# mppt.net
KiCad netlist of a schematic drawn in Altium Designer
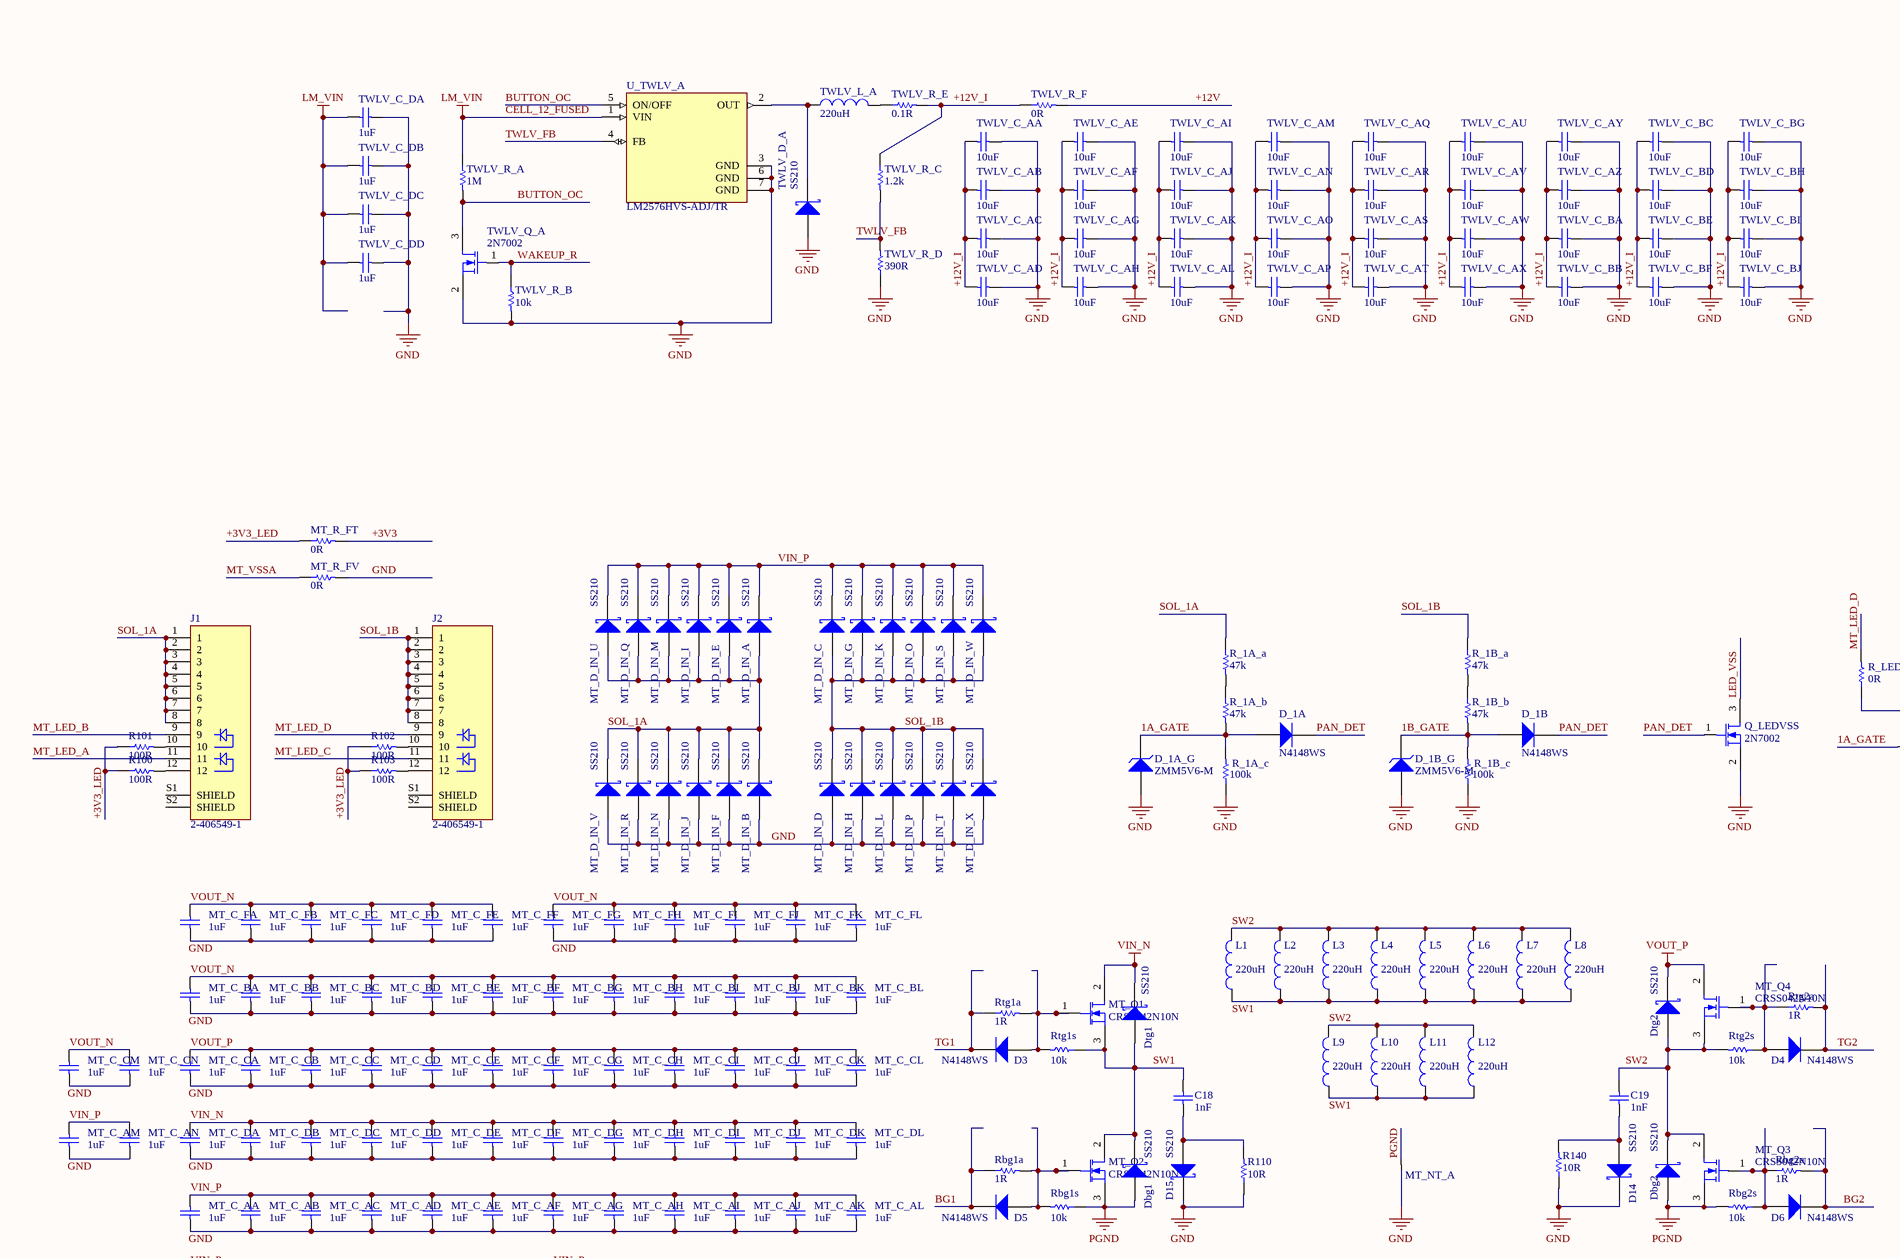
[diagram p0: mppt.SchDoc, top left]
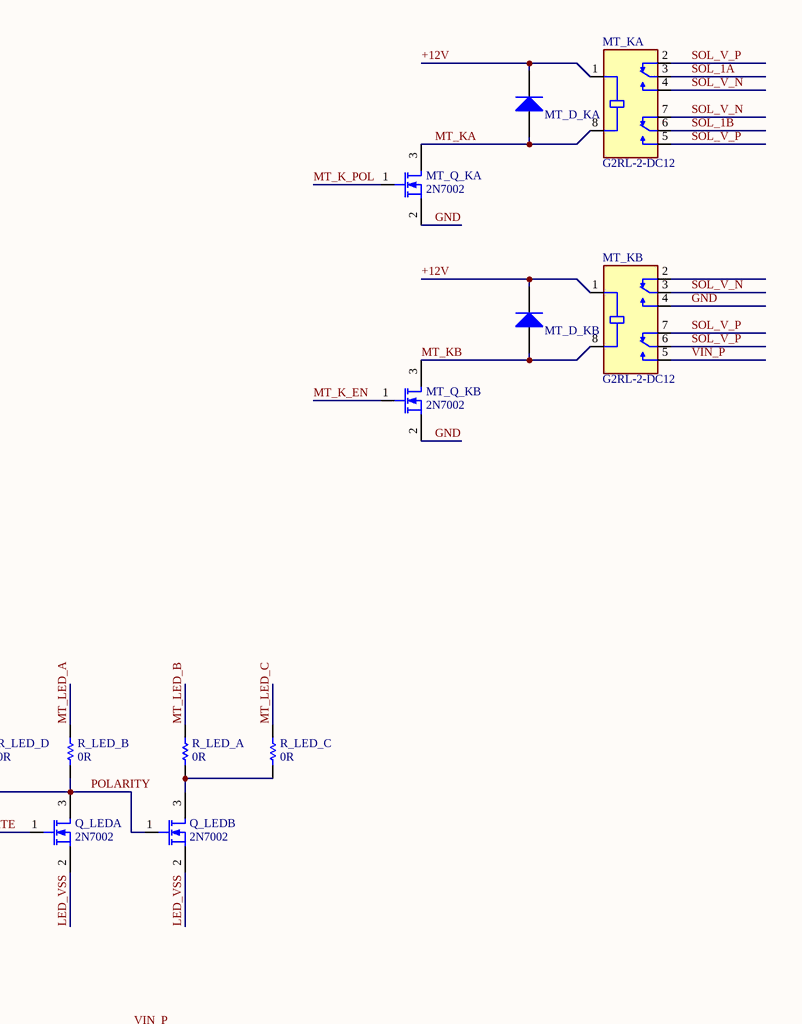
[diagram p1: mppt.SchDoc, top right]
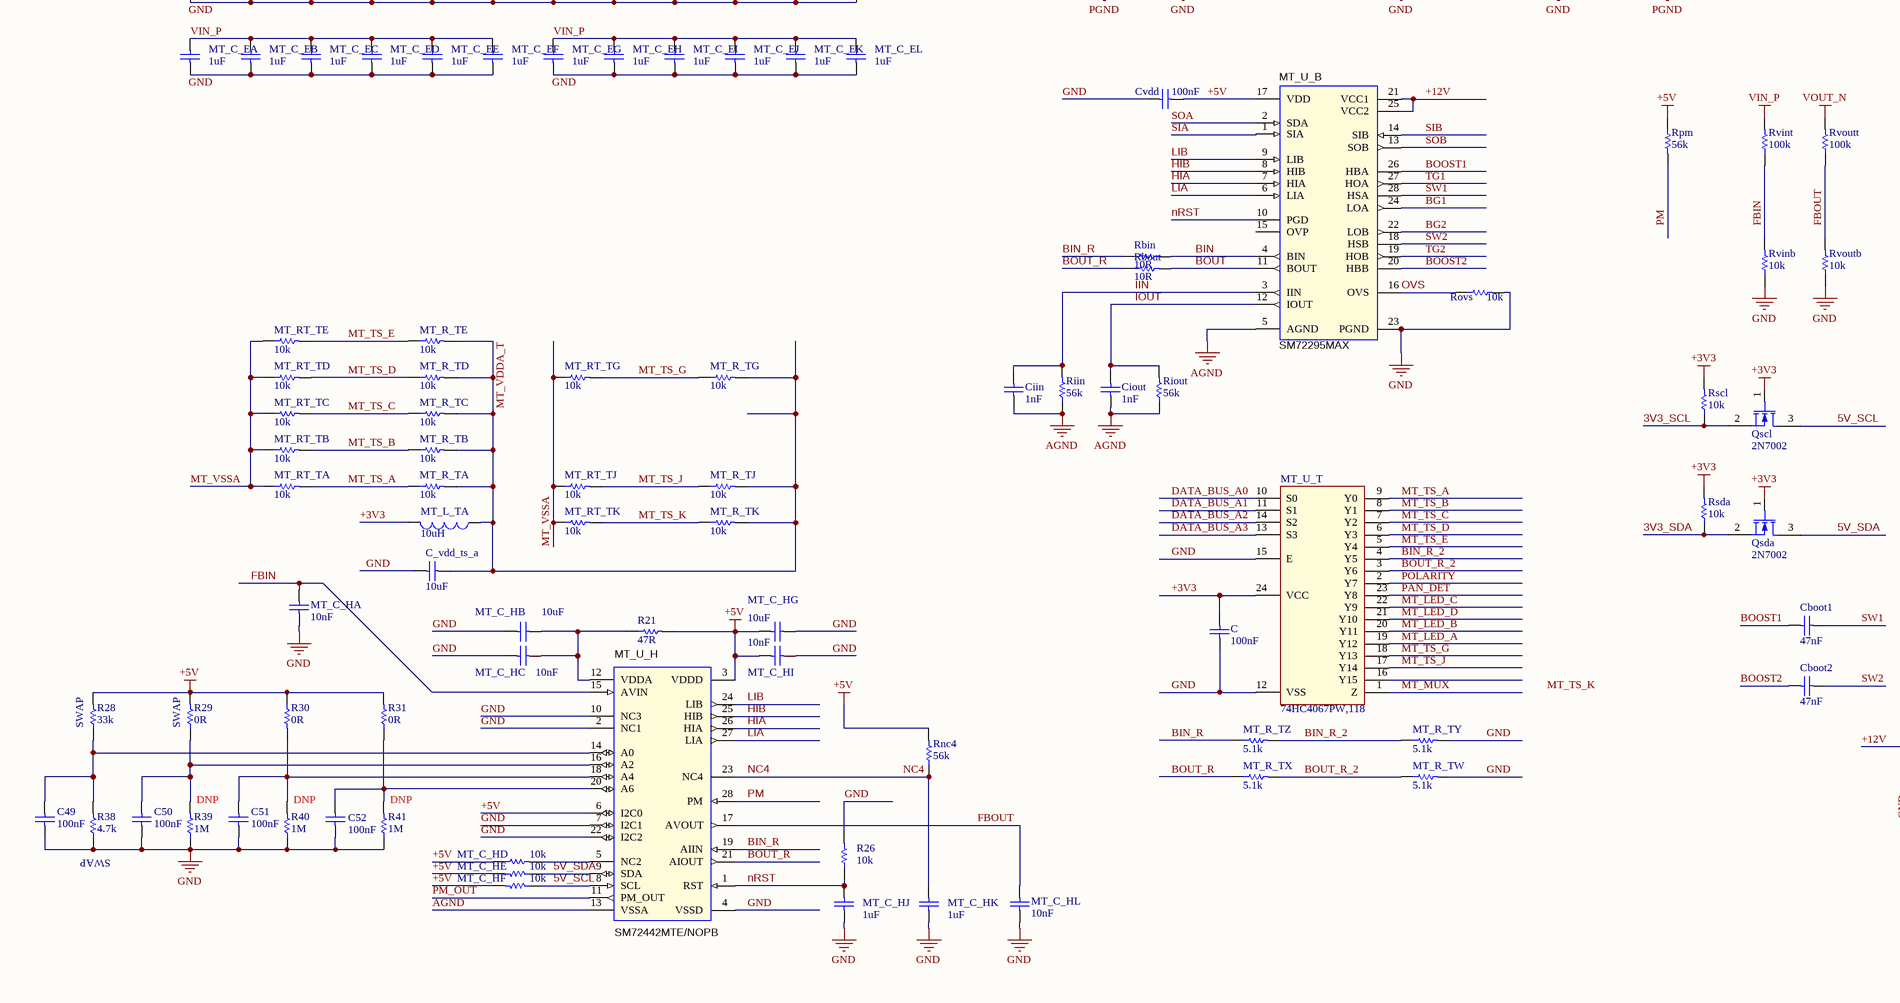
[diagram p2: mppt.SchDoc, bottom left]
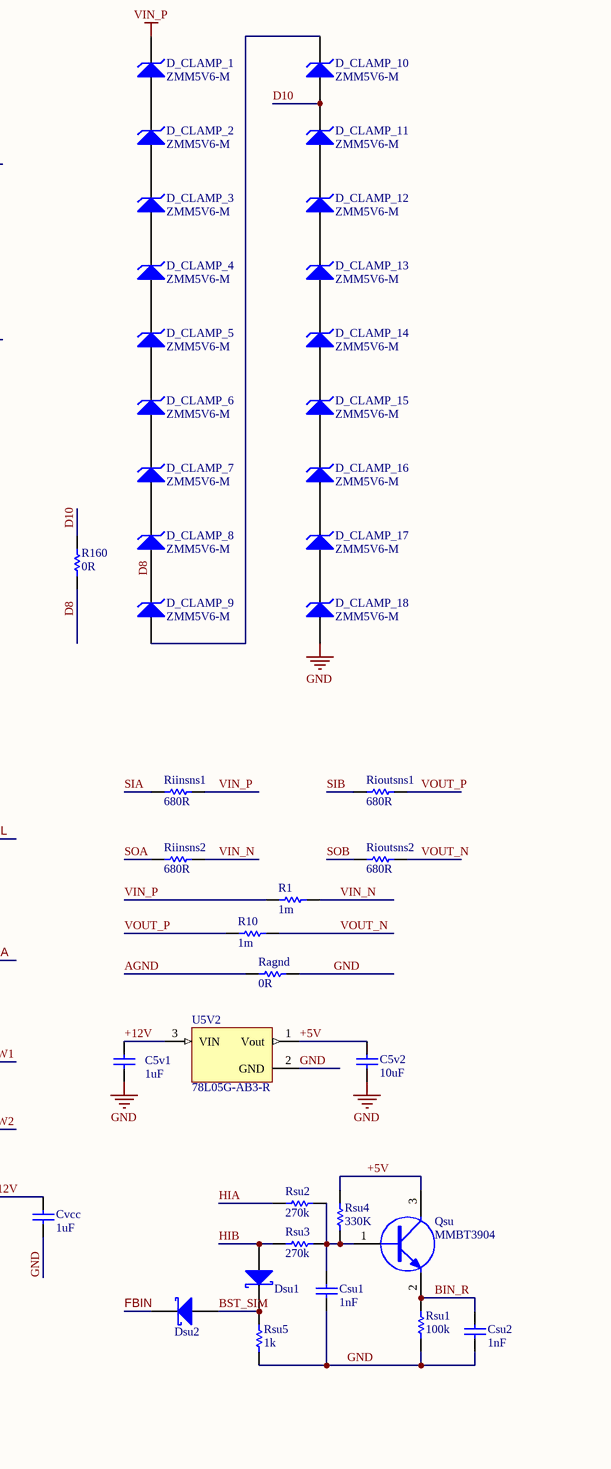
[diagram p3: mppt.SchDoc, bottom right]

(export (version "E")
  (design (tool "Eeschema 10.0.6"))
  (components
    (comp (ref "C")
      (value "100nF")
      (footprint "C_0402")
      (description "C - CAPACITOR - MLCC - 100nF - 16V - 0402")
      (fields (field (name "LCSC PART #") "C1525") (field (name "Comment") "CL05B104KO5NNNC"))
      (libsource (lib "JLC_PCB") (part "CL05B104KO5NNNC"))
    )
    (comp (ref "C5v1")
      (value "1uF")
      (footprint "C_0402")
      (description "C - CAPACITOR - MLCC - 1uF - 25V - 0402")
      (fields (field (name "LCSC PART #") "C52923") (field (name "Comment") "CL05A105KA5NQNC"))
      (libsource (lib "JLC_PCB") (part "CL05A105KA5NQNC"))
    )
    (comp (ref "C5v2")
      (value "10uF")
      (footprint "C_0402")
      (description "C - CAPACITOR - MLCC - 10uF - 6.3V - 0402")
      (fields (field (name "LCSC PART #") "C15525") (field (name "Comment") "CL05A106MQ5NUNC"))
      (libsource (lib "JLC_PCB") (part "CL05A106MQ5NUNC"))
    )
    (comp (ref "C18")
      (value "1nF")
      (footprint "C_1206")
      (description "C - CAPACITOR - MLCC - 1nF - 2000V - 1206 - X7R")
      (fields (field (name "LCSC PART #") "C9196") (field (name "Comment") "1206B102K202NT"))
      (libsource (lib "JLC_PCB") (part "1206B102K202NT"))
    )
    (comp (ref "C19")
      (value "1nF")
      (footprint "C_1206")
      (description "C - CAPACITOR - MLCC - 1nF - 2000V - 1206 - X7R")
      (fields (field (name "LCSC PART #") "C9196") (field (name "Comment") "1206B102K202NT"))
      (libsource (lib "JLC_PCB") (part "1206B102K202NT"))
    )
    (comp (ref "C49")
      (value "100nF")
      (footprint "C_0402")
      (description "C - CAPACITOR - MLCC - 100nF - 16V - 0402")
      (fields (field (name "LCSC PART #") "C1525") (field (name "Comment") "CL05B104KO5NNNC"))
      (libsource (lib "JLC_PCB") (part "CL05B104KO5NNNC"))
    )
    (comp (ref "C50")
      (value "100nF")
      (footprint "C_0402")
      (description "C - CAPACITOR - MLCC - 100nF - 16V - 0402")
      (fields (field (name "LCSC PART #") "C1525") (field (name "Comment") "CL05B104KO5NNNC"))
      (libsource (lib "JLC_PCB") (part "CL05B104KO5NNNC"))
    )
    (comp (ref "C51")
      (value "100nF")
      (footprint "C_0402")
      (description "C - CAPACITOR - MLCC - 100nF - 16V - 0402")
      (fields (field (name "LCSC PART #") "C1525") (field (name "Comment") "CL05B104KO5NNNC"))
      (libsource (lib "JLC_PCB") (part "CL05B104KO5NNNC"))
    )
    (comp (ref "C52")
      (value "100nF")
      (footprint "C_0402")
      (description "C - CAPACITOR - MLCC - 100nF - 16V - 0402")
      (fields (field (name "LCSC PART #") "C1525") (field (name "Comment") "CL05B104KO5NNNC"))
      (libsource (lib "JLC_PCB") (part "CL05B104KO5NNNC"))
    )
    (comp (ref "Cboot1")
      (value "47nF")
      (footprint "C_0603")
      (description "C - CAPACITOR - MLCC - 470nF - 25V - 0603")
      (fields (field (name "LCSC PART #") "C1623") (field (name "Comment") "CL10B474KA8NNNC"))
      (libsource (lib "JLC_PCB") (part "CL10B474KA8NNNC"))
    )
    (comp (ref "Cboot2")
      (value "47nF")
      (footprint "C_0603")
      (description "C - CAPACITOR - MLCC - 470nF - 25V - 0603")
      (fields (field (name "LCSC PART #") "C1623") (field (name "Comment") "CL10B474KA8NNNC"))
      (libsource (lib "JLC_PCB") (part "CL10B474KA8NNNC"))
    )
    (comp (ref "Ciin")
      (value "1nF")
      (footprint "C_0402")
      (description "C - CAPACITOR - MLCC - 1nF - 50V - 0402")
      (fields (field (name "LCSC PART #") "C1523") (field (name "Comment") "0402B102K500NT"))
      (libsource (lib "JLC_PCB") (part "0402B102K500NT"))
    )
    (comp (ref "Ciout")
      (value "1nF")
      (footprint "C_0402")
      (description "C - CAPACITOR - MLCC - 1nF - 50V - 0402")
      (fields (field (name "LCSC PART #") "C1523") (field (name "Comment") "0402B102K500NT"))
      (libsource (lib "JLC_PCB") (part "0402B102K500NT"))
    )
    (comp (ref "Csu1")
      (value "1nF")
      (footprint "C_0402")
      (description "C - CAPACITOR - MLCC - 1nF - 50V - 0402")
      (fields (field (name "LCSC PART #") "C1523") (field (name "Comment") "0402B102K500NT"))
      (libsource (lib "JLC_PCB") (part "0402B102K500NT"))
    )
    (comp (ref "Csu2")
      (value "1nF")
      (footprint "C_0402")
      (description "C - CAPACITOR - MLCC - 1nF - 50V - 0402")
      (fields (field (name "LCSC PART #") "C1523") (field (name "Comment") "0402B102K500NT"))
      (libsource (lib "JLC_PCB") (part "0402B102K500NT"))
    )
    (comp (ref "Cvcc")
      (value "1uF")
      (footprint "C_0402")
      (description "C - CAPACITOR - MLCC - 1uF - 25V - 0402")
      (fields (field (name "LCSC PART #") "C52923") (field (name "Comment") "CL05A105KA5NQNC"))
      (libsource (lib "JLC_PCB") (part "CL05A105KA5NQNC"))
    )
    (comp (ref "Cvdd")
      (value "100nF")
      (footprint "C_0402")
      (description "C - CAPACITOR - MLCC - 100nF - 16V - 0402")
      (fields (field (name "LCSC PART #") "C1525") (field (name "Comment") "CL05B104KO5NNNC"))
      (libsource (lib "JLC_PCB") (part "CL05B104KO5NNNC"))
    )
    (comp (ref "C_vdd_ts_a")
      (value "10uF")
      (footprint "C_0402")
      (description "C - CAPACITOR - MLCC - 10uF - 6.3V - 0402")
      (fields (field (name "LCSC PART #") "C15525") (field (name "Comment") "CL05A106MQ5NUNC"))
      (libsource (lib "JLC_PCB") (part "CL05A106MQ5NUNC"))
    )
    (comp (ref "D3")
      (value "N4148WS")
      (footprint "SOD-323")
      (description "D - DIODE - FAST TRR - 100V - 150mA - 4ns")
      (fields (field (name "LCSC PART #") "C2128"))
      (libsource (lib "JLC_PCB") (part "N4148WS"))
    )
    (comp (ref "D4")
      (value "N4148WS")
      (footprint "SOD-323")
      (description "D - DIODE - FAST TRR - 100V - 150mA - 4ns")
      (fields (field (name "LCSC PART #") "C2128"))
      (libsource (lib "JLC_PCB") (part "N4148WS"))
    )
    (comp (ref "D5")
      (value "N4148WS")
      (footprint "SOD-323")
      (description "D - DIODE - FAST TRR - 100V - 150mA - 4ns")
      (fields (field (name "LCSC PART #") "C2128"))
      (libsource (lib "JLC_PCB") (part "N4148WS"))
    )
    (comp (ref "D6")
      (value "N4148WS")
      (footprint "SOD-323")
      (description "D - DIODE - FAST TRR - 100V - 150mA - 4ns")
      (fields (field (name "LCSC PART #") "C2128"))
      (libsource (lib "JLC_PCB") (part "N4148WS"))
    )
    (comp (ref "D14")
      (value "SS210")
      (footprint "DO-214AC")
      (description "D - DIODE - SCHOTTKY - 100V - 2A")
      (fields (field (name "LCSC PART #") "C14996"))
      (libsource (lib "JLC_PCB") (part "SS210"))
    )
    (comp (ref "D15")
      (value "SS210")
      (footprint "DO-214AC")
      (description "D - DIODE - SCHOTTKY - 100V - 2A")
      (fields (field (name "LCSC PART #") "C14996"))
      (libsource (lib "JLC_PCB") (part "SS210"))
    )
    (comp (ref "Dbg1")
      (value "SS210")
      (footprint "DO-214AC")
      (description "D - DIODE - SCHOTTKY - 100V - 2A")
      (fields (field (name "LCSC PART #") "C14996"))
      (libsource (lib "JLC_PCB") (part "SS210"))
    )
    (comp (ref "Dbg2")
      (value "SS210")
      (footprint "DO-214AC")
      (description "D - DIODE - SCHOTTKY - 100V - 2A")
      (fields (field (name "LCSC PART #") "C14996"))
      (libsource (lib "JLC_PCB") (part "SS210"))
    )
    (comp (ref "Dsu1")
      (value "1N5819WS")
      (footprint "SOD-323")
      (description "D - DIODE - SCHOTTKY - 40V - 1A")
      (fields (field (name "LCSC PART #") "C191023"))
      (libsource (lib "JLC_PCB") (part "1N5819WS"))
    )
    (comp (ref "Dsu2")
      (value "1N5819WS")
      (footprint "SOD-323")
      (description "D - DIODE - SCHOTTKY - 40V - 1A")
      (fields (field (name "LCSC PART #") "C191023"))
      (libsource (lib "JLC_PCB") (part "1N5819WS"))
    )
    (comp (ref "Dtg1")
      (value "SS210")
      (footprint "DO-214AC")
      (description "D - DIODE - SCHOTTKY - 100V - 2A")
      (fields (field (name "LCSC PART #") "C14996"))
      (libsource (lib "JLC_PCB") (part "SS210"))
    )
    (comp (ref "Dtg2")
      (value "SS210")
      (footprint "DO-214AC")
      (description "D - DIODE - SCHOTTKY - 100V - 2A")
      (fields (field (name "LCSC PART #") "C14996"))
      (libsource (lib "JLC_PCB") (part "SS210"))
    )
    (comp (ref "D_1A")
      (value "N4148WS")
      (footprint "SOD-323")
      (description "D - DIODE - FAST TRR - 100V - 150mA - 4ns")
      (fields (field (name "LCSC PART #") "C2128"))
      (libsource (lib "JLC_PCB") (part "N4148WS"))
    )
    (comp (ref "D_1A_G")
      (value "ZMM5V6-M")
      (footprint "DO-213AA")
      (description "D - DIODE - ZENER - 5.6V - 500mW")
      (fields (field (name "LCSC PART #") "C8062"))
      (libsource (lib "JLC_PCB") (part "ZMM5V6-M"))
    )
    (comp (ref "D_1B")
      (value "N4148WS")
      (footprint "SOD-323")
      (description "D - DIODE - FAST TRR - 100V - 150mA - 4ns")
      (fields (field (name "LCSC PART #") "C2128"))
      (libsource (lib "JLC_PCB") (part "N4148WS"))
    )
    (comp (ref "D_1B_G")
      (value "ZMM5V6-M")
      (footprint "DO-213AA")
      (description "D - DIODE - ZENER - 5.6V - 500mW")
      (fields (field (name "LCSC PART #") "C8062"))
      (libsource (lib "JLC_PCB") (part "ZMM5V6-M"))
    )
    (comp (ref "D_CLAMP_1")
      (value "ZMM5V6-M")
      (footprint "DO-213AA")
      (description "D - DIODE - ZENER - 5.6V - 500mW")
      (fields (field (name "LCSC PART #") "C8062"))
      (libsource (lib "JLC_PCB") (part "ZMM5V6-M"))
    )
    (comp (ref "D_CLAMP_2")
      (value "ZMM5V6-M")
      (footprint "DO-213AA")
      (description "D - DIODE - ZENER - 5.6V - 500mW")
      (fields (field (name "LCSC PART #") "C8062"))
      (libsource (lib "JLC_PCB") (part "ZMM5V6-M"))
    )
    (comp (ref "D_CLAMP_3")
      (value "ZMM5V6-M")
      (footprint "DO-213AA")
      (description "D - DIODE - ZENER - 5.6V - 500mW")
      (fields (field (name "LCSC PART #") "C8062"))
      (libsource (lib "JLC_PCB") (part "ZMM5V6-M"))
    )
    (comp (ref "D_CLAMP_4")
      (value "ZMM5V6-M")
      (footprint "DO-213AA")
      (description "D - DIODE - ZENER - 5.6V - 500mW")
      (fields (field (name "LCSC PART #") "C8062"))
      (libsource (lib "JLC_PCB") (part "ZMM5V6-M"))
    )
    (comp (ref "D_CLAMP_5")
      (value "ZMM5V6-M")
      (footprint "DO-213AA")
      (description "D - DIODE - ZENER - 5.6V - 500mW")
      (fields (field (name "LCSC PART #") "C8062"))
      (libsource (lib "JLC_PCB") (part "ZMM5V6-M"))
    )
    (comp (ref "D_CLAMP_6")
      (value "ZMM5V6-M")
      (footprint "DO-213AA")
      (description "D - DIODE - ZENER - 5.6V - 500mW")
      (fields (field (name "LCSC PART #") "C8062"))
      (libsource (lib "JLC_PCB") (part "ZMM5V6-M"))
    )
    (comp (ref "D_CLAMP_7")
      (value "ZMM5V6-M")
      (footprint "DO-213AA")
      (description "D - DIODE - ZENER - 5.6V - 500mW")
      (fields (field (name "LCSC PART #") "C8062"))
      (libsource (lib "JLC_PCB") (part "ZMM5V6-M"))
    )
    (comp (ref "D_CLAMP_8")
      (value "ZMM5V6-M")
      (footprint "DO-213AA")
      (description "D - DIODE - ZENER - 5.6V - 500mW")
      (fields (field (name "LCSC PART #") "C8062"))
      (libsource (lib "JLC_PCB") (part "ZMM5V6-M"))
    )
    (comp (ref "D_CLAMP_9")
      (value "ZMM5V6-M")
      (footprint "DO-213AA")
      (description "D - DIODE - ZENER - 5.6V - 500mW")
      (fields (field (name "LCSC PART #") "C8062"))
      (libsource (lib "JLC_PCB") (part "ZMM5V6-M"))
    )
    (comp (ref "D_CLAMP_10")
      (value "ZMM5V6-M")
      (footprint "DO-213AA")
      (description "D - DIODE - ZENER - 5.6V - 500mW")
      (fields (field (name "LCSC PART #") "C8062"))
      (libsource (lib "JLC_PCB") (part "ZMM5V6-M"))
    )
    (comp (ref "D_CLAMP_11")
      (value "ZMM5V6-M")
      (footprint "DO-213AA")
      (description "D - DIODE - ZENER - 5.6V - 500mW")
      (fields (field (name "LCSC PART #") "C8062"))
      (libsource (lib "JLC_PCB") (part "ZMM5V6-M"))
    )
    (comp (ref "D_CLAMP_12")
      (value "ZMM5V6-M")
      (footprint "DO-213AA")
      (description "D - DIODE - ZENER - 5.6V - 500mW")
      (fields (field (name "LCSC PART #") "C8062"))
      (libsource (lib "JLC_PCB") (part "ZMM5V6-M"))
    )
    (comp (ref "D_CLAMP_13")
      (value "ZMM5V6-M")
      (footprint "DO-213AA")
      (description "D - DIODE - ZENER - 5.6V - 500mW")
      (fields (field (name "LCSC PART #") "C8062"))
      (libsource (lib "JLC_PCB") (part "ZMM5V6-M"))
    )
    (comp (ref "D_CLAMP_14")
      (value "ZMM5V6-M")
      (footprint "DO-213AA")
      (description "D - DIODE - ZENER - 5.6V - 500mW")
      (fields (field (name "LCSC PART #") "C8062"))
      (libsource (lib "JLC_PCB") (part "ZMM5V6-M"))
    )
    (comp (ref "D_CLAMP_15")
      (value "ZMM5V6-M")
      (footprint "DO-213AA")
      (description "D - DIODE - ZENER - 5.6V - 500mW")
      (fields (field (name "LCSC PART #") "C8062"))
      (libsource (lib "JLC_PCB") (part "ZMM5V6-M"))
    )
    (comp (ref "D_CLAMP_16")
      (value "ZMM5V6-M")
      (footprint "DO-213AA")
      (description "D - DIODE - ZENER - 5.6V - 500mW")
      (fields (field (name "LCSC PART #") "C8062"))
      (libsource (lib "JLC_PCB") (part "ZMM5V6-M"))
    )
    (comp (ref "D_CLAMP_17")
      (value "ZMM5V6-M")
      (footprint "DO-213AA")
      (description "D - DIODE - ZENER - 5.6V - 500mW")
      (fields (field (name "LCSC PART #") "C8062"))
      (libsource (lib "JLC_PCB") (part "ZMM5V6-M"))
    )
    (comp (ref "D_CLAMP_18")
      (value "ZMM5V6-M")
      (footprint "DO-213AA")
      (description "D - DIODE - ZENER - 5.6V - 500mW")
      (fields (field (name "LCSC PART #") "C8062"))
      (libsource (lib "JLC_PCB") (part "ZMM5V6-M"))
    )
    (comp (ref "J1")
      (value "2-406549-1")
      (footprint "TE_2-406549-1")
      (description "J - JACK - ETHERNET - Right - THT")
      (fields (field (name "LCSC PART #") "C125068"))
      (libsource (lib "JLC_PCB") (part "2-406549-1"))
    )
    (comp (ref "J2")
      (value "2-406549-1")
      (footprint "TE_2-406549-1")
      (description "J - JACK - ETHERNET - Right - THT")
      (fields (field (name "LCSC PART #") "C125068"))
      (libsource (lib "JLC_PCB") (part "2-406549-1"))
    )
    (comp (ref "L1")
      (value "220uH")
      (footprint "SRR1260")
      (description "L - INDUCTOR - 220uH - 1.6A - 12.5mm")
      (fields (field (name "LCSC PART #") "C169380") (field (name "Comment") "SWRB1207S-221MT"))
      (libsource (lib "JLC_PCB") (part "SWRB1207S-221MT"))
    )
    (comp (ref "L2")
      (value "220uH")
      (footprint "SRR1260")
      (description "L - INDUCTOR - 220uH - 1.6A - 12.5mm")
      (fields (field (name "LCSC PART #") "C169380") (field (name "Comment") "SWRB1207S-221MT"))
      (libsource (lib "JLC_PCB") (part "SWRB1207S-221MT"))
    )
    (comp (ref "L3")
      (value "220uH")
      (footprint "SRR1260")
      (description "L - INDUCTOR - 220uH - 1.6A - 12.5mm")
      (fields (field (name "LCSC PART #") "C169380") (field (name "Comment") "SWRB1207S-221MT"))
      (libsource (lib "JLC_PCB") (part "SWRB1207S-221MT"))
    )
    (comp (ref "L4")
      (value "220uH")
      (footprint "SRR1260")
      (description "L - INDUCTOR - 220uH - 1.6A - 12.5mm")
      (fields (field (name "LCSC PART #") "C169380") (field (name "Comment") "SWRB1207S-221MT"))
      (libsource (lib "JLC_PCB") (part "SWRB1207S-221MT"))
    )
    (comp (ref "L5")
      (value "220uH")
      (footprint "SRR1260")
      (description "L - INDUCTOR - 220uH - 1.6A - 12.5mm")
      (fields (field (name "LCSC PART #") "C169380") (field (name "Comment") "SWRB1207S-221MT"))
      (libsource (lib "JLC_PCB") (part "SWRB1207S-221MT"))
    )
    (comp (ref "L6")
      (value "220uH")
      (footprint "SRR1260")
      (description "L - INDUCTOR - 220uH - 1.6A - 12.5mm")
      (fields (field (name "LCSC PART #") "C169380") (field (name "Comment") "SWRB1207S-221MT"))
      (libsource (lib "JLC_PCB") (part "SWRB1207S-221MT"))
    )
    (comp (ref "L7")
      (value "220uH")
      (footprint "SRR1260")
      (description "L - INDUCTOR - 220uH - 1.6A - 12.5mm")
      (fields (field (name "LCSC PART #") "C169380") (field (name "Comment") "SWRB1207S-221MT"))
      (libsource (lib "JLC_PCB") (part "SWRB1207S-221MT"))
    )
    (comp (ref "L8")
      (value "220uH")
      (footprint "SRR1260")
      (description "L - INDUCTOR - 220uH - 1.6A - 12.5mm")
      (fields (field (name "LCSC PART #") "C169380") (field (name "Comment") "SWRB1207S-221MT"))
      (libsource (lib "JLC_PCB") (part "SWRB1207S-221MT"))
    )
    (comp (ref "L9")
      (value "220uH")
      (footprint "SRR1260")
      (description "L - INDUCTOR - 220uH - 1.6A - 12.5mm")
      (fields (field (name "LCSC PART #") "C169380") (field (name "Comment") "SWRB1207S-221MT"))
      (libsource (lib "JLC_PCB") (part "SWRB1207S-221MT"))
    )
    (comp (ref "L10")
      (value "220uH")
      (footprint "SRR1260")
      (description "L - INDUCTOR - 220uH - 1.6A - 12.5mm")
      (fields (field (name "LCSC PART #") "C169380") (field (name "Comment") "SWRB1207S-221MT"))
      (libsource (lib "JLC_PCB") (part "SWRB1207S-221MT"))
    )
    (comp (ref "L11")
      (value "220uH")
      (footprint "SRR1260")
      (description "L - INDUCTOR - 220uH - 1.6A - 12.5mm")
      (fields (field (name "LCSC PART #") "C169380") (field (name "Comment") "SWRB1207S-221MT"))
      (libsource (lib "JLC_PCB") (part "SWRB1207S-221MT"))
    )
    (comp (ref "L12")
      (value "220uH")
      (footprint "SRR1260")
      (description "L - INDUCTOR - 220uH - 1.6A - 12.5mm")
      (fields (field (name "LCSC PART #") "C169380") (field (name "Comment") "SWRB1207S-221MT"))
      (libsource (lib "JLC_PCB") (part "SWRB1207S-221MT"))
    )
    (comp (ref "MT_C_AA")
      (value "1uF")
      (footprint "C_1206")
      (description "C - CAPACITOR - MLCC - 1uF - 100V - 1206 - X7R")
      (fields (field (name "LCSC PART #") "C91151") (field (name "Comment") "1206B105K101NT"))
      (libsource (lib "JLC_PCB") (part "1206B105K101NT"))
    )
    (comp (ref "MT_C_AB")
      (value "1uF")
      (footprint "C_1206")
      (description "C - CAPACITOR - MLCC - 1uF - 100V - 1206 - X7R")
      (fields (field (name "LCSC PART #") "C91151") (field (name "Comment") "1206B105K101NT"))
      (libsource (lib "JLC_PCB") (part "1206B105K101NT"))
    )
    (comp (ref "MT_C_AC")
      (value "1uF")
      (footprint "C_1206")
      (description "C - CAPACITOR - MLCC - 1uF - 100V - 1206 - X7R")
      (fields (field (name "LCSC PART #") "C91151") (field (name "Comment") "1206B105K101NT"))
      (libsource (lib "JLC_PCB") (part "1206B105K101NT"))
    )
    (comp (ref "MT_C_AD")
      (value "1uF")
      (footprint "C_1206")
      (description "C - CAPACITOR - MLCC - 1uF - 100V - 1206 - X7R")
      (fields (field (name "LCSC PART #") "C91151") (field (name "Comment") "1206B105K101NT"))
      (libsource (lib "JLC_PCB") (part "1206B105K101NT"))
    )
    (comp (ref "MT_C_AE")
      (value "1uF")
      (footprint "C_1206")
      (description "C - CAPACITOR - MLCC - 1uF - 100V - 1206 - X7R")
      (fields (field (name "LCSC PART #") "C91151") (field (name "Comment") "1206B105K101NT"))
      (libsource (lib "JLC_PCB") (part "1206B105K101NT"))
    )
    (comp (ref "MT_C_AF")
      (value "1uF")
      (footprint "C_1206")
      (description "C - CAPACITOR - MLCC - 1uF - 100V - 1206 - X7R")
      (fields (field (name "LCSC PART #") "C91151") (field (name "Comment") "1206B105K101NT"))
      (libsource (lib "JLC_PCB") (part "1206B105K101NT"))
    )
    (comp (ref "MT_C_AG")
      (value "1uF")
      (footprint "C_1206")
      (description "C - CAPACITOR - MLCC - 1uF - 100V - 1206 - X7R")
      (fields (field (name "LCSC PART #") "C91151") (field (name "Comment") "1206B105K101NT"))
      (libsource (lib "JLC_PCB") (part "1206B105K101NT"))
    )
    (comp (ref "MT_C_AH")
      (value "1uF")
      (footprint "C_1206")
      (description "C - CAPACITOR - MLCC - 1uF - 100V - 1206 - X7R")
      (fields (field (name "LCSC PART #") "C91151") (field (name "Comment") "1206B105K101NT"))
      (libsource (lib "JLC_PCB") (part "1206B105K101NT"))
    )
    (comp (ref "MT_C_AI")
      (value "1uF")
      (footprint "C_1206")
      (description "C - CAPACITOR - MLCC - 1uF - 100V - 1206 - X7R")
      (fields (field (name "LCSC PART #") "C91151") (field (name "Comment") "1206B105K101NT"))
      (libsource (lib "JLC_PCB") (part "1206B105K101NT"))
    )
    (comp (ref "MT_C_AJ")
      (value "1uF")
      (footprint "C_1206")
      (description "C - CAPACITOR - MLCC - 1uF - 100V - 1206 - X7R")
      (fields (field (name "LCSC PART #") "C91151") (field (name "Comment") "1206B105K101NT"))
      (libsource (lib "JLC_PCB") (part "1206B105K101NT"))
    )
    (comp (ref "MT_C_AK")
      (value "1uF")
      (footprint "C_1206")
      (description "C - CAPACITOR - MLCC - 1uF - 100V - 1206 - X7R")
      (fields (field (name "LCSC PART #") "C91151") (field (name "Comment") "1206B105K101NT"))
      (libsource (lib "JLC_PCB") (part "1206B105K101NT"))
    )
    (comp (ref "MT_C_AL")
      (value "1uF")
      (footprint "C_1206")
      (description "C - CAPACITOR - MLCC - 1uF - 100V - 1206 - X7R")
      (fields (field (name "LCSC PART #") "C91151") (field (name "Comment") "1206B105K101NT"))
      (libsource (lib "JLC_PCB") (part "1206B105K101NT"))
    )
    (comp (ref "MT_C_AM")
      (value "1uF")
      (footprint "C_1206")
      (description "C - CAPACITOR - MLCC - 1uF - 100V - 1206 - X7R")
      (fields (field (name "LCSC PART #") "C91151") (field (name "Comment") "1206B105K101NT"))
      (libsource (lib "JLC_PCB") (part "1206B105K101NT"))
    )
    (comp (ref "MT_C_AN")
      (value "1uF")
      (footprint "C_1206")
      (description "C - CAPACITOR - MLCC - 1uF - 100V - 1206 - X7R")
      (fields (field (name "LCSC PART #") "C91151") (field (name "Comment") "1206B105K101NT"))
      (libsource (lib "JLC_PCB") (part "1206B105K101NT"))
    )
    (comp (ref "MT_C_BA")
      (value "1uF")
      (footprint "C_1206")
      (description "C - CAPACITOR - MLCC - 1uF - 100V - 1206 - X7R")
      (fields (field (name "LCSC PART #") "C91151") (field (name "Comment") "1206B105K101NT"))
      (libsource (lib "JLC_PCB") (part "1206B105K101NT"))
    )
    (comp (ref "MT_C_BB")
      (value "1uF")
      (footprint "C_1206")
      (description "C - CAPACITOR - MLCC - 1uF - 100V - 1206 - X7R")
      (fields (field (name "LCSC PART #") "C91151") (field (name "Comment") "1206B105K101NT"))
      (libsource (lib "JLC_PCB") (part "1206B105K101NT"))
    )
    (comp (ref "MT_C_BC")
      (value "1uF")
      (footprint "C_1206")
      (description "C - CAPACITOR - MLCC - 1uF - 100V - 1206 - X7R")
      (fields (field (name "LCSC PART #") "C91151") (field (name "Comment") "1206B105K101NT"))
      (libsource (lib "JLC_PCB") (part "1206B105K101NT"))
    )
    (comp (ref "MT_C_BD")
      (value "1uF")
      (footprint "C_1206")
      (description "C - CAPACITOR - MLCC - 1uF - 100V - 1206 - X7R")
      (fields (field (name "LCSC PART #") "C91151") (field (name "Comment") "1206B105K101NT"))
      (libsource (lib "JLC_PCB") (part "1206B105K101NT"))
    )
    (comp (ref "MT_C_BE")
      (value "1uF")
      (footprint "C_1206")
      (description "C - CAPACITOR - MLCC - 1uF - 100V - 1206 - X7R")
      (fields (field (name "LCSC PART #") "C91151") (field (name "Comment") "1206B105K101NT"))
      (libsource (lib "JLC_PCB") (part "1206B105K101NT"))
    )
    (comp (ref "MT_C_BF")
      (value "1uF")
      (footprint "C_1206")
      (description "C - CAPACITOR - MLCC - 1uF - 100V - 1206 - X7R")
      (fields (field (name "LCSC PART #") "C91151") (field (name "Comment") "1206B105K101NT"))
      (libsource (lib "JLC_PCB") (part "1206B105K101NT"))
    )
    (comp (ref "MT_C_BG")
      (value "1uF")
      (footprint "C_1206")
      (description "C - CAPACITOR - MLCC - 1uF - 100V - 1206 - X7R")
      (fields (field (name "LCSC PART #") "C91151") (field (name "Comment") "1206B105K101NT"))
      (libsource (lib "JLC_PCB") (part "1206B105K101NT"))
    )
    (comp (ref "MT_C_BH")
      (value "1uF")
      (footprint "C_1206")
      (description "C - CAPACITOR - MLCC - 1uF - 100V - 1206 - X7R")
      (fields (field (name "LCSC PART #") "C91151") (field (name "Comment") "1206B105K101NT"))
      (libsource (lib "JLC_PCB") (part "1206B105K101NT"))
    )
    (comp (ref "MT_C_BI")
      (value "1uF")
      (footprint "C_1206")
      (description "C - CAPACITOR - MLCC - 1uF - 100V - 1206 - X7R")
      (fields (field (name "LCSC PART #") "C91151") (field (name "Comment") "1206B105K101NT"))
      (libsource (lib "JLC_PCB") (part "1206B105K101NT"))
    )
    (comp (ref "MT_C_BJ")
      (value "1uF")
      (footprint "C_1206")
      (description "C - CAPACITOR - MLCC - 1uF - 100V - 1206 - X7R")
      (fields (field (name "LCSC PART #") "C91151") (field (name "Comment") "1206B105K101NT"))
      (libsource (lib "JLC_PCB") (part "1206B105K101NT"))
    )
    (comp (ref "MT_C_BK")
      (value "1uF")
      (footprint "C_1206")
      (description "C - CAPACITOR - MLCC - 1uF - 100V - 1206 - X7R")
      (fields (field (name "LCSC PART #") "C91151") (field (name "Comment") "1206B105K101NT"))
      (libsource (lib "JLC_PCB") (part "1206B105K101NT"))
    )
    (comp (ref "MT_C_BL")
      (value "1uF")
      (footprint "C_1206")
      (description "C - CAPACITOR - MLCC - 1uF - 100V - 1206 - X7R")
      (fields (field (name "LCSC PART #") "C91151") (field (name "Comment") "1206B105K101NT"))
      (libsource (lib "JLC_PCB") (part "1206B105K101NT"))
    )
    (comp (ref "MT_C_CA")
      (value "1uF")
      (footprint "C_1206")
      (description "C - CAPACITOR - MLCC - 1uF - 100V - 1206 - X7R")
      (fields (field (name "LCSC PART #") "C91151") (field (name "Comment") "1206B105K101NT"))
      (libsource (lib "JLC_PCB") (part "1206B105K101NT"))
    )
    (comp (ref "MT_C_CB")
      (value "1uF")
      (footprint "C_1206")
      (description "C - CAPACITOR - MLCC - 1uF - 100V - 1206 - X7R")
      (fields (field (name "LCSC PART #") "C91151") (field (name "Comment") "1206B105K101NT"))
      (libsource (lib "JLC_PCB") (part "1206B105K101NT"))
    )
    (comp (ref "MT_C_CC")
      (value "1uF")
      (footprint "C_1206")
      (description "C - CAPACITOR - MLCC - 1uF - 100V - 1206 - X7R")
      (fields (field (name "LCSC PART #") "C91151") (field (name "Comment") "1206B105K101NT"))
      (libsource (lib "JLC_PCB") (part "1206B105K101NT"))
    )
    (comp (ref "MT_C_CD")
      (value "1uF")
      (footprint "C_1206")
      (description "C - CAPACITOR - MLCC - 1uF - 100V - 1206 - X7R")
      (fields (field (name "LCSC PART #") "C91151") (field (name "Comment") "1206B105K101NT"))
      (libsource (lib "JLC_PCB") (part "1206B105K101NT"))
    )
    (comp (ref "MT_C_CE")
      (value "1uF")
      (footprint "C_1206")
      (description "C - CAPACITOR - MLCC - 1uF - 100V - 1206 - X7R")
      (fields (field (name "LCSC PART #") "C91151") (field (name "Comment") "1206B105K101NT"))
      (libsource (lib "JLC_PCB") (part "1206B105K101NT"))
    )
    (comp (ref "MT_C_CF")
      (value "1uF")
      (footprint "C_1206")
      (description "C - CAPACITOR - MLCC - 1uF - 100V - 1206 - X7R")
      (fields (field (name "LCSC PART #") "C91151") (field (name "Comment") "1206B105K101NT"))
      (libsource (lib "JLC_PCB") (part "1206B105K101NT"))
    )
    (comp (ref "MT_C_CG")
      (value "1uF")
      (footprint "C_1206")
      (description "C - CAPACITOR - MLCC - 1uF - 100V - 1206 - X7R")
      (fields (field (name "LCSC PART #") "C91151") (field (name "Comment") "1206B105K101NT"))
      (libsource (lib "JLC_PCB") (part "1206B105K101NT"))
    )
    (comp (ref "MT_C_CH")
      (value "1uF")
      (footprint "C_1206")
      (description "C - CAPACITOR - MLCC - 1uF - 100V - 1206 - X7R")
      (fields (field (name "LCSC PART #") "C91151") (field (name "Comment") "1206B105K101NT"))
      (libsource (lib "JLC_PCB") (part "1206B105K101NT"))
    )
    (comp (ref "MT_C_CI")
      (value "1uF")
      (footprint "C_1206")
      (description "C - CAPACITOR - MLCC - 1uF - 100V - 1206 - X7R")
      (fields (field (name "LCSC PART #") "C91151") (field (name "Comment") "1206B105K101NT"))
      (libsource (lib "JLC_PCB") (part "1206B105K101NT"))
    )
    (comp (ref "MT_C_CJ")
      (value "1uF")
      (footprint "C_1206")
      (description "C - CAPACITOR - MLCC - 1uF - 100V - 1206 - X7R")
      (fields (field (name "LCSC PART #") "C91151") (field (name "Comment") "1206B105K101NT"))
      (libsource (lib "JLC_PCB") (part "1206B105K101NT"))
    )
    (comp (ref "MT_C_CK")
      (value "1uF")
      (footprint "C_1206")
      (description "C - CAPACITOR - MLCC - 1uF - 100V - 1206 - X7R")
      (fields (field (name "LCSC PART #") "C91151") (field (name "Comment") "1206B105K101NT"))
      (libsource (lib "JLC_PCB") (part "1206B105K101NT"))
    )
    (comp (ref "MT_C_CL")
      (value "1uF")
      (footprint "C_1206")
      (description "C - CAPACITOR - MLCC - 1uF - 100V - 1206 - X7R")
      (fields (field (name "LCSC PART #") "C91151") (field (name "Comment") "1206B105K101NT"))
      (libsource (lib "JLC_PCB") (part "1206B105K101NT"))
    )
    (comp (ref "MT_C_CM")
      (value "1uF")
      (footprint "C_1206")
      (description "C - CAPACITOR - MLCC - 1uF - 100V - 1206 - X7R")
      (fields (field (name "LCSC PART #") "C91151") (field (name "Comment") "1206B105K101NT"))
      (libsource (lib "JLC_PCB") (part "1206B105K101NT"))
    )
    (comp (ref "MT_C_CN")
      (value "1uF")
      (footprint "C_1206")
      (description "C - CAPACITOR - MLCC - 1uF - 100V - 1206 - X7R")
      (fields (field (name "LCSC PART #") "C91151") (field (name "Comment") "1206B105K101NT"))
      (libsource (lib "JLC_PCB") (part "1206B105K101NT"))
    )
    (comp (ref "MT_C_DA")
      (value "1uF")
      (footprint "C_1206")
      (description "C - CAPACITOR - MLCC - 1uF - 100V - 1206 - X7R")
      (fields (field (name "LCSC PART #") "C91151") (field (name "Comment") "1206B105K101NT"))
      (libsource (lib "JLC_PCB") (part "1206B105K101NT"))
    )
    (comp (ref "MT_C_DB")
      (value "1uF")
      (footprint "C_1206")
      (description "C - CAPACITOR - MLCC - 1uF - 100V - 1206 - X7R")
      (fields (field (name "LCSC PART #") "C91151") (field (name "Comment") "1206B105K101NT"))
      (libsource (lib "JLC_PCB") (part "1206B105K101NT"))
    )
    (comp (ref "MT_C_DC")
      (value "1uF")
      (footprint "C_1206")
      (description "C - CAPACITOR - MLCC - 1uF - 100V - 1206 - X7R")
      (fields (field (name "LCSC PART #") "C91151") (field (name "Comment") "1206B105K101NT"))
      (libsource (lib "JLC_PCB") (part "1206B105K101NT"))
    )
    (comp (ref "MT_C_DD")
      (value "1uF")
      (footprint "C_1206")
      (description "C - CAPACITOR - MLCC - 1uF - 100V - 1206 - X7R")
      (fields (field (name "LCSC PART #") "C91151") (field (name "Comment") "1206B105K101NT"))
      (libsource (lib "JLC_PCB") (part "1206B105K101NT"))
    )
    (comp (ref "MT_C_DE")
      (value "1uF")
      (footprint "C_1206")
      (description "C - CAPACITOR - MLCC - 1uF - 100V - 1206 - X7R")
      (fields (field (name "LCSC PART #") "C91151") (field (name "Comment") "1206B105K101NT"))
      (libsource (lib "JLC_PCB") (part "1206B105K101NT"))
    )
    (comp (ref "MT_C_DF")
      (value "1uF")
      (footprint "C_1206")
      (description "C - CAPACITOR - MLCC - 1uF - 100V - 1206 - X7R")
      (fields (field (name "LCSC PART #") "C91151") (field (name "Comment") "1206B105K101NT"))
      (libsource (lib "JLC_PCB") (part "1206B105K101NT"))
    )
    (comp (ref "MT_C_DG")
      (value "1uF")
      (footprint "C_1206")
      (description "C - CAPACITOR - MLCC - 1uF - 100V - 1206 - X7R")
      (fields (field (name "LCSC PART #") "C91151") (field (name "Comment") "1206B105K101NT"))
      (libsource (lib "JLC_PCB") (part "1206B105K101NT"))
    )
    (comp (ref "MT_C_DH")
      (value "1uF")
      (footprint "C_1206")
      (description "C - CAPACITOR - MLCC - 1uF - 100V - 1206 - X7R")
      (fields (field (name "LCSC PART #") "C91151") (field (name "Comment") "1206B105K101NT"))
      (libsource (lib "JLC_PCB") (part "1206B105K101NT"))
    )
    (comp (ref "MT_C_DI")
      (value "1uF")
      (footprint "C_1206")
      (description "C - CAPACITOR - MLCC - 1uF - 100V - 1206 - X7R")
      (fields (field (name "LCSC PART #") "C91151") (field (name "Comment") "1206B105K101NT"))
      (libsource (lib "JLC_PCB") (part "1206B105K101NT"))
    )
    (comp (ref "MT_C_DJ")
      (value "1uF")
      (footprint "C_1206")
      (description "C - CAPACITOR - MLCC - 1uF - 100V - 1206 - X7R")
      (fields (field (name "LCSC PART #") "C91151") (field (name "Comment") "1206B105K101NT"))
      (libsource (lib "JLC_PCB") (part "1206B105K101NT"))
    )
    (comp (ref "MT_C_DK")
      (value "1uF")
      (footprint "C_1206")
      (description "C - CAPACITOR - MLCC - 1uF - 100V - 1206 - X7R")
      (fields (field (name "LCSC PART #") "C91151") (field (name "Comment") "1206B105K101NT"))
      (libsource (lib "JLC_PCB") (part "1206B105K101NT"))
    )
    (comp (ref "MT_C_DL")
      (value "1uF")
      (footprint "C_1206")
      (description "C - CAPACITOR - MLCC - 1uF - 100V - 1206 - X7R")
      (fields (field (name "LCSC PART #") "C91151") (field (name "Comment") "1206B105K101NT"))
      (libsource (lib "JLC_PCB") (part "1206B105K101NT"))
    )
    (comp (ref "MT_C_EA")
      (value "1uF")
      (footprint "C_1206")
      (description "C - CAPACITOR - MLCC - 1uF - 100V - 1206 - X7R")
      (fields (field (name "LCSC PART #") "C91151") (field (name "Comment") "1206B105K101NT"))
      (libsource (lib "JLC_PCB") (part "1206B105K101NT"))
    )
    (comp (ref "MT_C_EB")
      (value "1uF")
      (footprint "C_1206")
      (description "C - CAPACITOR - MLCC - 1uF - 100V - 1206 - X7R")
      (fields (field (name "LCSC PART #") "C91151") (field (name "Comment") "1206B105K101NT"))
      (libsource (lib "JLC_PCB") (part "1206B105K101NT"))
    )
    (comp (ref "MT_C_EC")
      (value "1uF")
      (footprint "C_1206")
      (description "C - CAPACITOR - MLCC - 1uF - 100V - 1206 - X7R")
      (fields (field (name "LCSC PART #") "C91151") (field (name "Comment") "1206B105K101NT"))
      (libsource (lib "JLC_PCB") (part "1206B105K101NT"))
    )
    (comp (ref "MT_C_ED")
      (value "1uF")
      (footprint "C_1206")
      (description "C - CAPACITOR - MLCC - 1uF - 100V - 1206 - X7R")
      (fields (field (name "LCSC PART #") "C91151") (field (name "Comment") "1206B105K101NT"))
      (libsource (lib "JLC_PCB") (part "1206B105K101NT"))
    )
    (comp (ref "MT_C_EE")
      (value "1uF")
      (footprint "C_1206")
      (description "C - CAPACITOR - MLCC - 1uF - 100V - 1206 - X7R")
      (fields (field (name "LCSC PART #") "C91151") (field (name "Comment") "1206B105K101NT"))
      (libsource (lib "JLC_PCB") (part "1206B105K101NT"))
    )
    (comp (ref "MT_C_EF")
      (value "1uF")
      (footprint "C_1206")
      (description "C - CAPACITOR - MLCC - 1uF - 100V - 1206 - X7R")
      (fields (field (name "LCSC PART #") "C91151") (field (name "Comment") "1206B105K101NT"))
      (libsource (lib "JLC_PCB") (part "1206B105K101NT"))
    )
    (comp (ref "MT_C_EG")
      (value "1uF")
      (footprint "C_1206")
      (description "C - CAPACITOR - MLCC - 1uF - 100V - 1206 - X7R")
      (fields (field (name "LCSC PART #") "C91151") (field (name "Comment") "1206B105K101NT"))
      (libsource (lib "JLC_PCB") (part "1206B105K101NT"))
    )
    (comp (ref "MT_C_EH")
      (value "1uF")
      (footprint "C_1206")
      (description "C - CAPACITOR - MLCC - 1uF - 100V - 1206 - X7R")
      (fields (field (name "LCSC PART #") "C91151") (field (name "Comment") "1206B105K101NT"))
      (libsource (lib "JLC_PCB") (part "1206B105K101NT"))
    )
    (comp (ref "MT_C_EI")
      (value "1uF")
      (footprint "C_1206")
      (description "C - CAPACITOR - MLCC - 1uF - 100V - 1206 - X7R")
      (fields (field (name "LCSC PART #") "C91151") (field (name "Comment") "1206B105K101NT"))
      (libsource (lib "JLC_PCB") (part "1206B105K101NT"))
    )
    (comp (ref "MT_C_EJ")
      (value "1uF")
      (footprint "C_1206")
      (description "C - CAPACITOR - MLCC - 1uF - 100V - 1206 - X7R")
      (fields (field (name "LCSC PART #") "C91151") (field (name "Comment") "1206B105K101NT"))
      (libsource (lib "JLC_PCB") (part "1206B105K101NT"))
    )
    (comp (ref "MT_C_EK")
      (value "1uF")
      (footprint "C_1206")
      (description "C - CAPACITOR - MLCC - 1uF - 100V - 1206 - X7R")
      (fields (field (name "LCSC PART #") "C91151") (field (name "Comment") "1206B105K101NT"))
      (libsource (lib "JLC_PCB") (part "1206B105K101NT"))
    )
    (comp (ref "MT_C_EL")
      (value "1uF")
      (footprint "C_1206")
      (description "C - CAPACITOR - MLCC - 1uF - 100V - 1206 - X7R")
      (fields (field (name "LCSC PART #") "C91151") (field (name "Comment") "1206B105K101NT"))
      (libsource (lib "JLC_PCB") (part "1206B105K101NT"))
    )
    (comp (ref "MT_C_FA")
      (value "1uF")
      (footprint "C_1206")
      (description "C - CAPACITOR - MLCC - 1uF - 100V - 1206 - X7R")
      (fields (field (name "LCSC PART #") "C91151") (field (name "Comment") "1206B105K101NT"))
      (libsource (lib "JLC_PCB") (part "1206B105K101NT"))
    )
    (comp (ref "MT_C_FB")
      (value "1uF")
      (footprint "C_1206")
      (description "C - CAPACITOR - MLCC - 1uF - 100V - 1206 - X7R")
      (fields (field (name "LCSC PART #") "C91151") (field (name "Comment") "1206B105K101NT"))
      (libsource (lib "JLC_PCB") (part "1206B105K101NT"))
    )
    (comp (ref "MT_C_FC")
      (value "1uF")
      (footprint "C_1206")
      (description "C - CAPACITOR - MLCC - 1uF - 100V - 1206 - X7R")
      (fields (field (name "LCSC PART #") "C91151") (field (name "Comment") "1206B105K101NT"))
      (libsource (lib "JLC_PCB") (part "1206B105K101NT"))
    )
    (comp (ref "MT_C_FD")
      (value "1uF")
      (footprint "C_1206")
      (description "C - CAPACITOR - MLCC - 1uF - 100V - 1206 - X7R")
      (fields (field (name "LCSC PART #") "C91151") (field (name "Comment") "1206B105K101NT"))
      (libsource (lib "JLC_PCB") (part "1206B105K101NT"))
    )
    (comp (ref "MT_C_FE")
      (value "1uF")
      (footprint "C_1206")
      (description "C - CAPACITOR - MLCC - 1uF - 100V - 1206 - X7R")
      (fields (field (name "LCSC PART #") "C91151") (field (name "Comment") "1206B105K101NT"))
      (libsource (lib "JLC_PCB") (part "1206B105K101NT"))
    )
    (comp (ref "MT_C_FF")
      (value "1uF")
      (footprint "C_1206")
      (description "C - CAPACITOR - MLCC - 1uF - 100V - 1206 - X7R")
      (fields (field (name "LCSC PART #") "C91151") (field (name "Comment") "1206B105K101NT"))
      (libsource (lib "JLC_PCB") (part "1206B105K101NT"))
    )
    (comp (ref "MT_C_FG")
      (value "1uF")
      (footprint "C_1206")
      (description "C - CAPACITOR - MLCC - 1uF - 100V - 1206 - X7R")
      (fields (field (name "LCSC PART #") "C91151") (field (name "Comment") "1206B105K101NT"))
      (libsource (lib "JLC_PCB") (part "1206B105K101NT"))
    )
    (comp (ref "MT_C_FH")
      (value "1uF")
      (footprint "C_1206")
      (description "C - CAPACITOR - MLCC - 1uF - 100V - 1206 - X7R")
      (fields (field (name "LCSC PART #") "C91151") (field (name "Comment") "1206B105K101NT"))
      (libsource (lib "JLC_PCB") (part "1206B105K101NT"))
    )
    (comp (ref "MT_C_FI")
      (value "1uF")
      (footprint "C_1206")
      (description "C - CAPACITOR - MLCC - 1uF - 100V - 1206 - X7R")
      (fields (field (name "LCSC PART #") "C91151") (field (name "Comment") "1206B105K101NT"))
      (libsource (lib "JLC_PCB") (part "1206B105K101NT"))
    )
    (comp (ref "MT_C_FJ")
      (value "1uF")
      (footprint "C_1206")
      (description "C - CAPACITOR - MLCC - 1uF - 100V - 1206 - X7R")
      (fields (field (name "LCSC PART #") "C91151") (field (name "Comment") "1206B105K101NT"))
      (libsource (lib "JLC_PCB") (part "1206B105K101NT"))
    )
    (comp (ref "MT_C_FK")
      (value "1uF")
      (footprint "C_1206")
      (description "C - CAPACITOR - MLCC - 1uF - 100V - 1206 - X7R")
      (fields (field (name "LCSC PART #") "C91151") (field (name "Comment") "1206B105K101NT"))
      (libsource (lib "JLC_PCB") (part "1206B105K101NT"))
    )
    (comp (ref "MT_C_FL")
      (value "1uF")
      (footprint "C_1206")
      (description "C - CAPACITOR - MLCC - 1uF - 100V - 1206 - X7R")
      (fields (field (name "LCSC PART #") "C91151") (field (name "Comment") "1206B105K101NT"))
      (libsource (lib "JLC_PCB") (part "1206B105K101NT"))
    )
    (comp (ref "MT_C_HA")
      (value "10nF")
      (footprint "C_0402")
      (description "C - CAPACITOR - MLCC - 10nF - 50V - 0402")
      (fields (field (name "LCSC PART #") "C15195") (field (name "Comment") "CL05B103KB5NNNC"))
      (libsource (lib "JLC_PCB") (part "CL05B103KB5NNNC"))
    )
    (comp (ref "MT_C_HB")
      (value "10uF")
      (footprint "C_0402")
      (description "C - CAPACITOR - MLCC - 10uF - 6.3V - 0402")
      (fields (field (name "LCSC PART #") "C15525") (field (name "Comment") "CL05A106MQ5NUNC"))
      (libsource (lib "JLC_PCB") (part "CL05A106MQ5NUNC"))
    )
    (comp (ref "MT_C_HC")
      (value "10nF")
      (footprint "C_0402")
      (description "C - CAPACITOR - MLCC - 10nF - 50V - 0402")
      (fields (field (name "LCSC PART #") "C15195") (field (name "Comment") "CL05B103KB5NNNC"))
      (libsource (lib "JLC_PCB") (part "CL05B103KB5NNNC"))
    )
    (comp (ref "MT_C_HD")
      (value "10k")
      (footprint "R_0402")
      (description "R - RESISTOR - SMD - 10k - 1% - 0402")
      (fields (field (name "LCSC PART #") "C25744") (field (name "Comment") "0402WGF1002TCE"))
      (libsource (lib "JLC_PCB") (part "0402WGF1002TCE"))
    )
    (comp (ref "MT_C_HE")
      (value "10k")
      (footprint "R_0402")
      (description "R - RESISTOR - SMD - 10k - 1% - 0402")
      (fields (field (name "LCSC PART #") "C25744") (field (name "Comment") "0402WGF1002TCE"))
      (libsource (lib "JLC_PCB") (part "0402WGF1002TCE"))
    )
    (comp (ref "MT_C_HF")
      (value "10k")
      (footprint "R_0402")
      (description "R - RESISTOR - SMD - 10k - 1% - 0402")
      (fields (field (name "LCSC PART #") "C25744") (field (name "Comment") "0402WGF1002TCE"))
      (libsource (lib "JLC_PCB") (part "0402WGF1002TCE"))
    )
    (comp (ref "MT_C_HG")
      (value "10uF")
      (footprint "C_0402")
      (description "C - CAPACITOR - MLCC - 10uF - 6.3V - 0402")
      (fields (field (name "LCSC PART #") "C15525") (field (name "Comment") "CL05A106MQ5NUNC"))
      (libsource (lib "JLC_PCB") (part "CL05A106MQ5NUNC"))
    )
    (comp (ref "MT_C_HI")
      (value "10nF")
      (footprint "C_0402")
      (description "C - CAPACITOR - MLCC - 10nF - 50V - 0402")
      (fields (field (name "LCSC PART #") "C15195") (field (name "Comment") "CL05B103KB5NNNC"))
      (libsource (lib "JLC_PCB") (part "CL05B103KB5NNNC"))
    )
    (comp (ref "MT_C_HJ")
      (value "1uF")
      (footprint "C_0402")
      (description "C - CAPACITOR - MLCC - 1uF - 25V - 0402")
      (fields (field (name "LCSC PART #") "C52923") (field (name "Comment") "CL05A105KA5NQNC"))
      (libsource (lib "JLC_PCB") (part "CL05A105KA5NQNC"))
    )
    (comp (ref "MT_C_HK")
      (value "1uF")
      (footprint "C_0402")
      (description "C - CAPACITOR - MLCC - 1uF - 25V - 0402")
      (fields (field (name "LCSC PART #") "C52923") (field (name "Comment") "CL05A105KA5NQNC"))
      (libsource (lib "JLC_PCB") (part "CL05A105KA5NQNC"))
    )
    (comp (ref "MT_C_HL")
      (value "10nF")
      (footprint "C_0402")
      (description "C - CAPACITOR - MLCC - 10nF - 50V - 0402")
      (fields (field (name "LCSC PART #") "C15195") (field (name "Comment") "CL05B103KB5NNNC"))
      (libsource (lib "JLC_PCB") (part "CL05B103KB5NNNC"))
    )
    (comp (ref "MT_D_IN_A")
      (value "SS210")
      (footprint "DO-214AC")
      (description "D - DIODE - SCHOTTKY - 100V - 2A")
      (fields (field (name "LCSC PART #") "C14996"))
      (libsource (lib "JLC_PCB") (part "SS210"))
    )
    (comp (ref "MT_D_IN_B")
      (value "SS210")
      (footprint "DO-214AC")
      (description "D - DIODE - SCHOTTKY - 100V - 2A")
      (fields (field (name "LCSC PART #") "C14996"))
      (libsource (lib "JLC_PCB") (part "SS210"))
    )
    (comp (ref "MT_D_IN_C")
      (value "SS210")
      (footprint "DO-214AC")
      (description "D - DIODE - SCHOTTKY - 100V - 2A")
      (fields (field (name "LCSC PART #") "C14996"))
      (libsource (lib "JLC_PCB") (part "SS210"))
    )
    (comp (ref "MT_D_IN_D")
      (value "SS210")
      (footprint "DO-214AC")
      (description "D - DIODE - SCHOTTKY - 100V - 2A")
      (fields (field (name "LCSC PART #") "C14996"))
      (libsource (lib "JLC_PCB") (part "SS210"))
    )
    (comp (ref "MT_D_IN_E")
      (value "SS210")
      (footprint "DO-214AC")
      (description "D - DIODE - SCHOTTKY - 100V - 2A")
      (fields (field (name "LCSC PART #") "C14996"))
      (libsource (lib "JLC_PCB") (part "SS210"))
    )
    (comp (ref "MT_D_IN_F")
      (value "SS210")
      (footprint "DO-214AC")
      (description "D - DIODE - SCHOTTKY - 100V - 2A")
      (fields (field (name "LCSC PART #") "C14996"))
      (libsource (lib "JLC_PCB") (part "SS210"))
    )
    (comp (ref "MT_D_IN_G")
      (value "SS210")
      (footprint "DO-214AC")
      (description "D - DIODE - SCHOTTKY - 100V - 2A")
      (fields (field (name "LCSC PART #") "C14996"))
      (libsource (lib "JLC_PCB") (part "SS210"))
    )
    (comp (ref "MT_D_IN_H")
      (value "SS210")
      (footprint "DO-214AC")
      (description "D - DIODE - SCHOTTKY - 100V - 2A")
      (fields (field (name "LCSC PART #") "C14996"))
      (libsource (lib "JLC_PCB") (part "SS210"))
    )
    (comp (ref "MT_D_IN_I")
      (value "SS210")
      (footprint "DO-214AC")
      (description "D - DIODE - SCHOTTKY - 100V - 2A")
      (fields (field (name "LCSC PART #") "C14996"))
      (libsource (lib "JLC_PCB") (part "SS210"))
    )
    (comp (ref "MT_D_IN_J")
      (value "SS210")
      (footprint "DO-214AC")
      (description "D - DIODE - SCHOTTKY - 100V - 2A")
      (fields (field (name "LCSC PART #") "C14996"))
      (libsource (lib "JLC_PCB") (part "SS210"))
    )
    (comp (ref "MT_D_IN_K")
      (value "SS210")
      (footprint "DO-214AC")
      (description "D - DIODE - SCHOTTKY - 100V - 2A")
      (fields (field (name "LCSC PART #") "C14996"))
      (libsource (lib "JLC_PCB") (part "SS210"))
    )
    (comp (ref "MT_D_IN_L")
      (value "SS210")
      (footprint "DO-214AC")
      (description "D - DIODE - SCHOTTKY - 100V - 2A")
      (fields (field (name "LCSC PART #") "C14996"))
      (libsource (lib "JLC_PCB") (part "SS210"))
    )
    (comp (ref "MT_D_IN_M")
      (value "SS210")
      (footprint "DO-214AC")
      (description "D - DIODE - SCHOTTKY - 100V - 2A")
      (fields (field (name "LCSC PART #") "C14996"))
      (libsource (lib "JLC_PCB") (part "SS210"))
    )
    (comp (ref "MT_D_IN_N")
      (value "SS210")
      (footprint "DO-214AC")
      (description "D - DIODE - SCHOTTKY - 100V - 2A")
      (fields (field (name "LCSC PART #") "C14996"))
      (libsource (lib "JLC_PCB") (part "SS210"))
    )
    (comp (ref "MT_D_IN_O")
      (value "SS210")
      (footprint "DO-214AC")
      (description "D - DIODE - SCHOTTKY - 100V - 2A")
      (fields (field (name "LCSC PART #") "C14996"))
      (libsource (lib "JLC_PCB") (part "SS210"))
    )
    (comp (ref "MT_D_IN_P")
      (value "SS210")
      (footprint "DO-214AC")
      (description "D - DIODE - SCHOTTKY - 100V - 2A")
      (fields (field (name "LCSC PART #") "C14996"))
      (libsource (lib "JLC_PCB") (part "SS210"))
    )
    (comp (ref "MT_D_IN_Q")
      (value "SS210")
      (footprint "DO-214AC")
      (description "D - DIODE - SCHOTTKY - 100V - 2A")
      (fields (field (name "LCSC PART #") "C14996"))
      (libsource (lib "JLC_PCB") (part "SS210"))
    )
    (comp (ref "MT_D_IN_R")
      (value "SS210")
      (footprint "DO-214AC")
      (description "D - DIODE - SCHOTTKY - 100V - 2A")
      (fields (field (name "LCSC PART #") "C14996"))
      (libsource (lib "JLC_PCB") (part "SS210"))
    )
    (comp (ref "MT_D_IN_S")
      (value "SS210")
      (footprint "DO-214AC")
      (description "D - DIODE - SCHOTTKY - 100V - 2A")
      (fields (field (name "LCSC PART #") "C14996"))
      (libsource (lib "JLC_PCB") (part "SS210"))
    )
    (comp (ref "MT_D_IN_T")
      (value "SS210")
      (footprint "DO-214AC")
      (description "D - DIODE - SCHOTTKY - 100V - 2A")
      (fields (field (name "LCSC PART #") "C14996"))
      (libsource (lib "JLC_PCB") (part "SS210"))
    )
    (comp (ref "MT_D_IN_U")
      (value "SS210")
      (footprint "DO-214AC")
      (description "D - DIODE - SCHOTTKY - 100V - 2A")
      (fields (field (name "LCSC PART #") "C14996"))
      (libsource (lib "JLC_PCB") (part "SS210"))
    )
    (comp (ref "MT_D_IN_V")
      (value "SS210")
      (footprint "DO-214AC")
      (description "D - DIODE - SCHOTTKY - 100V - 2A")
      (fields (field (name "LCSC PART #") "C14996"))
      (libsource (lib "JLC_PCB") (part "SS210"))
    )
    (comp (ref "MT_D_IN_W")
      (value "SS210")
      (footprint "DO-214AC")
      (description "D - DIODE - SCHOTTKY - 100V - 2A")
      (fields (field (name "LCSC PART #") "C14996"))
      (libsource (lib "JLC_PCB") (part "SS210"))
    )
    (comp (ref "MT_D_IN_X")
      (value "SS210")
      (footprint "DO-214AC")
      (description "D - DIODE - SCHOTTKY - 100V - 2A")
      (fields (field (name "LCSC PART #") "C14996"))
      (libsource (lib "JLC_PCB") (part "SS210"))
    )
    (comp (ref "MT_D_KA")
      (value "1N4148WS")
      (footprint "SOD-323")
      (description "D - DIODE - FAST TRR - 100V - 150mA - 4ns")
      (fields (field (name "LCSC PART #") "C2128"))
      (libsource (lib "JLC_PCB") (part "1N4148WS"))
    )
    (comp (ref "MT_D_KB")
      (value "1N4148WS")
      (footprint "SOD-323")
      (description "D - DIODE - FAST TRR - 100V - 150mA - 4ns")
      (fields (field (name "LCSC PART #") "C2128"))
      (libsource (lib "JLC_PCB") (part "1N4148WS"))
    )
    (comp (ref "MT_KA")
      (value "G2RL-2-DC12")
      (footprint "RELAY_G2RL-2_12DC")
      (description "SW - Relay 12VDC 8A DPDT (( 29mm 12.7mm 15.7mm)) THT")
      (fields (field (name "LCSC PART #") "C61458") (field (name "MF") "Omron"))
      (libsource (lib "JLC_PCB") (part "G2RL-2-DC12"))
    )
    (comp (ref "MT_KB")
      (value "G2RL-2-DC12")
      (footprint "RELAY_G2RL-2_12DC")
      (description "SW - Relay 12VDC 8A DPDT (( 29mm 12.7mm 15.7mm)) THT")
      (fields (field (name "LCSC PART #") "C61458") (field (name "MF") "Omron"))
      (libsource (lib "JLC_PCB") (part "G2RL-2-DC12"))
    )
    (comp (ref "MT_L_TA")
      (value "10uH")
      (footprint "L_0603")
      (description "L - INDUCTOR - 10uH - 0603")
      (fields (field (name "LCSC PART #") "C1035") (field (name "Comment") "SDFL1608S100KTF"))
      (libsource (lib "JLC_PCB") (part "SDFL1608S100KTF"))
    )
    (comp (ref "MT_NT_A")
      (value "0")
      (footprint "NET_TIE")
      (description "R - Net Tie")
      (libsource (lib "JLC_PCB") (part "NET_TIE"))
    )
    (comp (ref "MT_Q1")
      (value "CRSS042N10N")
      (footprint "TO-263-3")
      (description "Q - TRANSISTOR - MOSFET (N) - 100V - 120A - 0.005R")
      (fields (field (name "LCSC PART #") "C410926"))
      (libsource (lib "JLC_PCB") (part "CRSS042N10N"))
    )
    (comp (ref "MT_Q2")
      (value "CRSS042N10N")
      (footprint "TO-263-3")
      (description "Q - TRANSISTOR - MOSFET (N) - 100V - 120A - 0.005R")
      (fields (field (name "LCSC PART #") "C410926"))
      (libsource (lib "JLC_PCB") (part "CRSS042N10N"))
    )
    (comp (ref "MT_Q3")
      (value "CRSS042N10N")
      (footprint "TO-263-3")
      (description "Q - TRANSISTOR - MOSFET (N) - 100V - 120A - 0.005R")
      (fields (field (name "LCSC PART #") "C410926"))
      (libsource (lib "JLC_PCB") (part "CRSS042N10N"))
    )
    (comp (ref "MT_Q4")
      (value "CRSS042N10N")
      (footprint "TO-263-3")
      (description "Q - TRANSISTOR - MOSFET (N) - 100V - 120A - 0.005R")
      (fields (field (name "LCSC PART #") "C410926"))
      (libsource (lib "JLC_PCB") (part "CRSS042N10N"))
    )
    (comp (ref "MT_Q_KA")
      (value "2N7002")
      (footprint "TO-236AB")
      (description "Q - TRANSISTOR - MOSFET (N) - 60V - 200mW")
      (fields (field (name "LCSC PART #") "C8545"))
      (libsource (lib "JLC_PCB") (part "2N7002"))
    )
    (comp (ref "MT_Q_KB")
      (value "2N7002")
      (footprint "TO-236AB")
      (description "Q - TRANSISTOR - MOSFET (N) - 60V - 200mW")
      (fields (field (name "LCSC PART #") "C8545"))
      (libsource (lib "JLC_PCB") (part "2N7002"))
    )
    (comp (ref "MT_RT_TA")
      (value "10k")
      (footprint "R_0402")
      (description "RT - NTC THERMISTOR - 10k - 1% - 0402")
      (fields (field (name "LCSC PART #") "C77131") (field (name "Comment") "NCP15XH103F03RC"))
      (libsource (lib "JLC_PCB") (part "NCP15XH103F03RC"))
    )
    (comp (ref "MT_RT_TB")
      (value "10k")
      (footprint "R_0402")
      (description "RT - NTC THERMISTOR - 10k - 1% - 0402")
      (fields (field (name "LCSC PART #") "C77131") (field (name "Comment") "NCP15XH103F03RC"))
      (libsource (lib "JLC_PCB") (part "NCP15XH103F03RC"))
    )
    (comp (ref "MT_RT_TC")
      (value "10k")
      (footprint "R_0402")
      (description "RT - NTC THERMISTOR - 10k - 1% - 0402")
      (fields (field (name "LCSC PART #") "C77131") (field (name "Comment") "NCP15XH103F03RC"))
      (libsource (lib "JLC_PCB") (part "NCP15XH103F03RC"))
    )
    (comp (ref "MT_RT_TD")
      (value "10k")
      (footprint "R_0402")
      (description "RT - NTC THERMISTOR - 10k - 1% - 0402")
      (fields (field (name "LCSC PART #") "C77131") (field (name "Comment") "NCP15XH103F03RC"))
      (libsource (lib "JLC_PCB") (part "NCP15XH103F03RC"))
    )
    (comp (ref "MT_RT_TE")
      (value "10k")
      (footprint "R_0402")
      (description "RT - NTC THERMISTOR - 10k - 1% - 0402")
      (fields (field (name "LCSC PART #") "C77131") (field (name "Comment") "NCP15XH103F03RC"))
      (libsource (lib "JLC_PCB") (part "NCP15XH103F03RC"))
    )
    (comp (ref "MT_RT_TG")
      (value "10k")
      (footprint "R_0402")
      (description "RT - NTC THERMISTOR - 10k - 1% - 0402")
      (fields (field (name "LCSC PART #") "C77131") (field (name "Comment") "NCP15XH103F03RC"))
      (libsource (lib "JLC_PCB") (part "NCP15XH103F03RC"))
    )
    (comp (ref "MT_RT_TJ")
      (value "10k")
      (footprint "R_0402")
      (description "RT - NTC THERMISTOR - 10k - 1% - 0402")
      (fields (field (name "LCSC PART #") "C77131") (field (name "Comment") "NCP15XH103F03RC"))
      (libsource (lib "JLC_PCB") (part "NCP15XH103F03RC"))
    )
    (comp (ref "MT_RT_TK")
      (value "10k")
      (footprint "R_0402")
      (description "RT - NTC THERMISTOR - 10k - 1% - 0402")
      (fields (field (name "LCSC PART #") "C77131") (field (name "Comment") "NCP15XH103F03RC"))
      (libsource (lib "JLC_PCB") (part "NCP15XH103F03RC"))
    )
    (comp (ref "MT_R_FT")
      (value "0R")
      (footprint "R_0402")
      (description "R - RESISTOR - SMD - 0R - 1% - 0402")
      (fields (field (name "LCSC PART #") "C17168") (field (name "Comment") "0402WGF0000TCE"))
      (libsource (lib "JLC_PCB") (part "0402WGF0000TCE"))
    )
    (comp (ref "MT_R_FV")
      (value "0R")
      (footprint "R_0402")
      (description "R - RESISTOR - SMD - 0R - 1% - 0402")
      (fields (field (name "LCSC PART #") "C17168") (field (name "Comment") "0402WGF0000TCE"))
      (libsource (lib "JLC_PCB") (part "0402WGF0000TCE"))
    )
    (comp (ref "MT_R_TA")
      (value "10k")
      (footprint "R_0402")
      (description "R - RESISTOR - SMD - 10k - 1% - 0402")
      (fields (field (name "LCSC PART #") "C25744") (field (name "Comment") "0402WGF1002TCE"))
      (libsource (lib "JLC_PCB") (part "0402WGF1002TCE"))
    )
    (comp (ref "MT_R_TB")
      (value "10k")
      (footprint "R_0402")
      (description "R - RESISTOR - SMD - 10k - 1% - 0402")
      (fields (field (name "LCSC PART #") "C25744") (field (name "Comment") "0402WGF1002TCE"))
      (libsource (lib "JLC_PCB") (part "0402WGF1002TCE"))
    )
    (comp (ref "MT_R_TC")
      (value "10k")
      (footprint "R_0402")
      (description "R - RESISTOR - SMD - 10k - 1% - 0402")
      (fields (field (name "LCSC PART #") "C25744") (field (name "Comment") "0402WGF1002TCE"))
      (libsource (lib "JLC_PCB") (part "0402WGF1002TCE"))
    )
    (comp (ref "MT_R_TD")
      (value "10k")
      (footprint "R_0402")
      (description "R - RESISTOR - SMD - 10k - 1% - 0402")
      (fields (field (name "LCSC PART #") "C25744") (field (name "Comment") "0402WGF1002TCE"))
      (libsource (lib "JLC_PCB") (part "0402WGF1002TCE"))
    )
    (comp (ref "MT_R_TE")
      (value "10k")
      (footprint "R_0402")
      (description "R - RESISTOR - SMD - 10k - 1% - 0402")
      (fields (field (name "LCSC PART #") "C25744") (field (name "Comment") "0402WGF1002TCE"))
      (libsource (lib "JLC_PCB") (part "0402WGF1002TCE"))
    )
    (comp (ref "MT_R_TG")
      (value "10k")
      (footprint "R_0402")
      (description "R - RESISTOR - SMD - 10k - 1% - 0402")
      (fields (field (name "LCSC PART #") "C25744") (field (name "Comment") "0402WGF1002TCE"))
      (libsource (lib "JLC_PCB") (part "0402WGF1002TCE"))
    )
    (comp (ref "MT_R_TJ")
      (value "10k")
      (footprint "R_0402")
      (description "R - RESISTOR - SMD - 10k - 1% - 0402")
      (fields (field (name "LCSC PART #") "C25744") (field (name "Comment") "0402WGF1002TCE"))
      (libsource (lib "JLC_PCB") (part "0402WGF1002TCE"))
    )
    (comp (ref "MT_R_TK")
      (value "10k")
      (footprint "R_0402")
      (description "R - RESISTOR - SMD - 10k - 1% - 0402")
      (fields (field (name "LCSC PART #") "C25744") (field (name "Comment") "0402WGF1002TCE"))
      (libsource (lib "JLC_PCB") (part "0402WGF1002TCE"))
    )
    (comp (ref "MT_R_TW")
      (value "5.1k")
      (footprint "R_0402")
      (description "R - RESISTOR - SMD - 5.1k - 1% - 0402")
      (fields (field (name "LCSC PART #") "C25905") (field (name "Comment") "0402WGF5101TCE"))
      (libsource (lib "JLC_PCB") (part "0402WGF5101TCE"))
    )
    (comp (ref "MT_R_TX")
      (value "5.1k")
      (footprint "R_0402")
      (description "R - RESISTOR - SMD - 5.1k - 1% - 0402")
      (fields (field (name "LCSC PART #") "C25905") (field (name "Comment") "0402WGF5101TCE"))
      (libsource (lib "JLC_PCB") (part "0402WGF5101TCE"))
    )
    (comp (ref "MT_R_TY")
      (value "5.1k")
      (footprint "R_0402")
      (description "R - RESISTOR - SMD - 5.1k - 1% - 0402")
      (fields (field (name "LCSC PART #") "C25905") (field (name "Comment") "0402WGF5101TCE"))
      (libsource (lib "JLC_PCB") (part "0402WGF5101TCE"))
    )
    (comp (ref "MT_R_TZ")
      (value "5.1k")
      (footprint "R_0402")
      (description "R - RESISTOR - SMD - 5.1k - 1% - 0402")
      (fields (field (name "LCSC PART #") "C25905") (field (name "Comment") "0402WGF5101TCE"))
      (libsource (lib "JLC_PCB") (part "0402WGF5101TCE"))
    )
    (comp (ref "MT_U_B")
      (value "SM72295MAX")
      (footprint "M28B_M")
      (description "Photovoltaic Full Bridge Driver")
      (fields (field (name "MANUFACTURER") "National Semiconductor") (field (name "PARTNUMBER") "SM72295"))
      (libsource (lib "JLC_PCB") (part "SM72295"))
    )
    (comp (ref "MT_U_H")
      (value "SM72442MTE/NOPB")
      (footprint "MTC28_L")
      (description "Programmable Maximum Power Point Tracking Controller for Photovoltaic Solar Panels")
      (fields (field (name "MANUFACTURER") "National Semiconductor") (field (name "PARTNUMBER") "SM72442"))
      (libsource (lib "SM_ICs") (part "SM72442"))
    )
    (comp (ref "MT_U_T")
      (value "74HC4067PW,118")
      (footprint "SILICON:TSSOP-24-P0.65MM-W4.4MM")
      (description "U - IC -16 Port Analog MUX")
      (fields (field (name "LCSC PART #") "C179326"))
      (libsource (lib "JLC_PCB") (part "74HC4067PW,118"))
    )
    (comp (ref "Qscl")
      (value "2N7002")
      (footprint "TO-236AB")
      (description "Q - TRANSISTOR - MOSFET (N) - 60V - 200mW")
      (fields (field (name "LCSC PART #") "C8545"))
      (libsource (lib "JLC_PCB") (part "2N7002"))
    )
    (comp (ref "Qsda")
      (value "2N7002")
      (footprint "TO-236AB")
      (description "Q - TRANSISTOR - MOSFET (N) - 60V - 200mW")
      (fields (field (name "LCSC PART #") "C8545"))
      (libsource (lib "JLC_PCB") (part "2N7002"))
    )
    (comp (ref "Qsu")
      (value "MMBT3904")
      (footprint "TO-236AB")
      (description "Q - TRANSISTOR - BJT - NPN - 40V 200mA")
      (fields (field (name "LCSC PART #") "C20526"))
      (libsource (lib "JLC_PCB") (part "MMBT3904"))
    )
    (comp (ref "Q_LEDA")
      (value "2N7002")
      (footprint "TO-236AB")
      (description "Q - TRANSISTOR - MOSFET (N) - 60V - 200mW")
      (fields (field (name "LCSC PART #") "C8545"))
      (libsource (lib "JLC_PCB") (part "2N7002"))
    )
    (comp (ref "Q_LEDB")
      (value "2N7002")
      (footprint "TO-236AB")
      (description "Q - TRANSISTOR - MOSFET (N) - 60V - 200mW")
      (fields (field (name "LCSC PART #") "C8545"))
      (libsource (lib "JLC_PCB") (part "2N7002"))
    )
    (comp (ref "Q_LEDVSS")
      (value "2N7002")
      (footprint "TO-236AB")
      (description "Q - TRANSISTOR - MOSFET (N) - 60V - 200mW")
      (fields (field (name "LCSC PART #") "C8545"))
      (libsource (lib "JLC_PCB") (part "2N7002"))
    )
    (comp (ref "R1")
      (value "1m")
      (footprint "R_2512")
      (description "R - RESISTOR - SMD - 0.005R - 1% - 2512 - 2W")
      (fields (field (name "LCSC PART #") "C371096") (field (name "POWER") "2W"))
      (libsource (lib "JLC_PCB") (part "FMF25FPJR005-LH"))
    )
    (comp (ref "R10")
      (value "1m")
      (footprint "R_2512")
      (description "R - RESISTOR - SMD - 0.005R - 1% - 2512 - 2W")
      (fields (field (name "LCSC PART #") "C371096") (field (name "POWER") "2W"))
      (libsource (lib "JLC_PCB") (part "FMF25FPJR005-LH"))
    )
    (comp (ref "R21")
      (value "47R")
      (footprint "R_0402")
      (description "R - RESISTOR - SMD - 47R - 1% - 0402")
      (fields (field (name "LCSC PART #") "C25118") (field (name "Comment") "0402WGF470JTCE"))
      (libsource (lib "JLC_PCB") (part "0402WGF470JTCE"))
    )
    (comp (ref "R26")
      (value "10k")
      (footprint "R_0402")
      (description "R - RESISTOR - SMD - 10k - 1% - 0402")
      (fields (field (name "LCSC PART #") "C25744") (field (name "Comment") "0402WGF1002TCE"))
      (libsource (lib "JLC_PCB") (part "0402WGF1002TCE"))
    )
    (comp (ref "R28")
      (value "33k")
      (footprint "R_0402")
      (description "R - RESISTOR - SMD - 33k - 1% - 0402")
      (fields (field (name "LCSC PART #") "C25779") (field (name "Comment") "0402WGF3302TCE"))
      (libsource (lib "JLC_PCB") (part "0402WGF3302TCE"))
    )
    (comp (ref "R29")
      (value "0R")
      (footprint "R_0402")
      (description "R - RESISTOR - SMD - 0R - 1% - 0402")
      (fields (field (name "LCSC PART #") "C17168") (field (name "Comment") "0402WGF0000TCE"))
      (libsource (lib "JLC_PCB") (part "0402WGF0000TCE"))
    )
    (comp (ref "R30")
      (value "0R")
      (footprint "R_0402")
      (description "R - RESISTOR - SMD - 0R - 1% - 0402")
      (fields (field (name "LCSC PART #") "C17168") (field (name "Comment") "0402WGF0000TCE"))
      (libsource (lib "JLC_PCB") (part "0402WGF0000TCE"))
    )
    (comp (ref "R31")
      (value "0R")
      (footprint "R_0402")
      (description "R - RESISTOR - SMD - 0R - 1% - 0402")
      (fields (field (name "LCSC PART #") "C17168") (field (name "Comment") "0402WGF0000TCE"))
      (libsource (lib "JLC_PCB") (part "0402WGF0000TCE"))
    )
    (comp (ref "R38")
      (value "4.7k")
      (footprint "R_0402")
      (description "R - RESISTOR - SMD - 4.7k - 1% - 0402")
      (fields (field (name "LCSC PART #") "C25900") (field (name "Comment") "0402WGF4701TCE"))
      (libsource (lib "JLC_PCB") (part "0402WGF4701TCE"))
    )
    (comp (ref "R39")
      (value "1M")
      (footprint "R_0402")
      (description "R - RESISTOR - SMD - 1M - 1% - 0402")
      (fields (field (name "LCSC PART #") "C26083") (field (name "Comment") "0402WGF1004TCE"))
      (libsource (lib "JLC_PCB") (part "0402WGF1004TCE"))
    )
    (comp (ref "R40")
      (value "1M")
      (footprint "R_0402")
      (description "R - RESISTOR - SMD - 1M - 1% - 0402")
      (fields (field (name "LCSC PART #") "C26083") (field (name "Comment") "0402WGF1004TCE"))
      (libsource (lib "JLC_PCB") (part "0402WGF1004TCE"))
    )
    (comp (ref "R41")
      (value "1M")
      (footprint "R_0402")
      (description "R - RESISTOR - SMD - 1M - 1% - 0402")
      (fields (field (name "LCSC PART #") "C26083") (field (name "Comment") "0402WGF1004TCE"))
      (libsource (lib "JLC_PCB") (part "0402WGF1004TCE"))
    )
    (comp (ref "R100")
      (value "100R")
      (footprint "R_0402")
      (description "R - RESISTOR - SMD - 100R - 1% - 0402")
      (fields (field (name "LCSC PART #") "C25076") (field (name "Comment") "0402WGF1000TCE"))
      (libsource (lib "JLC_PCB") (part "0402WGF1000TCE"))
    )
    (comp (ref "R101")
      (value "100R")
      (footprint "R_0402")
      (description "R - RESISTOR - SMD - 100R - 1% - 0402")
      (fields (field (name "LCSC PART #") "C25076") (field (name "Comment") "0402WGF1000TCE"))
      (libsource (lib "JLC_PCB") (part "0402WGF1000TCE"))
    )
    (comp (ref "R102")
      (value "100R")
      (footprint "R_0402")
      (description "R - RESISTOR - SMD - 100R - 1% - 0402")
      (fields (field (name "LCSC PART #") "C25076") (field (name "Comment") "0402WGF1000TCE"))
      (libsource (lib "JLC_PCB") (part "0402WGF1000TCE"))
    )
    (comp (ref "R103")
      (value "100R")
      (footprint "R_0402")
      (description "R - RESISTOR - SMD - 100R - 1% - 0402")
      (fields (field (name "LCSC PART #") "C25076") (field (name "Comment") "0402WGF1000TCE"))
      (libsource (lib "JLC_PCB") (part "0402WGF1000TCE"))
    )
    (comp (ref "R110")
      (value "10R")
      (footprint "R_1206")
      (description "R - RESISTOR - SMD - 10R - 1% - 1206")
      (fields (field (name "LCSC PART #") "C17903") (field (name "Comment") "1206W4F100JT5E"))
      (libsource (lib "JLC_PCB") (part "1206W4F100JT5E"))
    )
    (comp (ref "R140")
      (value "10R")
      (footprint "R_1206")
      (description "R - RESISTOR - SMD - 10R - 1% - 1206")
      (fields (field (name "LCSC PART #") "C17903") (field (name "Comment") "1206W4F100JT5E"))
      (libsource (lib "JLC_PCB") (part "1206W4F100JT5E"))
    )
    (comp (ref "R160")
      (value "0R")
      (footprint "R_0402")
      (description "R - RESISTOR - SMD - 0R - 1% - 0402")
      (fields (field (name "LCSC PART #") "C17168") (field (name "Comment") "0402WGF0000TCE"))
      (libsource (lib "JLC_PCB") (part "0402WGF0000TCE"))
    )
    (comp (ref "Ragnd")
      (value "0R")
      (footprint "R_0402")
      (description "R - RESISTOR - SMD - 0R - 1% - 0402")
      (fields (field (name "LCSC PART #") "C17168") (field (name "Comment") "0402WGF0000TCE"))
      (libsource (lib "JLC_PCB") (part "0402WGF0000TCE"))
    )
    (comp (ref "Rbg1a")
      (value "1R")
      (footprint "R_0603")
      (description "R - RESISTOR - SMD - 1R - 1% -  0603")
      (fields (field (name "LCSC PART #") "C22936") (field (name "Comment") "0603WAF100KT5E"))
      (libsource (lib "JLC_PCB") (part "0603WAF100KT5E"))
    )
    (comp (ref "Rbg1s")
      (value "10k")
      (footprint "R_0402")
      (description "R - RESISTOR - SMD - 10k - 1% - 0402")
      (fields (field (name "LCSC PART #") "C25744") (field (name "Comment") "0402WGF1002TCE"))
      (libsource (lib "JLC_PCB") (part "0402WGF1002TCE"))
    )
    (comp (ref "Rbg2a")
      (value "1R")
      (footprint "R_0603")
      (description "R - RESISTOR - SMD - 1R - 1% -  0603")
      (fields (field (name "LCSC PART #") "C22936") (field (name "Comment") "0603WAF100KT5E"))
      (libsource (lib "JLC_PCB") (part "0603WAF100KT5E"))
    )
    (comp (ref "Rbg2s")
      (value "10k")
      (footprint "R_0402")
      (description "R - RESISTOR - SMD - 10k - 1% - 0402")
      (fields (field (name "LCSC PART #") "C25744") (field (name "Comment") "0402WGF1002TCE"))
      (libsource (lib "JLC_PCB") (part "0402WGF1002TCE"))
    )
    (comp (ref "Rbin")
      (value "10R")
      (footprint "R_0402")
      (description "R - RESISTOR - SMD - 10R - 1% - 0402")
      (fields (field (name "LCSC PART #") "C25077") (field (name "Comment") "0402WGF100JTCE"))
      (libsource (lib "JLC_PCB") (part "0402WGF100JTCE"))
    )
    (comp (ref "Rbout")
      (value "10R")
      (footprint "R_0402")
      (description "R - RESISTOR - SMD - 10R - 1% - 0402")
      (fields (field (name "LCSC PART #") "C25077") (field (name "Comment") "0402WGF100JTCE"))
      (libsource (lib "JLC_PCB") (part "0402WGF100JTCE"))
    )
    (comp (ref "Riin")
      (value "56k")
      (footprint "R_0402")
      (description "R - RESISTOR - SMD - 56k - 1% - 0402")
      (fields (field (name "LCSC PART #") "C25796") (field (name "Comment") "0402WGF5602TCE"))
      (libsource (lib "JLC_PCB") (part "0402WGF5602TCE"))
    )
    (comp (ref "Riinsns1")
      (value "680R")
      (footprint "R_0603")
      (description "R - RESISTOR - SMD - 680R - 1% - 0603")
      (fields (field (name "LCSC PART #") "C23228") (field (name "Comment") "0603WAF6800T5E"))
      (libsource (lib "JLC_PCB") (part "0603WAF6800T5E"))
    )
    (comp (ref "Riinsns2")
      (value "680R")
      (footprint "R_0603")
      (description "R - RESISTOR - SMD - 680R - 1% - 0603")
      (fields (field (name "LCSC PART #") "C23228") (field (name "Comment") "0603WAF6800T5E"))
      (libsource (lib "JLC_PCB") (part "0603WAF6800T5E"))
    )
    (comp (ref "Riout")
      (value "56k")
      (footprint "R_0402")
      (description "R - RESISTOR - SMD - 56k - 1% - 0402")
      (fields (field (name "LCSC PART #") "C25796") (field (name "Comment") "0402WGF5602TCE"))
      (libsource (lib "JLC_PCB") (part "0402WGF5602TCE"))
    )
    (comp (ref "Rioutsns1")
      (value "680R")
      (footprint "R_0603")
      (description "R - RESISTOR - SMD - 680R - 1% - 0603")
      (fields (field (name "LCSC PART #") "C23228") (field (name "Comment") "0603WAF6800T5E"))
      (libsource (lib "JLC_PCB") (part "0603WAF6800T5E"))
    )
    (comp (ref "Rioutsns2")
      (value "680R")
      (footprint "R_0603")
      (description "R - RESISTOR - SMD - 680R - 1% - 0603")
      (fields (field (name "LCSC PART #") "C23228") (field (name "Comment") "0603WAF6800T5E"))
      (libsource (lib "JLC_PCB") (part "0603WAF6800T5E"))
    )
    (comp (ref "Rnc4")
      (value "56k")
      (footprint "R_0402")
      (description "R - RESISTOR - SMD - 56k - 1% - 0402")
      (fields (field (name "LCSC PART #") "C25796") (field (name "Comment") "0402WGF5602TCE"))
      (libsource (lib "JLC_PCB") (part "0402WGF5602TCE"))
    )
    (comp (ref "Rovs")
      (value "10k")
      (footprint "R_0402")
      (description "R - RESISTOR - SMD - 10k - 1% - 0402")
      (fields (field (name "LCSC PART #") "C25744") (field (name "Comment") "0402WGF1002TCE"))
      (libsource (lib "JLC_PCB") (part "0402WGF1002TCE"))
    )
    (comp (ref "Rpm")
      (value "56k")
      (footprint "R_0402")
      (description "R - RESISTOR - SMD - 56k - 1% - 0402")
      (fields (field (name "LCSC PART #") "C25796") (field (name "Comment") "0402WGF5602TCE"))
      (libsource (lib "JLC_PCB") (part "0402WGF5602TCE"))
    )
    (comp (ref "Rscl")
      (value "10k")
      (footprint "R_0402")
      (description "R - RESISTOR - SMD - 10k - 1% - 0402")
      (fields (field (name "LCSC PART #") "C25744") (field (name "Comment") "0402WGF1002TCE"))
      (libsource (lib "JLC_PCB") (part "0402WGF1002TCE"))
    )
    (comp (ref "Rsda")
      (value "10k")
      (footprint "R_0402")
      (description "R - RESISTOR - SMD - 10k - 1% - 0402")
      (fields (field (name "LCSC PART #") "C25744") (field (name "Comment") "0402WGF1002TCE"))
      (libsource (lib "JLC_PCB") (part "0402WGF1002TCE"))
    )
    (comp (ref "Rsu1")
      (value "100k")
      (footprint "R_0402")
      (description "R - RESISTOR - SMD - 100k - 1% -  0402")
      (fields (field (name "LCSC PART #") "C25741") (field (name "Comment") "0402WGF1003TCE"))
      (libsource (lib "JLC_PCB") (part "0402WGF1003TCE"))
    )
    (comp (ref "Rsu2")
      (value "270k")
      (footprint "R_0603")
      (description "R - RESISTOR - SMD - 270k - 1% - 0603")
      (fields (field (name "LCSC PART #") "C22965") (field (name "Comment") "0603WAF2703T5E"))
      (libsource (lib "JLC_PCB") (part "0603WAF2703T5E"))
    )
    (comp (ref "Rsu3")
      (value "270k")
      (footprint "R_0603")
      (description "R - RESISTOR - SMD - 270k - 1% - 0603")
      (fields (field (name "LCSC PART #") "C22965") (field (name "Comment") "0603WAF2703T5E"))
      (libsource (lib "JLC_PCB") (part "0603WAF2703T5E"))
    )
    (comp (ref "Rsu4")
      (value "330K")
      (footprint "R_0402")
      (description "R - RESISTOR - SMD - 330k - 1% - 0402")
      (fields (field (name "LCSC PART #") "C25778") (field (name "Comment") "0402WGF3303TCE"))
      (libsource (lib "JLC_PCB") (part "0402WGF3303TCE"))
    )
    (comp (ref "Rsu5")
      (value "1k")
      (footprint "R_0402")
      (description "R - RESISTOR - SMD - 1k - 1% - 0402")
      (fields (field (name "LCSC PART #") "C11702") (field (name "Comment") "0402WGF1001TCE"))
      (libsource (lib "JLC_PCB") (part "0402WGF1001TCE"))
    )
    (comp (ref "Rtg1a")
      (value "1R")
      (footprint "R_0603")
      (description "R - RESISTOR - SMD - 1R - 1% -  0603")
      (fields (field (name "LCSC PART #") "C22936") (field (name "Comment") "0603WAF100KT5E"))
      (libsource (lib "JLC_PCB") (part "0603WAF100KT5E"))
    )
    (comp (ref "Rtg1s")
      (value "10k")
      (footprint "R_0402")
      (description "R - RESISTOR - SMD - 10k - 1% - 0402")
      (fields (field (name "LCSC PART #") "C25744") (field (name "Comment") "0402WGF1002TCE"))
      (libsource (lib "JLC_PCB") (part "0402WGF1002TCE"))
    )
    (comp (ref "Rtg2a")
      (value "1R")
      (footprint "R_0603")
      (description "R - RESISTOR - SMD - 1R - 1% -  0603")
      (fields (field (name "LCSC PART #") "C22936") (field (name "Comment") "0603WAF100KT5E"))
      (libsource (lib "JLC_PCB") (part "0603WAF100KT5E"))
    )
    (comp (ref "Rtg2s")
      (value "10k")
      (footprint "R_0402")
      (description "R - RESISTOR - SMD - 10k - 1% - 0402")
      (fields (field (name "LCSC PART #") "C25744") (field (name "Comment") "0402WGF1002TCE"))
      (libsource (lib "JLC_PCB") (part "0402WGF1002TCE"))
    )
    (comp (ref "Rvinb")
      (value "10k")
      (footprint "R_0603")
      (description "R - RESISTOR - SMD - 10k - 1% - 0603")
      (fields (field (name "LCSC PART #") "C25804") (field (name "Comment") "0603WAF1002T5E"))
      (libsource (lib "JLC_PCB") (part "0603WAF1002T5E"))
    )
    (comp (ref "Rvint")
      (value "100k")
      (footprint "R_0603")
      (description "R - RESISTOR - SMD - 100k - 1% -  0603")
      (fields (field (name "LCSC PART #") "C22936") (field (name "Comment") "0603WAF1003T5E"))
      (libsource (lib "JLC_PCB") (part "0603WAF100KT5E"))
    )
    (comp (ref "Rvoutb")
      (value "10k")
      (footprint "R_0603")
      (description "R - RESISTOR - SMD - 10k - 1% - 0603")
      (fields (field (name "LCSC PART #") "C25804") (field (name "Comment") "0603WAF1002T5E"))
      (libsource (lib "JLC_PCB") (part "0603WAF1002T5E"))
    )
    (comp (ref "Rvoutt")
      (value "100k")
      (footprint "R_0603")
      (description "R - RESISTOR - SMD - 100k - 1% -  0603")
      (fields (field (name "LCSC PART #") "C22936") (field (name "Comment") "0603WAF1003T5E"))
      (libsource (lib "JLC_PCB") (part "0603WAF100KT5E"))
    )
    (comp (ref "R_1A_a")
      (value "47k")
      (footprint "R_0402")
      (description "R - RESISTOR - SMD - 47k - 1% - 0402")
      (fields (field (name "LCSC PART #") "C25792") (field (name "Comment") "0402WGF4702TCE"))
      (libsource (lib "JLC_PCB") (part "0402WGF4702TCE"))
    )
    (comp (ref "R_1A_b")
      (value "47k")
      (footprint "R_0402")
      (description "R - RESISTOR - SMD - 47k - 1% - 0402")
      (fields (field (name "LCSC PART #") "C25792") (field (name "Comment") "0402WGF4702TCE"))
      (libsource (lib "JLC_PCB") (part "0402WGF4702TCE"))
    )
    (comp (ref "R_1A_c")
      (value "100k")
      (footprint "R_0402")
      (description "R - RESISTOR - SMD - 100k - 1% -  0402")
      (fields (field (name "LCSC PART #") "C25741") (field (name "Comment") "0402WGF1003TCE"))
      (libsource (lib "JLC_PCB") (part "0402WGF1003TCE"))
    )
    (comp (ref "R_1B_a")
      (value "47k")
      (footprint "R_0402")
      (description "R - RESISTOR - SMD - 47k - 1% - 0402")
      (fields (field (name "LCSC PART #") "C25792") (field (name "Comment") "0402WGF4702TCE"))
      (libsource (lib "JLC_PCB") (part "0402WGF4702TCE"))
    )
    (comp (ref "R_1B_b")
      (value "47k")
      (footprint "R_0402")
      (description "R - RESISTOR - SMD - 47k - 1% - 0402")
      (fields (field (name "LCSC PART #") "C25792") (field (name "Comment") "0402WGF4702TCE"))
      (libsource (lib "JLC_PCB") (part "0402WGF4702TCE"))
    )
    (comp (ref "R_1B_c")
      (value "100k")
      (footprint "R_0402")
      (description "R - RESISTOR - SMD - 100k - 1% -  0402")
      (fields (field (name "LCSC PART #") "C25741") (field (name "Comment") "0402WGF1003TCE"))
      (libsource (lib "JLC_PCB") (part "0402WGF1003TCE"))
    )
    (comp (ref "R_LED_A")
      (value "0R")
      (footprint "R_0402")
      (description "R - RESISTOR - SMD - 0R - 1% - 0402")
      (fields (field (name "LCSC PART #") "C17168") (field (name "Comment") "0402WGF0000TCE"))
      (libsource (lib "JLC_PCB") (part "0402WGF0000TCE"))
    )
    (comp (ref "R_LED_B")
      (value "0R")
      (footprint "R_0402")
      (description "R - RESISTOR - SMD - 0R - 1% - 0402")
      (fields (field (name "LCSC PART #") "C17168") (field (name "Comment") "0402WGF0000TCE"))
      (libsource (lib "JLC_PCB") (part "0402WGF0000TCE"))
    )
    (comp (ref "R_LED_C")
      (value "0R")
      (footprint "R_0402")
      (description "R - RESISTOR - SMD - 0R - 1% - 0402")
      (fields (field (name "LCSC PART #") "C17168") (field (name "Comment") "0402WGF0000TCE"))
      (libsource (lib "JLC_PCB") (part "0402WGF0000TCE"))
    )
    (comp (ref "R_LED_D")
      (value "0R")
      (footprint "R_0402")
      (description "R - RESISTOR - SMD - 0R - 1% - 0402")
      (fields (field (name "LCSC PART #") "C17168") (field (name "Comment") "0402WGF0000TCE"))
      (libsource (lib "JLC_PCB") (part "0402WGF0000TCE"))
    )
    (comp (ref "TWLV_C_AA")
      (value "10uF")
      (footprint "C_0603")
      (description "C - CAPACITOR - MLCC - 10uF - 25V - 0603")
      (fields (field (name "LCSC PART #") "C96446") (field (name "Comment") "CL10A106MA8NRNC"))
      (libsource (lib "JLC_PCB") (part "CL10A106MA8NRNC"))
    )
    (comp (ref "TWLV_C_AB")
      (value "10uF")
      (footprint "C_0603")
      (description "C - CAPACITOR - MLCC - 10uF - 25V - 0603")
      (fields (field (name "LCSC PART #") "C96446") (field (name "Comment") "CL10A106MA8NRNC"))
      (libsource (lib "JLC_PCB") (part "CL10A106MA8NRNC"))
    )
    (comp (ref "TWLV_C_AC")
      (value "10uF")
      (footprint "C_0603")
      (description "C - CAPACITOR - MLCC - 10uF - 25V - 0603")
      (fields (field (name "LCSC PART #") "C96446") (field (name "Comment") "CL10A106MA8NRNC"))
      (libsource (lib "JLC_PCB") (part "CL10A106MA8NRNC"))
    )
    (comp (ref "TWLV_C_AD")
      (value "10uF")
      (footprint "C_0603")
      (description "C - CAPACITOR - MLCC - 10uF - 25V - 0603")
      (fields (field (name "LCSC PART #") "C96446") (field (name "Comment") "CL10A106MA8NRNC"))
      (libsource (lib "JLC_PCB") (part "CL10A106MA8NRNC"))
    )
    (comp (ref "TWLV_C_AE")
      (value "10uF")
      (footprint "C_0603")
      (description "C - CAPACITOR - MLCC - 10uF - 25V - 0603")
      (fields (field (name "LCSC PART #") "C96446") (field (name "Comment") "CL10A106MA8NRNC"))
      (libsource (lib "JLC_PCB") (part "CL10A106MA8NRNC"))
    )
    (comp (ref "TWLV_C_AF")
      (value "10uF")
      (footprint "C_0603")
      (description "C - CAPACITOR - MLCC - 10uF - 25V - 0603")
      (fields (field (name "LCSC PART #") "C96446") (field (name "Comment") "CL10A106MA8NRNC"))
      (libsource (lib "JLC_PCB") (part "CL10A106MA8NRNC"))
    )
    (comp (ref "TWLV_C_AG")
      (value "10uF")
      (footprint "C_0603")
      (description "C - CAPACITOR - MLCC - 10uF - 25V - 0603")
      (fields (field (name "LCSC PART #") "C96446") (field (name "Comment") "CL10A106MA8NRNC"))
      (libsource (lib "JLC_PCB") (part "CL10A106MA8NRNC"))
    )
    (comp (ref "TWLV_C_AH")
      (value "10uF")
      (footprint "C_0603")
      (description "C - CAPACITOR - MLCC - 10uF - 25V - 0603")
      (fields (field (name "LCSC PART #") "C96446") (field (name "Comment") "CL10A106MA8NRNC"))
      (libsource (lib "JLC_PCB") (part "CL10A106MA8NRNC"))
    )
    (comp (ref "TWLV_C_AI")
      (value "10uF")
      (footprint "C_0603")
      (description "C - CAPACITOR - MLCC - 10uF - 25V - 0603")
      (fields (field (name "LCSC PART #") "C96446") (field (name "Comment") "CL10A106MA8NRNC"))
      (libsource (lib "JLC_PCB") (part "CL10A106MA8NRNC"))
    )
    (comp (ref "TWLV_C_AJ")
      (value "10uF")
      (footprint "C_0603")
      (description "C - CAPACITOR - MLCC - 10uF - 25V - 0603")
      (fields (field (name "LCSC PART #") "C96446") (field (name "Comment") "CL10A106MA8NRNC"))
      (libsource (lib "JLC_PCB") (part "CL10A106MA8NRNC"))
    )
    (comp (ref "TWLV_C_AK")
      (value "10uF")
      (footprint "C_0603")
      (description "C - CAPACITOR - MLCC - 10uF - 25V - 0603")
      (fields (field (name "LCSC PART #") "C96446") (field (name "Comment") "CL10A106MA8NRNC"))
      (libsource (lib "JLC_PCB") (part "CL10A106MA8NRNC"))
    )
    (comp (ref "TWLV_C_AL")
      (value "10uF")
      (footprint "C_0603")
      (description "C - CAPACITOR - MLCC - 10uF - 25V - 0603")
      (fields (field (name "LCSC PART #") "C96446") (field (name "Comment") "CL10A106MA8NRNC"))
      (libsource (lib "JLC_PCB") (part "CL10A106MA8NRNC"))
    )
    (comp (ref "TWLV_C_AM")
      (value "10uF")
      (footprint "C_0603")
      (description "C - CAPACITOR - MLCC - 10uF - 25V - 0603")
      (fields (field (name "LCSC PART #") "C96446") (field (name "Comment") "CL10A106MA8NRNC"))
      (libsource (lib "JLC_PCB") (part "CL10A106MA8NRNC"))
    )
    (comp (ref "TWLV_C_AN")
      (value "10uF")
      (footprint "C_0603")
      (description "C - CAPACITOR - MLCC - 10uF - 25V - 0603")
      (fields (field (name "LCSC PART #") "C96446") (field (name "Comment") "CL10A106MA8NRNC"))
      (libsource (lib "JLC_PCB") (part "CL10A106MA8NRNC"))
    )
    (comp (ref "TWLV_C_AO")
      (value "10uF")
      (footprint "C_0603")
      (description "C - CAPACITOR - MLCC - 10uF - 25V - 0603")
      (fields (field (name "LCSC PART #") "C96446") (field (name "Comment") "CL10A106MA8NRNC"))
      (libsource (lib "JLC_PCB") (part "CL10A106MA8NRNC"))
    )
    (comp (ref "TWLV_C_AP")
      (value "10uF")
      (footprint "C_0603")
      (description "C - CAPACITOR - MLCC - 10uF - 25V - 0603")
      (fields (field (name "LCSC PART #") "C96446") (field (name "Comment") "CL10A106MA8NRNC"))
      (libsource (lib "JLC_PCB") (part "CL10A106MA8NRNC"))
    )
    (comp (ref "TWLV_C_AQ")
      (value "10uF")
      (footprint "C_0603")
      (description "C - CAPACITOR - MLCC - 10uF - 25V - 0603")
      (fields (field (name "LCSC PART #") "C96446") (field (name "Comment") "CL10A106MA8NRNC"))
      (libsource (lib "JLC_PCB") (part "CL10A106MA8NRNC"))
    )
    (comp (ref "TWLV_C_AR")
      (value "10uF")
      (footprint "C_0603")
      (description "C - CAPACITOR - MLCC - 10uF - 25V - 0603")
      (fields (field (name "LCSC PART #") "C96446") (field (name "Comment") "CL10A106MA8NRNC"))
      (libsource (lib "JLC_PCB") (part "CL10A106MA8NRNC"))
    )
    (comp (ref "TWLV_C_AS")
      (value "10uF")
      (footprint "C_0603")
      (description "C - CAPACITOR - MLCC - 10uF - 25V - 0603")
      (fields (field (name "LCSC PART #") "C96446") (field (name "Comment") "CL10A106MA8NRNC"))
      (libsource (lib "JLC_PCB") (part "CL10A106MA8NRNC"))
    )
    (comp (ref "TWLV_C_AT")
      (value "10uF")
      (footprint "C_0603")
      (description "C - CAPACITOR - MLCC - 10uF - 25V - 0603")
      (fields (field (name "LCSC PART #") "C96446") (field (name "Comment") "CL10A106MA8NRNC"))
      (libsource (lib "JLC_PCB") (part "CL10A106MA8NRNC"))
    )
    (comp (ref "TWLV_C_AU")
      (value "10uF")
      (footprint "C_0603")
      (description "C - CAPACITOR - MLCC - 10uF - 25V - 0603")
      (fields (field (name "LCSC PART #") "C96446") (field (name "Comment") "CL10A106MA8NRNC"))
      (libsource (lib "JLC_PCB") (part "CL10A106MA8NRNC"))
    )
    (comp (ref "TWLV_C_AV")
      (value "10uF")
      (footprint "C_0603")
      (description "C - CAPACITOR - MLCC - 10uF - 25V - 0603")
      (fields (field (name "LCSC PART #") "C96446") (field (name "Comment") "CL10A106MA8NRNC"))
      (libsource (lib "JLC_PCB") (part "CL10A106MA8NRNC"))
    )
    (comp (ref "TWLV_C_AW")
      (value "10uF")
      (footprint "C_0603")
      (description "C - CAPACITOR - MLCC - 10uF - 25V - 0603")
      (fields (field (name "LCSC PART #") "C96446") (field (name "Comment") "CL10A106MA8NRNC"))
      (libsource (lib "JLC_PCB") (part "CL10A106MA8NRNC"))
    )
    (comp (ref "TWLV_C_AX")
      (value "10uF")
      (footprint "C_0603")
      (description "C - CAPACITOR - MLCC - 10uF - 25V - 0603")
      (fields (field (name "LCSC PART #") "C96446") (field (name "Comment") "CL10A106MA8NRNC"))
      (libsource (lib "JLC_PCB") (part "CL10A106MA8NRNC"))
    )
    (comp (ref "TWLV_C_AY")
      (value "10uF")
      (footprint "C_0603")
      (description "C - CAPACITOR - MLCC - 10uF - 25V - 0603")
      (fields (field (name "LCSC PART #") "C96446") (field (name "Comment") "CL10A106MA8NRNC"))
      (libsource (lib "JLC_PCB") (part "CL10A106MA8NRNC"))
    )
    (comp (ref "TWLV_C_AZ")
      (value "10uF")
      (footprint "C_0603")
      (description "C - CAPACITOR - MLCC - 10uF - 25V - 0603")
      (fields (field (name "LCSC PART #") "C96446") (field (name "Comment") "CL10A106MA8NRNC"))
      (libsource (lib "JLC_PCB") (part "CL10A106MA8NRNC"))
    )
    (comp (ref "TWLV_C_BA")
      (value "10uF")
      (footprint "C_0603")
      (description "C - CAPACITOR - MLCC - 10uF - 25V - 0603")
      (fields (field (name "LCSC PART #") "C96446") (field (name "Comment") "CL10A106MA8NRNC"))
      (libsource (lib "JLC_PCB") (part "CL10A106MA8NRNC"))
    )
    (comp (ref "TWLV_C_BB")
      (value "10uF")
      (footprint "C_0603")
      (description "C - CAPACITOR - MLCC - 10uF - 25V - 0603")
      (fields (field (name "LCSC PART #") "C96446") (field (name "Comment") "CL10A106MA8NRNC"))
      (libsource (lib "JLC_PCB") (part "CL10A106MA8NRNC"))
    )
    (comp (ref "TWLV_C_BC")
      (value "10uF")
      (footprint "C_0603")
      (description "C - CAPACITOR - MLCC - 10uF - 25V - 0603")
      (fields (field (name "LCSC PART #") "C96446") (field (name "Comment") "CL10A106MA8NRNC"))
      (libsource (lib "JLC_PCB") (part "CL10A106MA8NRNC"))
    )
    (comp (ref "TWLV_C_BD")
      (value "10uF")
      (footprint "C_0603")
      (description "C - CAPACITOR - MLCC - 10uF - 25V - 0603")
      (fields (field (name "LCSC PART #") "C96446") (field (name "Comment") "CL10A106MA8NRNC"))
      (libsource (lib "JLC_PCB") (part "CL10A106MA8NRNC"))
    )
    (comp (ref "TWLV_C_BE")
      (value "10uF")
      (footprint "C_0603")
      (description "C - CAPACITOR - MLCC - 10uF - 25V - 0603")
      (fields (field (name "LCSC PART #") "C96446") (field (name "Comment") "CL10A106MA8NRNC"))
      (libsource (lib "JLC_PCB") (part "CL10A106MA8NRNC"))
    )
    (comp (ref "TWLV_C_BF")
      (value "10uF")
      (footprint "C_0603")
      (description "C - CAPACITOR - MLCC - 10uF - 25V - 0603")
      (fields (field (name "LCSC PART #") "C96446") (field (name "Comment") "CL10A106MA8NRNC"))
      (libsource (lib "JLC_PCB") (part "CL10A106MA8NRNC"))
    )
    (comp (ref "TWLV_C_BG")
      (value "10uF")
      (footprint "C_0603")
      (description "C - CAPACITOR - MLCC - 10uF - 25V - 0603")
      (fields (field (name "LCSC PART #") "C96446") (field (name "Comment") "CL10A106MA8NRNC"))
      (libsource (lib "JLC_PCB") (part "CL10A106MA8NRNC"))
    )
    (comp (ref "TWLV_C_BH")
      (value "10uF")
      (footprint "C_0603")
      (description "C - CAPACITOR - MLCC - 10uF - 25V - 0603")
      (fields (field (name "LCSC PART #") "C96446") (field (name "Comment") "CL10A106MA8NRNC"))
      (libsource (lib "JLC_PCB") (part "CL10A106MA8NRNC"))
    )
    (comp (ref "TWLV_C_BI")
      (value "10uF")
      (footprint "C_0603")
      (description "C - CAPACITOR - MLCC - 10uF - 25V - 0603")
      (fields (field (name "LCSC PART #") "C96446") (field (name "Comment") "CL10A106MA8NRNC"))
      (libsource (lib "JLC_PCB") (part "CL10A106MA8NRNC"))
    )
    (comp (ref "TWLV_C_BJ")
      (value "10uF")
      (footprint "C_0603")
      (description "C - CAPACITOR - MLCC - 10uF - 25V - 0603")
      (fields (field (name "LCSC PART #") "C96446") (field (name "Comment") "CL10A106MA8NRNC"))
      (libsource (lib "JLC_PCB") (part "CL10A106MA8NRNC"))
    )
    (comp (ref "TWLV_C_DA")
      (value "1uF")
      (footprint "C_1206")
      (description "C - CAPACITOR - MLCC - 1uF - 100V - 1206 - X7R")
      (fields (field (name "LCSC PART #") "C91151") (field (name "Comment") "1206B105K101NT"))
      (libsource (lib "JLC_PCB") (part "1206B105K101NT"))
    )
    (comp (ref "TWLV_C_DB")
      (value "1uF")
      (footprint "C_1206")
      (description "C - CAPACITOR - MLCC - 1uF - 100V - 1206 - X7R")
      (fields (field (name "LCSC PART #") "C91151") (field (name "Comment") "1206B105K101NT"))
      (libsource (lib "JLC_PCB") (part "1206B105K101NT"))
    )
    (comp (ref "TWLV_C_DC")
      (value "1uF")
      (footprint "C_1206")
      (description "C - CAPACITOR - MLCC - 1uF - 100V - 1206 - X7R")
      (fields (field (name "LCSC PART #") "C91151") (field (name "Comment") "1206B105K101NT"))
      (libsource (lib "JLC_PCB") (part "1206B105K101NT"))
    )
    (comp (ref "TWLV_C_DD")
      (value "1uF")
      (footprint "C_1206")
      (description "C - CAPACITOR - MLCC - 1uF - 100V - 1206 - X7R")
      (fields (field (name "LCSC PART #") "C91151") (field (name "Comment") "1206B105K101NT"))
      (libsource (lib "JLC_PCB") (part "1206B105K101NT"))
    )
    (comp (ref "TWLV_D_A")
      (value "SS210")
      (footprint "DO-214AC")
      (description "D - DIODE - SCHOTTKY - 100V - 2A")
      (fields (field (name "LCSC PART #") "C14996"))
      (libsource (lib "JLC_PCB") (part "SS210"))
    )
    (comp (ref "TWLV_L_A")
      (value "220uH")
      (footprint "SRR1260")
      (description "L - INDUCTOR - 220uH - 1.6A - 12.5mm")
      (fields (field (name "LCSC PART #") "C169380") (field (name "Comment") "SWRB1207S-221MT"))
      (libsource (lib "JLC_PCB") (part "SWRB1207S-221MT"))
    )
    (comp (ref "TWLV_Q_A")
      (value "2N7002")
      (footprint "TO-236AB")
      (description "Q - TRANSISTOR - MOSFET (N) - 60V - 200mW")
      (fields (field (name "LCSC PART #") "C8545"))
      (libsource (lib "JLC_PCB") (part "2N7002"))
    )
    (comp (ref "TWLV_R_A")
      (value "1M")
      (footprint "R_0402")
      (description "R - RESISTOR - SMD - 1M - 1% - 0402")
      (fields (field (name "LCSC PART #") "C26083") (field (name "Comment") "0402WGF1004TCE"))
      (libsource (lib "JLC_PCB") (part "0402WGF1004TCE"))
    )
    (comp (ref "TWLV_R_B")
      (value "10k")
      (footprint "R_0402")
      (description "R - RESISTOR - SMD - 10k - 1% - 0402")
      (fields (field (name "LCSC PART #") "C25744") (field (name "Comment") "0402WGF1002TCE"))
      (libsource (lib "JLC_PCB") (part "0402WGF1002TCE"))
    )
    (comp (ref "TWLV_R_C")
      (value "1.2k")
      (footprint "R_0402")
      (description "R - RESISTOR - SMD - 1.2k - 1% - 0402")
      (fields (field (name "LCSC PART #") "C25862") (field (name "Comment") "0402WGF1201TCE"))
      (libsource (lib "JLC_PCB") (part "0402WGF1201TCE"))
    )
    (comp (ref "TWLV_R_D")
      (value "390R")
      (footprint "R_0603")
      (description "R - RESISTOR - SMD - 390R - 1% - 0603")
      (fields (field (name "LCSC PART #") "C23151") (field (name "Comment") "0603WAF3900T5E"))
      (libsource (lib "JLC_PCB") (part "0603WAF3900T5E"))
    )
    (comp (ref "TWLV_R_E")
      (value "0.1R")
      (footprint "R_1206")
      (description "R - RESISTOR - SMD - 0.1R - 1% - 1206")
      (fields (field (name "LCSC PART #") "C25334") (field (name "Comment") "1206W4F100LT5E"))
      (libsource (lib "JLC_PCB") (part "1206W4F100LT5E"))
    )
    (comp (ref "TWLV_R_F")
      (value "0R")
      (footprint "R_0402")
      (description "R - RESISTOR - SMD - 0R - 1% - 0402")
      (fields (field (name "LCSC PART #") "C17168") (field (name "Comment") "0402WGF0000TCE"))
      (libsource (lib "JLC_PCB") (part "0402WGF0000TCE"))
    )
    (comp (ref "U5V2")
      (value "78L05G-AB3-R")
      (footprint "SOT-223-3")
      (description "U - IC - 5V Power Regulator")
      (fields (field (name "LCSC PART #") "C71136"))
      (libsource (lib "JLC_PCB") (part "78L05G-AB3-R"))
    )
    (comp (ref "U_TWLV_A")
      (value "LM2576HVS-ADJ/TR")
      (footprint "SILICON:TO-263-5")
      (description "U - IC - BUCK CONVERTER, ADJUSTABLE, 60V, 3A")
      (fields (field (name "LCSC PART #") "C234208") (field (name "MF") "Texas Instruments"))
      (libsource (lib "JLC_PCB") (part "LM2576HVS-ADJ/TR"))
    )
  )
  (nets
    (net (code "1") (name "+3V3") (class "Default")
      (node (ref "C") (pin "2") (pinfunction "2_2") (pintype "passive"))
      (node (ref "MT_L_TA") (pin "2") (pinfunction "2_2") (pintype "passive"))
      (node (ref "MT_R_FT") (pin "2") (pinfunction "2_2") (pintype "passive"))
      (node (ref "MT_U_T") (pin "24") (pinfunction "VCC_24") (pintype "power_in"))
      (node (ref "Qscl") (pin "1") (pinfunction "G_1") (pintype "passive"))
      (node (ref "Qsda") (pin "1") (pinfunction "G_1") (pintype "passive"))
      (node (ref "Rscl") (pin "2") (pinfunction "2_2") (pintype "passive"))
      (node (ref "Rsda") (pin "2") (pinfunction "2_2") (pintype "passive"))
    )
    (net (code "2") (name "+5V") (class "Default")
      (node (ref "C5v2") (pin "2") (pinfunction "2_2") (pintype "passive"))
      (node (ref "Cvdd") (pin "2") (pinfunction "2_2") (pintype "passive"))
      (node (ref "MT_C_HD") (pin "1") (pinfunction "1_1") (pintype "passive"))
      (node (ref "MT_C_HE") (pin "2") (pinfunction "2_2") (pintype "passive"))
      (node (ref "MT_C_HF") (pin "2") (pinfunction "2_2") (pintype "passive"))
      (node (ref "MT_C_HG") (pin "2") (pinfunction "2_2") (pintype "passive"))
      (node (ref "MT_C_HI") (pin "1") (pinfunction "1_1") (pintype "passive"))
      (node (ref "MT_U_B") (pin "17") (pinfunction "VDD_17") (pintype "power_in"))
      (node (ref "MT_U_H") (pin "3") (pinfunction "VDDD_3") (pintype "power_in"))
      (node (ref "MT_U_H") (pin "6") (pinfunction "I2C0_6") (pintype "bidirectional"))
      (node (ref "Qsu") (pin "3") (pinfunction "C_3") (pintype "passive"))
      (node (ref "R21") (pin "2") (pinfunction "2_2") (pintype "passive"))
      (node (ref "R28") (pin "2") (pinfunction "2_2") (pintype "passive"))
      (node (ref "R29") (pin "2") (pinfunction "2_2") (pintype "passive"))
      (node (ref "R30") (pin "1") (pinfunction "1_1") (pintype "passive"))
      (node (ref "R31") (pin "2") (pinfunction "2_2") (pintype "passive"))
      (node (ref "Rnc4") (pin "2") (pinfunction "2_2") (pintype "passive"))
      (node (ref "Rpm") (pin "1") (pinfunction "1_1") (pintype "passive"))
      (node (ref "Rsu4") (pin "2") (pinfunction "2_2") (pintype "passive"))
      (node (ref "U5V2") (pin "1") (pinfunction "Vout_1") (pintype "output"))
    )
    (net (code "3") (name "/+3V3_LED") (class "Default")
      (node (ref "MT_R_FT") (pin "1") (pinfunction "1_1") (pintype "passive"))
      (node (ref "R100") (pin "1") (pinfunction "1_1") (pintype "passive"))
      (node (ref "R101") (pin "1") (pinfunction "1_1") (pintype "passive"))
      (node (ref "R102") (pin "1") (pinfunction "1_1") (pintype "passive"))
      (node (ref "R103") (pin "1") (pinfunction "1_1") (pintype "passive"))
    )
    (net (code "4") (name "/+12V") (class "Default")
      (node (ref "C5v1") (pin "2") (pinfunction "2_2") (pintype "passive"))
      (node (ref "Cvcc") (pin "2") (pinfunction "2_2") (pintype "passive"))
      (node (ref "MT_D_KA") (pin "1") (pinfunction "K_1") (pintype "passive"))
      (node (ref "MT_D_KB") (pin "1") (pinfunction "K_1") (pintype "passive"))
      (node (ref "MT_KA") (pin "1") (pinfunction "COIL1_1") (pintype "passive"))
      (node (ref "MT_KB") (pin "1") (pinfunction "COIL1_1") (pintype "passive"))
      (node (ref "MT_U_B") (pin "21") (pinfunction "VCC1_21") (pintype "power_in"))
      (node (ref "MT_U_B") (pin "25") (pinfunction "VCC2_25") (pintype "power_in"))
      (node (ref "TWLV_R_F") (pin "2") (pinfunction "2_2") (pintype "passive"))
      (node (ref "U5V2") (pin "3") (pinfunction "VIN_3") (pintype "input"))
    )
    (net (code "5") (name "/+12V_I") (class "Default")
      (node (ref "TWLV_C_AA") (pin "1") (pinfunction "1_1") (pintype "passive"))
      (node (ref "TWLV_C_AB") (pin "1") (pinfunction "1_1") (pintype "passive"))
      (node (ref "TWLV_C_AC") (pin "1") (pinfunction "1_1") (pintype "passive"))
      (node (ref "TWLV_C_AD") (pin "1") (pinfunction "1_1") (pintype "passive"))
      (node (ref "TWLV_C_AE") (pin "1") (pinfunction "1_1") (pintype "passive"))
      (node (ref "TWLV_C_AF") (pin "1") (pinfunction "1_1") (pintype "passive"))
      (node (ref "TWLV_C_AG") (pin "1") (pinfunction "1_1") (pintype "passive"))
      (node (ref "TWLV_C_AH") (pin "1") (pinfunction "1_1") (pintype "passive"))
      (node (ref "TWLV_C_AI") (pin "1") (pinfunction "1_1") (pintype "passive"))
      (node (ref "TWLV_C_AJ") (pin "1") (pinfunction "1_1") (pintype "passive"))
      (node (ref "TWLV_C_AK") (pin "1") (pinfunction "1_1") (pintype "passive"))
      (node (ref "TWLV_C_AL") (pin "1") (pinfunction "1_1") (pintype "passive"))
      (node (ref "TWLV_C_AM") (pin "1") (pinfunction "1_1") (pintype "passive"))
      (node (ref "TWLV_C_AN") (pin "1") (pinfunction "1_1") (pintype "passive"))
      (node (ref "TWLV_C_AO") (pin "1") (pinfunction "1_1") (pintype "passive"))
      (node (ref "TWLV_C_AP") (pin "1") (pinfunction "1_1") (pintype "passive"))
      (node (ref "TWLV_C_AQ") (pin "1") (pinfunction "1_1") (pintype "passive"))
      (node (ref "TWLV_C_AR") (pin "1") (pinfunction "1_1") (pintype "passive"))
      (node (ref "TWLV_C_AS") (pin "1") (pinfunction "1_1") (pintype "passive"))
      (node (ref "TWLV_C_AT") (pin "1") (pinfunction "1_1") (pintype "passive"))
      (node (ref "TWLV_C_AU") (pin "1") (pinfunction "1_1") (pintype "passive"))
      (node (ref "TWLV_C_AV") (pin "1") (pinfunction "1_1") (pintype "passive"))
      (node (ref "TWLV_C_AW") (pin "1") (pinfunction "1_1") (pintype "passive"))
      (node (ref "TWLV_C_AX") (pin "1") (pinfunction "1_1") (pintype "passive"))
      (node (ref "TWLV_C_AY") (pin "1") (pinfunction "1_1") (pintype "passive"))
      (node (ref "TWLV_C_AZ") (pin "1") (pinfunction "1_1") (pintype "passive"))
      (node (ref "TWLV_C_BA") (pin "1") (pinfunction "1_1") (pintype "passive"))
      (node (ref "TWLV_C_BB") (pin "1") (pinfunction "1_1") (pintype "passive"))
      (node (ref "TWLV_C_BC") (pin "1") (pinfunction "1_1") (pintype "passive"))
      (node (ref "TWLV_C_BD") (pin "1") (pinfunction "1_1") (pintype "passive"))
      (node (ref "TWLV_C_BE") (pin "1") (pinfunction "1_1") (pintype "passive"))
      (node (ref "TWLV_C_BF") (pin "1") (pinfunction "1_1") (pintype "passive"))
      (node (ref "TWLV_C_BG") (pin "1") (pinfunction "1_1") (pintype "passive"))
      (node (ref "TWLV_C_BH") (pin "1") (pinfunction "1_1") (pintype "passive"))
      (node (ref "TWLV_C_BI") (pin "1") (pinfunction "1_1") (pintype "passive"))
      (node (ref "TWLV_C_BJ") (pin "1") (pinfunction "1_1") (pintype "passive"))
      (node (ref "TWLV_R_C") (pin "1") (pinfunction "1_1") (pintype "passive"))
      (node (ref "TWLV_R_E") (pin "2") (pinfunction "2_2") (pintype "passive"))
      (node (ref "TWLV_R_F") (pin "1") (pinfunction "1_1") (pintype "passive"))
    )
    (net (code "6") (name "/1A_GATE") (class "Default")
      (node (ref "D_1A") (pin "2") (pinfunction "A_2") (pintype "passive"))
      (node (ref "D_1A_G") (pin "1") (pinfunction "K_1") (pintype "passive"))
      (node (ref "Q_LEDA") (pin "1") (pinfunction "G_1") (pintype "passive"))
      (node (ref "R_1A_b") (pin "2") (pinfunction "2_2") (pintype "passive"))
      (node (ref "R_1A_c") (pin "2") (pinfunction "2_2") (pintype "passive"))
    )
    (net (code "7") (name "/1B_GATE") (class "Default")
      (node (ref "D_1B") (pin "2") (pinfunction "A_2") (pintype "passive"))
      (node (ref "D_1B_G") (pin "1") (pinfunction "K_1") (pintype "passive"))
      (node (ref "R_1B_b") (pin "2") (pinfunction "2_2") (pintype "passive"))
      (node (ref "R_1B_c") (pin "2") (pinfunction "2_2") (pintype "passive"))
    )
    (net (code "8") (name "/3V3_SCL") (class "Default")
      (node (ref "Qscl") (pin "2") (pinfunction "S_2") (pintype "passive"))
      (node (ref "Rscl") (pin "1") (pinfunction "1_1") (pintype "passive"))
    )
    (net (code "9") (name "/3V3_SDA") (class "Default")
      (node (ref "Qsda") (pin "2") (pinfunction "S_2") (pintype "passive"))
      (node (ref "Rsda") (pin "1") (pinfunction "1_1") (pintype "passive"))
    )
    (net (code "10") (name "/5V_SCL") (class "Default")
      (node (ref "MT_C_HF") (pin "1") (pinfunction "1_1") (pintype "passive"))
      (node (ref "MT_U_H") (pin "8") (pinfunction "SCL_8") (pintype "input"))
      (node (ref "Qscl") (pin "3") (pinfunction "D_3") (pintype "passive"))
    )
    (net (code "11") (name "/5V_SDA") (class "Default")
      (node (ref "MT_C_HE") (pin "1") (pinfunction "1_1") (pintype "passive"))
      (node (ref "MT_U_H") (pin "9") (pinfunction "SDA_9") (pintype "bidirectional"))
      (node (ref "Qsda") (pin "3") (pinfunction "D_3") (pintype "passive"))
    )
    (net (code "12") (name "/BG1") (class "Default")
      (node (ref "D5") (pin "1") (pinfunction "K_1") (pintype "passive"))
      (node (ref "MT_U_B") (pin "24") (pinfunction "LOA_24") (pintype "output"))
      (node (ref "Rbg1a") (pin "1") (pinfunction "1_1") (pintype "passive"))
    )
    (net (code "13") (name "/BG2") (class "Default")
      (node (ref "D6") (pin "1") (pinfunction "K_1") (pintype "passive"))
      (node (ref "MT_U_B") (pin "22") (pinfunction "LOB_22") (pintype "output"))
      (node (ref "Rbg2a") (pin "2") (pinfunction "2_2") (pintype "passive"))
    )
    (net (code "14") (name "/BIN") (class "Default")
      (node (ref "MT_U_B") (pin "4") (pinfunction "BIN_4") (pintype "output"))
      (node (ref "Rbin") (pin "2") (pinfunction "2_2") (pintype "passive"))
    )
    (net (code "15") (name "/BIN_R") (class "Default")
      (node (ref "Csu2") (pin "2") (pinfunction "2_2") (pintype "passive"))
      (node (ref "MT_R_TZ") (pin "1") (pinfunction "1_1") (pintype "passive"))
      (node (ref "MT_U_H") (pin "19") (pinfunction "AIIN_19") (pintype "input"))
      (node (ref "Qsu") (pin "2") (pinfunction "E_2") (pintype "passive"))
      (node (ref "Rbin") (pin "1") (pinfunction "1_1") (pintype "passive"))
      (node (ref "Rsu1") (pin "2") (pinfunction "2_2") (pintype "passive"))
    )
    (net (code "16") (name "/BIN_R_2") (class "Default")
      (node (ref "MT_R_TY") (pin "1") (pinfunction "1_1") (pintype "passive"))
      (node (ref "MT_R_TZ") (pin "2") (pinfunction "2_2") (pintype "passive"))
      (node (ref "MT_U_T") (pin "4") (pinfunction "Y5_4") (pintype "passive"))
    )
    (net (code "17") (name "/BOOST1") (class "Default")
      (node (ref "Cboot1") (pin "2") (pinfunction "2_2") (pintype "passive"))
      (node (ref "MT_U_B") (pin "26") (pinfunction "HBA_26") (pintype "passive"))
    )
    (net (code "18") (name "/BOOST2") (class "Default")
      (node (ref "Cboot2") (pin "2") (pinfunction "2_2") (pintype "passive"))
      (node (ref "MT_U_B") (pin "20") (pinfunction "HBB_20") (pintype "passive"))
    )
    (net (code "19") (name "/BOUT") (class "Default")
      (node (ref "MT_U_B") (pin "11") (pinfunction "BOUT_11") (pintype "output"))
      (node (ref "Rbout") (pin "2") (pinfunction "2_2") (pintype "passive"))
    )
    (net (code "20") (name "/BOUT_R") (class "Default")
      (node (ref "MT_R_TX") (pin "1") (pinfunction "1_1") (pintype "passive"))
      (node (ref "MT_U_H") (pin "21") (pinfunction "AIOUT_21") (pintype "output"))
      (node (ref "Rbout") (pin "1") (pinfunction "1_1") (pintype "passive"))
    )
    (net (code "21") (name "/BOUT_R_2") (class "Default")
      (node (ref "MT_R_TW") (pin "1") (pinfunction "1_1") (pintype "passive"))
      (node (ref "MT_R_TX") (pin "2") (pinfunction "2_2") (pintype "passive"))
      (node (ref "MT_U_T") (pin "3") (pinfunction "Y6_3") (pintype "passive"))
    )
    (net (code "22") (name "/BST_SIM") (class "Default")
      (node (ref "Dsu1") (pin "1") (pinfunction "K_1") (pintype "passive"))
      (node (ref "Dsu2") (pin "2") (pinfunction "A_2") (pintype "passive"))
      (node (ref "Rsu5") (pin "1") (pinfunction "1_1") (pintype "passive"))
    )
    (net (code "23") (name "/BUTTON_OC") (class "Default")
      (node (ref "TWLV_Q_A") (pin "3") (pinfunction "D_3") (pintype "passive"))
      (node (ref "TWLV_R_A") (pin "2") (pinfunction "2_2") (pintype "passive"))
      (node (ref "U_TWLV_A") (pin "5") (pinfunction "ON/OFF_5") (pintype "input"))
    )
    (net (code "24") (name "/D8") (class "Default")
      (node (ref "D_CLAMP_8") (pin "2") (pinfunction "A_2") (pintype "passive"))
      (node (ref "D_CLAMP_9") (pin "1") (pinfunction "K_1") (pintype "passive"))
      (node (ref "R160") (pin "1") (pinfunction "1_1") (pintype "passive"))
    )
    (net (code "25") (name "/D10") (class "Default")
      (node (ref "D_CLAMP_10") (pin "2") (pinfunction "A_2") (pintype "passive"))
      (node (ref "D_CLAMP_11") (pin "1") (pinfunction "K_1") (pintype "passive"))
      (node (ref "R160") (pin "2") (pinfunction "2_2") (pintype "passive"))
    )
    (net (code "26") (name "/DATA_BUS_A0") (class "Default")
      (node (ref "MT_U_T") (pin "10") (pinfunction "S0_10") (pintype "passive"))
    )
    (net (code "27") (name "/DATA_BUS_A1") (class "Default")
      (node (ref "MT_U_T") (pin "11") (pinfunction "S1_11") (pintype "passive"))
    )
    (net (code "28") (name "/DATA_BUS_A2") (class "Default")
      (node (ref "MT_U_T") (pin "14") (pinfunction "S2_14") (pintype "passive"))
    )
    (net (code "29") (name "/DATA_BUS_A3") (class "Default")
      (node (ref "MT_U_T") (pin "13") (pinfunction "S3_13") (pintype "passive"))
    )
    (net (code "30") (name "/FBIN") (class "Default")
      (node (ref "Dsu2") (pin "1") (pinfunction "K_1") (pintype "passive"))
      (node (ref "MT_C_HA") (pin "2") (pinfunction "2_2") (pintype "passive"))
      (node (ref "MT_U_H") (pin "15") (pinfunction "AVIN_15") (pintype "input"))
      (node (ref "Rvinb") (pin "2") (pinfunction "2_2") (pintype "passive"))
      (node (ref "Rvint") (pin "1") (pinfunction "1_1") (pintype "passive"))
    )
    (net (code "31") (name "/FBOUT") (class "Default")
      (node (ref "MT_C_HL") (pin "2") (pinfunction "2_2") (pintype "passive"))
      (node (ref "MT_U_H") (pin "17") (pinfunction "AVOUT_17") (pintype "output"))
      (node (ref "Rvoutb") (pin "2") (pinfunction "2_2") (pintype "passive"))
      (node (ref "Rvoutt") (pin "1") (pinfunction "1_1") (pintype "passive"))
    )
    (net (code "32") (name "/HIA") (class "Default")
      (node (ref "MT_U_B") (pin "7") (pinfunction "HIA_7") (pintype "input"))
      (node (ref "MT_U_H") (pin "26") (pinfunction "HIA_26") (pintype "output"))
      (node (ref "Rsu2") (pin "2") (pinfunction "2_2") (pintype "passive"))
    )
    (net (code "33") (name "/HIB") (class "Default")
      (node (ref "Dsu1") (pin "2") (pinfunction "A_2") (pintype "passive"))
      (node (ref "MT_U_B") (pin "8") (pinfunction "HIB_8") (pintype "input"))
      (node (ref "MT_U_H") (pin "25") (pinfunction "HIB_25") (pintype "output"))
      (node (ref "Rsu3") (pin "2") (pinfunction "2_2") (pintype "passive"))
    )
    (net (code "34") (name "/IIN") (class "Default")
      (node (ref "Ciin") (pin "2") (pinfunction "2_2") (pintype "passive"))
      (node (ref "MT_U_B") (pin "3") (pinfunction "IIN_3") (pintype "output"))
      (node (ref "Riin") (pin "2") (pinfunction "2_2") (pintype "passive"))
    )
    (net (code "35") (name "/IOUT") (class "Default")
      (node (ref "Ciout") (pin "2") (pinfunction "2_2") (pintype "passive"))
      (node (ref "MT_U_B") (pin "12") (pinfunction "IOUT_12") (pintype "output"))
      (node (ref "Riout") (pin "2") (pinfunction "2_2") (pintype "passive"))
    )
    (net (code "36") (name "/LED_VSS") (class "Default")
      (node (ref "Q_LEDA") (pin "2") (pinfunction "S_2") (pintype "passive"))
      (node (ref "Q_LEDB") (pin "2") (pinfunction "S_2") (pintype "passive"))
      (node (ref "Q_LEDVSS") (pin "3") (pinfunction "D_3") (pintype "passive"))
    )
    (net (code "37") (name "/LIA") (class "Default")
      (node (ref "MT_U_B") (pin "6") (pinfunction "LIA_6") (pintype "input"))
      (node (ref "MT_U_H") (pin "27") (pinfunction "LIA_27") (pintype "output"))
    )
    (net (code "38") (name "/LIB") (class "Default")
      (node (ref "MT_U_B") (pin "9") (pinfunction "LIB_9") (pintype "input"))
      (node (ref "MT_U_H") (pin "24") (pinfunction "LIB_24") (pintype "output"))
    )
    (net (code "39") (name "/MT_KA") (class "Default")
      (node (ref "MT_D_KA") (pin "2") (pinfunction "A_2") (pintype "passive"))
      (node (ref "MT_KA") (pin "8") (pinfunction "COIL2_8") (pintype "passive"))
      (node (ref "MT_Q_KA") (pin "3") (pinfunction "D_3") (pintype "passive"))
    )
    (net (code "40") (name "/MT_KB") (class "Default")
      (node (ref "MT_D_KB") (pin "2") (pinfunction "A_2") (pintype "passive"))
      (node (ref "MT_KB") (pin "8") (pinfunction "COIL2_8") (pintype "passive"))
      (node (ref "MT_Q_KB") (pin "3") (pinfunction "D_3") (pintype "passive"))
    )
    (net (code "41") (name "/MT_K_EN") (class "Default")
      (node (ref "MT_Q_KB") (pin "1") (pinfunction "G_1") (pintype "passive"))
    )
    (net (code "42") (name "/MT_K_POL") (class "Default")
      (node (ref "MT_Q_KA") (pin "1") (pinfunction "G_1") (pintype "passive"))
    )
    (net (code "43") (name "/MT_LED_A") (class "Default")
      (node (ref "J1") (pin "11") (pinfunction "11_11") (pintype "passive"))
      (node (ref "MT_U_T") (pin "19") (pinfunction "Y12_19") (pintype "passive"))
      (node (ref "R_LED_B") (pin "2") (pinfunction "2_2") (pintype "passive"))
    )
    (net (code "44") (name "/MT_LED_B") (class "Default")
      (node (ref "J1") (pin "9") (pinfunction "9_9") (pintype "passive"))
      (node (ref "MT_U_T") (pin "20") (pinfunction "Y11_20") (pintype "passive"))
      (node (ref "R_LED_A") (pin "2") (pinfunction "2_2") (pintype "passive"))
    )
    (net (code "45") (name "/MT_LED_C") (class "Default")
      (node (ref "J2") (pin "11") (pinfunction "11_11") (pintype "passive"))
      (node (ref "MT_U_T") (pin "22") (pinfunction "Y9_22") (pintype "passive"))
      (node (ref "R_LED_C") (pin "2") (pinfunction "2_2") (pintype "passive"))
    )
    (net (code "46") (name "/MT_LED_D") (class "Default")
      (node (ref "J2") (pin "9") (pinfunction "9_9") (pintype "passive"))
      (node (ref "MT_U_T") (pin "21") (pinfunction "Y10_21") (pintype "passive"))
      (node (ref "R_LED_D") (pin "2") (pinfunction "2_2") (pintype "passive"))
    )
    (net (code "47") (name "/MT_MUX") (class "Default")
      (node (ref "MT_U_T") (pin "1") (pinfunction "Z_1") (pintype "passive"))
    )
    (net (code "48") (name "/MT_TS_A") (class "Default")
      (node (ref "MT_RT_TA") (pin "2") (pinfunction "2_2") (pintype "passive"))
      (node (ref "MT_R_TA") (pin "1") (pinfunction "1_1") (pintype "passive"))
      (node (ref "MT_U_T") (pin "9") (pinfunction "Y0_9") (pintype "passive"))
    )
    (net (code "49") (name "/MT_TS_B") (class "Default")
      (node (ref "MT_RT_TB") (pin "2") (pinfunction "2_2") (pintype "passive"))
      (node (ref "MT_R_TB") (pin "1") (pinfunction "1_1") (pintype "passive"))
      (node (ref "MT_U_T") (pin "8") (pinfunction "Y1_8") (pintype "passive"))
    )
    (net (code "50") (name "/MT_TS_C") (class "Default")
      (node (ref "MT_RT_TC") (pin "2") (pinfunction "2_2") (pintype "passive"))
      (node (ref "MT_R_TC") (pin "1") (pinfunction "1_1") (pintype "passive"))
      (node (ref "MT_U_T") (pin "7") (pinfunction "Y2_7") (pintype "passive"))
    )
    (net (code "51") (name "/MT_TS_D") (class "Default")
      (node (ref "MT_RT_TD") (pin "2") (pinfunction "2_2") (pintype "passive"))
      (node (ref "MT_R_TD") (pin "1") (pinfunction "1_1") (pintype "passive"))
      (node (ref "MT_U_T") (pin "6") (pinfunction "Y3_6") (pintype "passive"))
    )
    (net (code "52") (name "/MT_TS_E") (class "Default")
      (node (ref "MT_RT_TE") (pin "2") (pinfunction "2_2") (pintype "passive"))
      (node (ref "MT_R_TE") (pin "1") (pinfunction "1_1") (pintype "passive"))
      (node (ref "MT_U_T") (pin "5") (pinfunction "Y4_5") (pintype "passive"))
    )
    (net (code "53") (name "/MT_TS_G") (class "Default")
      (node (ref "MT_RT_TG") (pin "2") (pinfunction "2_2") (pintype "passive"))
      (node (ref "MT_R_TG") (pin "1") (pinfunction "1_1") (pintype "passive"))
      (node (ref "MT_U_T") (pin "18") (pinfunction "Y13_18") (pintype "passive"))
    )
    (net (code "54") (name "/MT_TS_J") (class "Default")
      (node (ref "MT_RT_TJ") (pin "2") (pinfunction "2_2") (pintype "passive"))
      (node (ref "MT_R_TJ") (pin "1") (pinfunction "1_1") (pintype "passive"))
      (node (ref "MT_U_T") (pin "17") (pinfunction "Y14_17") (pintype "passive"))
    )
    (net (code "55") (name "/MT_TS_K") (class "Default")
      (node (ref "MT_RT_TK") (pin "2") (pinfunction "2_2") (pintype "passive"))
      (node (ref "MT_R_TK") (pin "1") (pinfunction "1_1") (pintype "passive"))
    )
    (net (code "56") (name "/MT_VDDA_T") (class "Default")
      (node (ref "C_vdd_ts_a") (pin "1") (pinfunction "1_1") (pintype "passive"))
      (node (ref "MT_L_TA") (pin "1") (pinfunction "1_1") (pintype "passive"))
      (node (ref "MT_R_TA") (pin "2") (pinfunction "2_2") (pintype "passive"))
      (node (ref "MT_R_TB") (pin "2") (pinfunction "2_2") (pintype "passive"))
      (node (ref "MT_R_TC") (pin "2") (pinfunction "2_2") (pintype "passive"))
      (node (ref "MT_R_TD") (pin "2") (pinfunction "2_2") (pintype "passive"))
      (node (ref "MT_R_TE") (pin "2") (pinfunction "2_2") (pintype "passive"))
      (node (ref "MT_R_TG") (pin "2") (pinfunction "2_2") (pintype "passive"))
      (node (ref "MT_R_TJ") (pin "2") (pinfunction "2_2") (pintype "passive"))
      (node (ref "MT_R_TK") (pin "2") (pinfunction "2_2") (pintype "passive"))
    )
    (net (code "57") (name "/MT_VSSA") (class "Default")
      (node (ref "MT_RT_TA") (pin "1") (pinfunction "1_1") (pintype "passive"))
      (node (ref "MT_RT_TB") (pin "1") (pinfunction "1_1") (pintype "passive"))
      (node (ref "MT_RT_TC") (pin "1") (pinfunction "1_1") (pintype "passive"))
      (node (ref "MT_RT_TD") (pin "1") (pinfunction "1_1") (pintype "passive"))
      (node (ref "MT_RT_TE") (pin "1") (pinfunction "1_1") (pintype "passive"))
      (node (ref "MT_RT_TG") (pin "1") (pinfunction "1_1") (pintype "passive"))
      (node (ref "MT_RT_TJ") (pin "1") (pinfunction "1_1") (pintype "passive"))
      (node (ref "MT_RT_TK") (pin "1") (pinfunction "1_1") (pintype "passive"))
      (node (ref "MT_R_FV") (pin "1") (pinfunction "1_1") (pintype "passive"))
    )
    (net (code "58") (name "/NC4") (class "Default")
      (node (ref "MT_C_HK") (pin "2") (pinfunction "2_2") (pintype "passive"))
      (node (ref "MT_U_H") (pin "23") (pinfunction "NC4_23") (pintype "passive"))
      (node (ref "Rnc4") (pin "1") (pinfunction "1_1") (pintype "passive"))
    )
    (net (code "59") (name "/OVS") (class "Default")
      (node (ref "MT_U_B") (pin "16") (pinfunction "OVS_16") (pintype "passive"))
      (node (ref "Rovs") (pin "1") (pinfunction "1_1") (pintype "passive"))
    )
    (net (code "60") (name "/PAN_DET") (class "Default")
      (node (ref "D_1A") (pin "1") (pinfunction "K_1") (pintype "passive"))
      (node (ref "D_1B") (pin "1") (pinfunction "K_1") (pintype "passive"))
      (node (ref "MT_U_T") (pin "23") (pinfunction "Y8_23") (pintype "passive"))
      (node (ref "Q_LEDVSS") (pin "1") (pinfunction "G_1") (pintype "passive"))
    )
    (net (code "61") (name "/PM") (class "Default")
      (node (ref "MT_U_H") (pin "28") (pinfunction "PM_28") (pintype "input"))
      (node (ref "Rpm") (pin "2") (pinfunction "2_2") (pintype "passive"))
    )
    (net (code "62") (name "/PM_OUT") (class "Default")
      (node (ref "MT_U_H") (pin "11") (pinfunction "PM_OUT_11") (pintype "output"))
    )
    (net (code "63") (name "/POLARITY") (class "Default")
      (node (ref "MT_U_T") (pin "2") (pinfunction "Y7_2") (pintype "passive"))
      (node (ref "Q_LEDA") (pin "3") (pinfunction "D_3") (pintype "passive"))
      (node (ref "Q_LEDB") (pin "1") (pinfunction "G_1") (pintype "passive"))
      (node (ref "R_LED_B") (pin "1") (pinfunction "1_1") (pintype "passive"))
      (node (ref "R_LED_D") (pin "1") (pinfunction "1_1") (pintype "passive"))
    )
    (net (code "64") (name "/SIA") (class "Default")
      (node (ref "MT_U_B") (pin "1") (pinfunction "SIA_1") (pintype "input"))
      (node (ref "Riinsns1") (pin "1") (pinfunction "1_1") (pintype "passive"))
    )
    (net (code "65") (name "/SIB") (class "Default")
      (node (ref "MT_U_B") (pin "14") (pinfunction "SIB_14") (pintype "input"))
      (node (ref "Rioutsns1") (pin "1") (pinfunction "1_1") (pintype "passive"))
    )
    (net (code "66") (name "/SOA") (class "Default")
      (node (ref "MT_U_B") (pin "2") (pinfunction "SDA_2") (pintype "input"))
      (node (ref "Riinsns2") (pin "1") (pinfunction "1_1") (pintype "passive"))
    )
    (net (code "67") (name "/SOB") (class "Default")
      (node (ref "MT_U_B") (pin "13") (pinfunction "SOB_13") (pintype "output"))
      (node (ref "Rioutsns2") (pin "1") (pinfunction "1_1") (pintype "passive"))
    )
    (net (code "68") (name "/SOL_1A") (class "Default")
      (node (ref "J1") (pin "1") (pinfunction "1_1") (pintype "passive"))
      (node (ref "J1") (pin "2") (pinfunction "2_2") (pintype "passive"))
      (node (ref "J1") (pin "3") (pinfunction "3_3") (pintype "passive"))
      (node (ref "J1") (pin "4") (pinfunction "4_4") (pintype "passive"))
      (node (ref "J1") (pin "5") (pinfunction "5_5") (pintype "passive"))
      (node (ref "J1") (pin "6") (pinfunction "6_6") (pintype "passive"))
      (node (ref "J1") (pin "7") (pinfunction "7_7") (pintype "passive"))
      (node (ref "J1") (pin "8") (pinfunction "8_8") (pintype "passive"))
      (node (ref "MT_D_IN_A") (pin "2") (pinfunction "A_2") (pintype "passive"))
      (node (ref "MT_D_IN_B") (pin "1") (pinfunction "K_1") (pintype "passive"))
      (node (ref "MT_D_IN_E") (pin "2") (pinfunction "A_2") (pintype "passive"))
      (node (ref "MT_D_IN_F") (pin "1") (pinfunction "K_1") (pintype "passive"))
      (node (ref "MT_D_IN_I") (pin "2") (pinfunction "A_2") (pintype "passive"))
      (node (ref "MT_D_IN_J") (pin "1") (pinfunction "K_1") (pintype "passive"))
      (node (ref "MT_D_IN_M") (pin "2") (pinfunction "A_2") (pintype "passive"))
      (node (ref "MT_D_IN_N") (pin "1") (pinfunction "K_1") (pintype "passive"))
      (node (ref "MT_D_IN_Q") (pin "2") (pinfunction "A_2") (pintype "passive"))
      (node (ref "MT_D_IN_R") (pin "1") (pinfunction "K_1") (pintype "passive"))
      (node (ref "MT_D_IN_U") (pin "2") (pinfunction "A_2") (pintype "passive"))
      (node (ref "MT_D_IN_V") (pin "1") (pinfunction "K_1") (pintype "passive"))
      (node (ref "MT_KA") (pin "3") (pinfunction "COM1_3") (pintype "passive"))
      (node (ref "R_1A_a") (pin "1") (pinfunction "1_1") (pintype "passive"))
    )
    (net (code "69") (name "/SOL_1B") (class "Default")
      (node (ref "J2") (pin "1") (pinfunction "1_1") (pintype "passive"))
      (node (ref "J2") (pin "2") (pinfunction "2_2") (pintype "passive"))
      (node (ref "J2") (pin "3") (pinfunction "3_3") (pintype "passive"))
      (node (ref "J2") (pin "4") (pinfunction "4_4") (pintype "passive"))
      (node (ref "J2") (pin "5") (pinfunction "5_5") (pintype "passive"))
      (node (ref "J2") (pin "6") (pinfunction "6_6") (pintype "passive"))
      (node (ref "J2") (pin "7") (pinfunction "7_7") (pintype "passive"))
      (node (ref "J2") (pin "8") (pinfunction "8_8") (pintype "passive"))
      (node (ref "MT_D_IN_C") (pin "2") (pinfunction "A_2") (pintype "passive"))
      (node (ref "MT_D_IN_D") (pin "1") (pinfunction "K_1") (pintype "passive"))
      (node (ref "MT_D_IN_G") (pin "2") (pinfunction "A_2") (pintype "passive"))
      (node (ref "MT_D_IN_H") (pin "1") (pinfunction "K_1") (pintype "passive"))
      (node (ref "MT_D_IN_K") (pin "2") (pinfunction "A_2") (pintype "passive"))
      (node (ref "MT_D_IN_L") (pin "1") (pinfunction "K_1") (pintype "passive"))
      (node (ref "MT_D_IN_O") (pin "2") (pinfunction "A_2") (pintype "passive"))
      (node (ref "MT_D_IN_P") (pin "1") (pinfunction "K_1") (pintype "passive"))
      (node (ref "MT_D_IN_S") (pin "2") (pinfunction "A_2") (pintype "passive"))
      (node (ref "MT_D_IN_T") (pin "1") (pinfunction "K_1") (pintype "passive"))
      (node (ref "MT_D_IN_W") (pin "2") (pinfunction "A_2") (pintype "passive"))
      (node (ref "MT_D_IN_X") (pin "1") (pinfunction "K_1") (pintype "passive"))
      (node (ref "MT_KA") (pin "6") (pinfunction "COM2_6") (pintype "passive"))
      (node (ref "R_1B_a") (pin "1") (pinfunction "1_1") (pintype "passive"))
    )
    (net (code "70") (name "/SOL_V_N") (class "Default")
      (node (ref "MT_KA") (pin "4") (pinfunction "NO1_4") (pintype "passive"))
      (node (ref "MT_KA") (pin "7") (pinfunction "NC2_7") (pintype "passive"))
      (node (ref "MT_KB") (pin "3") (pinfunction "COM1_3") (pintype "passive"))
    )
    (net (code "71") (name "/SOL_V_P") (class "Default")
      (node (ref "MT_KA") (pin "2") (pinfunction "NC1_2") (pintype "passive"))
      (node (ref "MT_KA") (pin "5") (pinfunction "NO2_5") (pintype "passive"))
      (node (ref "MT_KB") (pin "6") (pinfunction "COM2_6") (pintype "passive"))
      (node (ref "MT_KB") (pin "7") (pinfunction "NC2_7") (pintype "passive"))
    )
    (net (code "72") (name "/SW1") (class "Default")
      (node (ref "C18") (pin "2") (pinfunction "2_2") (pintype "passive"))
      (node (ref "Cboot1") (pin "1") (pinfunction "1_1") (pintype "passive"))
      (node (ref "Dbg1") (pin "1") (pinfunction "K_1") (pintype "passive"))
      (node (ref "Dtg1") (pin "2") (pinfunction "A_2") (pintype "passive"))
      (node (ref "L1") (pin "1") (pinfunction "1_1") (pintype "passive"))
      (node (ref "L10") (pin "1") (pinfunction "1_1") (pintype "passive"))
      (node (ref "L11") (pin "1") (pinfunction "1_1") (pintype "passive"))
      (node (ref "L12") (pin "1") (pinfunction "1_1") (pintype "passive"))
      (node (ref "L2") (pin "1") (pinfunction "1_1") (pintype "passive"))
      (node (ref "L3") (pin "1") (pinfunction "1_1") (pintype "passive"))
      (node (ref "L4") (pin "1") (pinfunction "1_1") (pintype "passive"))
      (node (ref "L5") (pin "1") (pinfunction "1_1") (pintype "passive"))
      (node (ref "L6") (pin "1") (pinfunction "1_1") (pintype "passive"))
      (node (ref "L7") (pin "1") (pinfunction "1_1") (pintype "passive"))
      (node (ref "L8") (pin "1") (pinfunction "1_1") (pintype "passive"))
      (node (ref "L9") (pin "1") (pinfunction "1_1") (pintype "passive"))
      (node (ref "MT_Q1") (pin "3") (pinfunction "S_3") (pintype "passive"))
      (node (ref "MT_Q2") (pin "2") (pinfunction "D_2") (pintype "passive"))
      (node (ref "MT_U_B") (pin "28") (pinfunction "HSA_28") (pintype "passive"))
      (node (ref "Rtg1s") (pin "1") (pinfunction "1_1") (pintype "passive"))
    )
    (net (code "73") (name "/SW2") (class "Default")
      (node (ref "C19") (pin "2") (pinfunction "2_2") (pintype "passive"))
      (node (ref "Cboot2") (pin "1") (pinfunction "1_1") (pintype "passive"))
      (node (ref "Dbg2") (pin "1") (pinfunction "K_1") (pintype "passive"))
      (node (ref "Dtg2") (pin "2") (pinfunction "A_2") (pintype "passive"))
      (node (ref "L1") (pin "2") (pinfunction "2_2") (pintype "passive"))
      (node (ref "L10") (pin "2") (pinfunction "2_2") (pintype "passive"))
      (node (ref "L11") (pin "2") (pinfunction "2_2") (pintype "passive"))
      (node (ref "L12") (pin "2") (pinfunction "2_2") (pintype "passive"))
      (node (ref "L2") (pin "2") (pinfunction "2_2") (pintype "passive"))
      (node (ref "L3") (pin "2") (pinfunction "2_2") (pintype "passive"))
      (node (ref "L4") (pin "2") (pinfunction "2_2") (pintype "passive"))
      (node (ref "L5") (pin "2") (pinfunction "2_2") (pintype "passive"))
      (node (ref "L6") (pin "2") (pinfunction "2_2") (pintype "passive"))
      (node (ref "L7") (pin "2") (pinfunction "2_2") (pintype "passive"))
      (node (ref "L8") (pin "2") (pinfunction "2_2") (pintype "passive"))
      (node (ref "L9") (pin "2") (pinfunction "2_2") (pintype "passive"))
      (node (ref "MT_Q3") (pin "2") (pinfunction "D_2") (pintype "passive"))
      (node (ref "MT_Q4") (pin "3") (pinfunction "S_3") (pintype "passive"))
      (node (ref "MT_U_B") (pin "18") (pinfunction "HSB_18") (pintype "passive"))
      (node (ref "Rtg2s") (pin "2") (pinfunction "2_2") (pintype "passive"))
    )
    (net (code "74") (name "/TG1") (class "Default")
      (node (ref "D3") (pin "1") (pinfunction "K_1") (pintype "passive"))
      (node (ref "MT_U_B") (pin "27") (pinfunction "HOA_27") (pintype "output"))
      (node (ref "Rtg1a") (pin "1") (pinfunction "1_1") (pintype "passive"))
    )
    (net (code "75") (name "/TG2") (class "Default")
      (node (ref "D4") (pin "1") (pinfunction "K_1") (pintype "passive"))
      (node (ref "MT_U_B") (pin "19") (pinfunction "HOB_19") (pintype "output"))
      (node (ref "Rtg2a") (pin "2") (pinfunction "2_2") (pintype "passive"))
    )
    (net (code "76") (name "/TWLV_FB") (class "Default")
      (node (ref "TWLV_R_C") (pin "2") (pinfunction "2_2") (pintype "passive"))
      (node (ref "TWLV_R_D") (pin "2") (pinfunction "2_2") (pintype "passive"))
      (node (ref "U_TWLV_A") (pin "4") (pinfunction "FB_4") (pintype "bidirectional"))
    )
    (net (code "77") (name "/WAKEUP_R") (class "Default")
      (node (ref "TWLV_Q_A") (pin "1") (pinfunction "G_1") (pintype "passive"))
      (node (ref "TWLV_R_B") (pin "1") (pinfunction "1_1") (pintype "passive"))
    )
    (net (code "78") (name "/nRST") (class "Default")
      (node (ref "MT_C_HJ") (pin "2") (pinfunction "2_2") (pintype "passive"))
      (node (ref "MT_U_B") (pin "10") (pinfunction "PGD_10") (pintype "open_collector"))
      (node (ref "MT_U_H") (pin "1") (pinfunction "RST_1") (pintype "input"))
      (node (ref "R26") (pin "1") (pinfunction "1_1") (pintype "passive"))
    )
    (net (code "79") (name "AGND") (class "Default")
      (node (ref "Ciin") (pin "1") (pinfunction "1_1") (pintype "passive"))
      (node (ref "Ciout") (pin "1") (pinfunction "1_1") (pintype "passive"))
      (node (ref "MT_U_B") (pin "5") (pinfunction "AGND_5") (pintype "power_in"))
      (node (ref "MT_U_H") (pin "13") (pinfunction "VSSA_13") (pintype "power_in"))
      (node (ref "Ragnd") (pin "2") (pinfunction "2_2") (pintype "passive"))
      (node (ref "Riin") (pin "1") (pinfunction "1_1") (pintype "passive"))
      (node (ref "Riout") (pin "1") (pinfunction "1_1") (pintype "passive"))
    )
    (net (code "80") (name "GND") (class "Default")
      (node (ref "C") (pin "1") (pinfunction "1_1") (pintype "passive"))
      (node (ref "C49") (pin "1") (pinfunction "1_1") (pintype "passive"))
      (node (ref "C50") (pin "1") (pinfunction "1_1") (pintype "passive"))
      (node (ref "C51") (pin "1") (pinfunction "1_1") (pintype "passive"))
      (node (ref "C52") (pin "2") (pinfunction "2_2") (pintype "passive"))
      (node (ref "C5v1") (pin "1") (pinfunction "1_1") (pintype "passive"))
      (node (ref "C5v2") (pin "1") (pinfunction "1_1") (pintype "passive"))
      (node (ref "C_vdd_ts_a") (pin "2") (pinfunction "2_2") (pintype "passive"))
      (node (ref "Csu1") (pin "1") (pinfunction "1_1") (pintype "passive"))
      (node (ref "Csu2") (pin "1") (pinfunction "1_1") (pintype "passive"))
      (node (ref "Cvcc") (pin "1") (pinfunction "1_1") (pintype "passive"))
      (node (ref "Cvdd") (pin "1") (pinfunction "1_1") (pintype "passive"))
      (node (ref "D14") (pin "1") (pinfunction "K_1") (pintype "passive"))
      (node (ref "D15") (pin "1") (pinfunction "K_1") (pintype "passive"))
      (node (ref "D_1A_G") (pin "2") (pinfunction "A_2") (pintype "passive"))
      (node (ref "D_1B_G") (pin "2") (pinfunction "A_2") (pintype "passive"))
      (node (ref "D_CLAMP_18") (pin "2") (pinfunction "A_2") (pintype "passive"))
      (node (ref "MT_C_AA") (pin "1") (pinfunction "1_1") (pintype "passive"))
      (node (ref "MT_C_AB") (pin "1") (pinfunction "1_1") (pintype "passive"))
      (node (ref "MT_C_AC") (pin "1") (pinfunction "1_1") (pintype "passive"))
      (node (ref "MT_C_AD") (pin "1") (pinfunction "1_1") (pintype "passive"))
      (node (ref "MT_C_AE") (pin "1") (pinfunction "1_1") (pintype "passive"))
      (node (ref "MT_C_AF") (pin "1") (pinfunction "1_1") (pintype "passive"))
      (node (ref "MT_C_AG") (pin "1") (pinfunction "1_1") (pintype "passive"))
      (node (ref "MT_C_AH") (pin "1") (pinfunction "1_1") (pintype "passive"))
      (node (ref "MT_C_AI") (pin "1") (pinfunction "1_1") (pintype "passive"))
      (node (ref "MT_C_AJ") (pin "1") (pinfunction "1_1") (pintype "passive"))
      (node (ref "MT_C_AK") (pin "1") (pinfunction "1_1") (pintype "passive"))
      (node (ref "MT_C_AL") (pin "1") (pinfunction "1_1") (pintype "passive"))
      (node (ref "MT_C_AM") (pin "1") (pinfunction "1_1") (pintype "passive"))
      (node (ref "MT_C_AN") (pin "1") (pinfunction "1_1") (pintype "passive"))
      (node (ref "MT_C_BA") (pin "1") (pinfunction "1_1") (pintype "passive"))
      (node (ref "MT_C_BB") (pin "1") (pinfunction "1_1") (pintype "passive"))
      (node (ref "MT_C_BC") (pin "1") (pinfunction "1_1") (pintype "passive"))
      (node (ref "MT_C_BD") (pin "1") (pinfunction "1_1") (pintype "passive"))
      (node (ref "MT_C_BE") (pin "1") (pinfunction "1_1") (pintype "passive"))
      (node (ref "MT_C_BF") (pin "1") (pinfunction "1_1") (pintype "passive"))
      (node (ref "MT_C_BG") (pin "1") (pinfunction "1_1") (pintype "passive"))
      (node (ref "MT_C_BH") (pin "1") (pinfunction "1_1") (pintype "passive"))
      (node (ref "MT_C_BI") (pin "1") (pinfunction "1_1") (pintype "passive"))
      (node (ref "MT_C_BJ") (pin "1") (pinfunction "1_1") (pintype "passive"))
      (node (ref "MT_C_BK") (pin "1") (pinfunction "1_1") (pintype "passive"))
      (node (ref "MT_C_BL") (pin "1") (pinfunction "1_1") (pintype "passive"))
      (node (ref "MT_C_CA") (pin "1") (pinfunction "1_1") (pintype "passive"))
      (node (ref "MT_C_CB") (pin "1") (pinfunction "1_1") (pintype "passive"))
      (node (ref "MT_C_CC") (pin "1") (pinfunction "1_1") (pintype "passive"))
      (node (ref "MT_C_CD") (pin "1") (pinfunction "1_1") (pintype "passive"))
      (node (ref "MT_C_CE") (pin "1") (pinfunction "1_1") (pintype "passive"))
      (node (ref "MT_C_CF") (pin "1") (pinfunction "1_1") (pintype "passive"))
      (node (ref "MT_C_CG") (pin "1") (pinfunction "1_1") (pintype "passive"))
      (node (ref "MT_C_CH") (pin "1") (pinfunction "1_1") (pintype "passive"))
      (node (ref "MT_C_CI") (pin "1") (pinfunction "1_1") (pintype "passive"))
      (node (ref "MT_C_CJ") (pin "1") (pinfunction "1_1") (pintype "passive"))
      (node (ref "MT_C_CK") (pin "1") (pinfunction "1_1") (pintype "passive"))
      (node (ref "MT_C_CL") (pin "1") (pinfunction "1_1") (pintype "passive"))
      (node (ref "MT_C_CM") (pin "1") (pinfunction "1_1") (pintype "passive"))
      (node (ref "MT_C_CN") (pin "1") (pinfunction "1_1") (pintype "passive"))
      (node (ref "MT_C_DA") (pin "1") (pinfunction "1_1") (pintype "passive"))
      (node (ref "MT_C_DB") (pin "1") (pinfunction "1_1") (pintype "passive"))
      (node (ref "MT_C_DC") (pin "1") (pinfunction "1_1") (pintype "passive"))
      (node (ref "MT_C_DD") (pin "1") (pinfunction "1_1") (pintype "passive"))
      (node (ref "MT_C_DE") (pin "1") (pinfunction "1_1") (pintype "passive"))
      (node (ref "MT_C_DF") (pin "1") (pinfunction "1_1") (pintype "passive"))
      (node (ref "MT_C_DG") (pin "1") (pinfunction "1_1") (pintype "passive"))
      (node (ref "MT_C_DH") (pin "1") (pinfunction "1_1") (pintype "passive"))
      (node (ref "MT_C_DI") (pin "1") (pinfunction "1_1") (pintype "passive"))
      (node (ref "MT_C_DJ") (pin "1") (pinfunction "1_1") (pintype "passive"))
      (node (ref "MT_C_DK") (pin "1") (pinfunction "1_1") (pintype "passive"))
      (node (ref "MT_C_DL") (pin "1") (pinfunction "1_1") (pintype "passive"))
      (node (ref "MT_C_EA") (pin "1") (pinfunction "1_1") (pintype "passive"))
      (node (ref "MT_C_EB") (pin "1") (pinfunction "1_1") (pintype "passive"))
      (node (ref "MT_C_EC") (pin "1") (pinfunction "1_1") (pintype "passive"))
      (node (ref "MT_C_ED") (pin "1") (pinfunction "1_1") (pintype "passive"))
      (node (ref "MT_C_EE") (pin "1") (pinfunction "1_1") (pintype "passive"))
      (node (ref "MT_C_EF") (pin "1") (pinfunction "1_1") (pintype "passive"))
      (node (ref "MT_C_EG") (pin "1") (pinfunction "1_1") (pintype "passive"))
      (node (ref "MT_C_EH") (pin "1") (pinfunction "1_1") (pintype "passive"))
      (node (ref "MT_C_EI") (pin "1") (pinfunction "1_1") (pintype "passive"))
      (node (ref "MT_C_EJ") (pin "1") (pinfunction "1_1") (pintype "passive"))
      (node (ref "MT_C_EK") (pin "1") (pinfunction "1_1") (pintype "passive"))
      (node (ref "MT_C_EL") (pin "1") (pinfunction "1_1") (pintype "passive"))
      (node (ref "MT_C_FA") (pin "1") (pinfunction "1_1") (pintype "passive"))
      (node (ref "MT_C_FB") (pin "1") (pinfunction "1_1") (pintype "passive"))
      (node (ref "MT_C_FC") (pin "1") (pinfunction "1_1") (pintype "passive"))
      (node (ref "MT_C_FD") (pin "1") (pinfunction "1_1") (pintype "passive"))
      (node (ref "MT_C_FE") (pin "1") (pinfunction "1_1") (pintype "passive"))
      (node (ref "MT_C_FF") (pin "1") (pinfunction "1_1") (pintype "passive"))
      (node (ref "MT_C_FG") (pin "1") (pinfunction "1_1") (pintype "passive"))
      (node (ref "MT_C_FH") (pin "1") (pinfunction "1_1") (pintype "passive"))
      (node (ref "MT_C_FI") (pin "1") (pinfunction "1_1") (pintype "passive"))
      (node (ref "MT_C_FJ") (pin "1") (pinfunction "1_1") (pintype "passive"))
      (node (ref "MT_C_FK") (pin "1") (pinfunction "1_1") (pintype "passive"))
      (node (ref "MT_C_FL") (pin "1") (pinfunction "1_1") (pintype "passive"))
      (node (ref "MT_C_HA") (pin "1") (pinfunction "1_1") (pintype "passive"))
      (node (ref "MT_C_HB") (pin "2") (pinfunction "2_2") (pintype "passive"))
      (node (ref "MT_C_HC") (pin "1") (pinfunction "1_1") (pintype "passive"))
      (node (ref "MT_C_HG") (pin "1") (pinfunction "1_1") (pintype "passive"))
      (node (ref "MT_C_HI") (pin "2") (pinfunction "2_2") (pintype "passive"))
      (node (ref "MT_C_HJ") (pin "1") (pinfunction "1_1") (pintype "passive"))
      (node (ref "MT_C_HK") (pin "1") (pinfunction "1_1") (pintype "passive"))
      (node (ref "MT_C_HL") (pin "1") (pinfunction "1_1") (pintype "passive"))
      (node (ref "MT_D_IN_B") (pin "2") (pinfunction "A_2") (pintype "passive"))
      (node (ref "MT_D_IN_D") (pin "2") (pinfunction "A_2") (pintype "passive"))
      (node (ref "MT_D_IN_F") (pin "2") (pinfunction "A_2") (pintype "passive"))
      (node (ref "MT_D_IN_H") (pin "2") (pinfunction "A_2") (pintype "passive"))
      (node (ref "MT_D_IN_J") (pin "2") (pinfunction "A_2") (pintype "passive"))
      (node (ref "MT_D_IN_L") (pin "2") (pinfunction "A_2") (pintype "passive"))
      (node (ref "MT_D_IN_N") (pin "2") (pinfunction "A_2") (pintype "passive"))
      (node (ref "MT_D_IN_P") (pin "2") (pinfunction "A_2") (pintype "passive"))
      (node (ref "MT_D_IN_R") (pin "2") (pinfunction "A_2") (pintype "passive"))
      (node (ref "MT_D_IN_T") (pin "2") (pinfunction "A_2") (pintype "passive"))
      (node (ref "MT_D_IN_V") (pin "2") (pinfunction "A_2") (pintype "passive"))
      (node (ref "MT_D_IN_X") (pin "2") (pinfunction "A_2") (pintype "passive"))
      (node (ref "MT_KB") (pin "4") (pinfunction "NO1_4") (pintype "passive"))
      (node (ref "MT_NT_A") (pin "1") (pinfunction "1_1") (pintype "passive"))
      (node (ref "MT_Q_KA") (pin "2") (pinfunction "S_2") (pintype "passive"))
      (node (ref "MT_Q_KB") (pin "2") (pinfunction "S_2") (pintype "passive"))
      (node (ref "MT_R_FV") (pin "2") (pinfunction "2_2") (pintype "passive"))
      (node (ref "MT_R_TW") (pin "2") (pinfunction "2_2") (pintype "passive"))
      (node (ref "MT_R_TY") (pin "2") (pinfunction "2_2") (pintype "passive"))
      (node (ref "MT_U_B") (pin "23") (pinfunction "PGND_23") (pintype "power_in"))
      (node (ref "MT_U_H") (pin "10") (pinfunction "NC3_10") (pintype "passive"))
      (node (ref "MT_U_H") (pin "2") (pinfunction "NC1_2") (pintype "passive"))
      (node (ref "MT_U_H") (pin "22") (pinfunction "I2C2_22") (pintype "bidirectional"))
      (node (ref "MT_U_H") (pin "4") (pinfunction "VSSD_4") (pintype "power_in"))
      (node (ref "MT_U_H") (pin "7") (pinfunction "I2C1_7") (pintype "bidirectional"))
      (node (ref "MT_U_T") (pin "12") (pinfunction "VSS_12") (pintype "power_in"))
      (node (ref "MT_U_T") (pin "15") (pinfunction "E_15") (pintype "passive"))
      (node (ref "Q_LEDVSS") (pin "2") (pinfunction "S_2") (pintype "passive"))
      (node (ref "R110") (pin "1") (pinfunction "1_1") (pintype "passive"))
      (node (ref "R140") (pin "1") (pinfunction "1_1") (pintype "passive"))
      (node (ref "R26") (pin "2") (pinfunction "2_2") (pintype "passive"))
      (node (ref "R38") (pin "1") (pinfunction "1_1") (pintype "passive"))
      (node (ref "R39") (pin "1") (pinfunction "1_1") (pintype "passive"))
      (node (ref "R40") (pin "1") (pinfunction "1_1") (pintype "passive"))
      (node (ref "R41") (pin "1") (pinfunction "1_1") (pintype "passive"))
      (node (ref "R_1A_c") (pin "1") (pinfunction "1_1") (pintype "passive"))
      (node (ref "R_1B_c") (pin "1") (pinfunction "1_1") (pintype "passive"))
      (node (ref "Ragnd") (pin "1") (pinfunction "1_1") (pintype "passive"))
      (node (ref "Rovs") (pin "2") (pinfunction "2_2") (pintype "passive"))
      (node (ref "Rsu1") (pin "1") (pinfunction "1_1") (pintype "passive"))
      (node (ref "Rsu5") (pin "2") (pinfunction "2_2") (pintype "passive"))
      (node (ref "Rvinb") (pin "1") (pinfunction "1_1") (pintype "passive"))
      (node (ref "Rvoutb") (pin "1") (pinfunction "1_1") (pintype "passive"))
      (node (ref "TWLV_C_AA") (pin "2") (pinfunction "2_2") (pintype "passive"))
      (node (ref "TWLV_C_AB") (pin "2") (pinfunction "2_2") (pintype "passive"))
      (node (ref "TWLV_C_AC") (pin "2") (pinfunction "2_2") (pintype "passive"))
      (node (ref "TWLV_C_AD") (pin "2") (pinfunction "2_2") (pintype "passive"))
      (node (ref "TWLV_C_AE") (pin "2") (pinfunction "2_2") (pintype "passive"))
      (node (ref "TWLV_C_AF") (pin "2") (pinfunction "2_2") (pintype "passive"))
      (node (ref "TWLV_C_AG") (pin "2") (pinfunction "2_2") (pintype "passive"))
      (node (ref "TWLV_C_AH") (pin "2") (pinfunction "2_2") (pintype "passive"))
      (node (ref "TWLV_C_AI") (pin "2") (pinfunction "2_2") (pintype "passive"))
      (node (ref "TWLV_C_AJ") (pin "2") (pinfunction "2_2") (pintype "passive"))
      (node (ref "TWLV_C_AK") (pin "2") (pinfunction "2_2") (pintype "passive"))
      (node (ref "TWLV_C_AL") (pin "2") (pinfunction "2_2") (pintype "passive"))
      (node (ref "TWLV_C_AM") (pin "2") (pinfunction "2_2") (pintype "passive"))
      (node (ref "TWLV_C_AN") (pin "2") (pinfunction "2_2") (pintype "passive"))
      (node (ref "TWLV_C_AO") (pin "2") (pinfunction "2_2") (pintype "passive"))
      (node (ref "TWLV_C_AP") (pin "2") (pinfunction "2_2") (pintype "passive"))
      (node (ref "TWLV_C_AQ") (pin "2") (pinfunction "2_2") (pintype "passive"))
      (node (ref "TWLV_C_AR") (pin "2") (pinfunction "2_2") (pintype "passive"))
      (node (ref "TWLV_C_AS") (pin "2") (pinfunction "2_2") (pintype "passive"))
      (node (ref "TWLV_C_AT") (pin "2") (pinfunction "2_2") (pintype "passive"))
      (node (ref "TWLV_C_AU") (pin "2") (pinfunction "2_2") (pintype "passive"))
      (node (ref "TWLV_C_AV") (pin "2") (pinfunction "2_2") (pintype "passive"))
      (node (ref "TWLV_C_AW") (pin "2") (pinfunction "2_2") (pintype "passive"))
      (node (ref "TWLV_C_AX") (pin "2") (pinfunction "2_2") (pintype "passive"))
      (node (ref "TWLV_C_AY") (pin "2") (pinfunction "2_2") (pintype "passive"))
      (node (ref "TWLV_C_AZ") (pin "2") (pinfunction "2_2") (pintype "passive"))
      (node (ref "TWLV_C_BA") (pin "2") (pinfunction "2_2") (pintype "passive"))
      (node (ref "TWLV_C_BB") (pin "2") (pinfunction "2_2") (pintype "passive"))
      (node (ref "TWLV_C_BC") (pin "2") (pinfunction "2_2") (pintype "passive"))
      (node (ref "TWLV_C_BD") (pin "2") (pinfunction "2_2") (pintype "passive"))
      (node (ref "TWLV_C_BE") (pin "2") (pinfunction "2_2") (pintype "passive"))
      (node (ref "TWLV_C_BF") (pin "2") (pinfunction "2_2") (pintype "passive"))
      (node (ref "TWLV_C_BG") (pin "2") (pinfunction "2_2") (pintype "passive"))
      (node (ref "TWLV_C_BH") (pin "2") (pinfunction "2_2") (pintype "passive"))
      (node (ref "TWLV_C_BI") (pin "2") (pinfunction "2_2") (pintype "passive"))
      (node (ref "TWLV_C_BJ") (pin "2") (pinfunction "2_2") (pintype "passive"))
      (node (ref "TWLV_C_DA") (pin "2") (pinfunction "2_2") (pintype "passive"))
      (node (ref "TWLV_C_DB") (pin "2") (pinfunction "2_2") (pintype "passive"))
      (node (ref "TWLV_C_DC") (pin "2") (pinfunction "2_2") (pintype "passive"))
      (node (ref "TWLV_C_DD") (pin "2") (pinfunction "2_2") (pintype "passive"))
      (node (ref "TWLV_D_A") (pin "2") (pinfunction "A_2") (pintype "passive"))
      (node (ref "TWLV_Q_A") (pin "2") (pinfunction "S_2") (pintype "passive"))
      (node (ref "TWLV_R_B") (pin "2") (pinfunction "2_2") (pintype "passive"))
      (node (ref "TWLV_R_D") (pin "1") (pinfunction "1_1") (pintype "passive"))
      (node (ref "U5V2") (pin "2") (pinfunction "GND_2") (pintype "power_in"))
      (node (ref "U_TWLV_A") (pin "3") (pinfunction "GND_3") (pintype "power_in"))
      (node (ref "U_TWLV_A") (pin "6") (pinfunction "GND_6") (pintype "power_in"))
      (node (ref "U_TWLV_A") (pin "7") (pinfunction "GND_7") (pintype "power_in"))
    )
    (net (code "81") (name "LM_VIN") (class "Default")
      (node (ref "TWLV_C_DA") (pin "1") (pinfunction "1_1") (pintype "passive"))
      (node (ref "TWLV_C_DB") (pin "1") (pinfunction "1_1") (pintype "passive"))
      (node (ref "TWLV_C_DC") (pin "1") (pinfunction "1_1") (pintype "passive"))
      (node (ref "TWLV_C_DD") (pin "1") (pinfunction "1_1") (pintype "passive"))
      (node (ref "TWLV_R_A") (pin "1") (pinfunction "1_1") (pintype "passive"))
      (node (ref "U_TWLV_A") (pin "1") (pinfunction "VIN_1") (pintype "input"))
    )
    (net (code "82") (name "Net-(D3-A)") (class "Default")
      (node (ref "D3") (pin "2") (pinfunction "A_2") (pintype "passive"))
      (node (ref "MT_Q1") (pin "1") (pinfunction "G_1") (pintype "passive"))
      (node (ref "Rtg1a") (pin "2") (pinfunction "2_2") (pintype "passive"))
      (node (ref "Rtg1s") (pin "2") (pinfunction "2_2") (pintype "passive"))
    )
    (net (code "83") (name "Net-(D4-A)") (class "Default")
      (node (ref "D4") (pin "2") (pinfunction "A_2") (pintype "passive"))
      (node (ref "MT_Q4") (pin "1") (pinfunction "G_1") (pintype "passive"))
      (node (ref "Rtg2a") (pin "1") (pinfunction "1_1") (pintype "passive"))
      (node (ref "Rtg2s") (pin "1") (pinfunction "1_1") (pintype "passive"))
    )
    (net (code "84") (name "Net-(D5-A)") (class "Default")
      (node (ref "D5") (pin "2") (pinfunction "A_2") (pintype "passive"))
      (node (ref "MT_Q2") (pin "1") (pinfunction "G_1") (pintype "passive"))
      (node (ref "Rbg1a") (pin "2") (pinfunction "2_2") (pintype "passive"))
      (node (ref "Rbg1s") (pin "2") (pinfunction "2_2") (pintype "passive"))
    )
    (net (code "85") (name "Net-(D6-A)") (class "Default")
      (node (ref "D6") (pin "2") (pinfunction "A_2") (pintype "passive"))
      (node (ref "MT_Q3") (pin "1") (pinfunction "G_1") (pintype "passive"))
      (node (ref "Rbg2a") (pin "1") (pinfunction "1_1") (pintype "passive"))
      (node (ref "Rbg2s") (pin "1") (pinfunction "1_1") (pintype "passive"))
    )
    (net (code "86") (name "Net-(D14-A)") (class "Default")
      (node (ref "C19") (pin "1") (pinfunction "1_1") (pintype "passive"))
      (node (ref "D14") (pin "2") (pinfunction "A_2") (pintype "passive"))
      (node (ref "R140") (pin "2") (pinfunction "2_2") (pintype "passive"))
    )
    (net (code "87") (name "Net-(D15-A)") (class "Default")
      (node (ref "C18") (pin "1") (pinfunction "1_1") (pintype "passive"))
      (node (ref "D15") (pin "2") (pinfunction "A_2") (pintype "passive"))
      (node (ref "R110") (pin "2") (pinfunction "2_2") (pintype "passive"))
    )
    (net (code "88") (name "Net-(D_CLAMP_1-A)") (class "Default")
      (node (ref "D_CLAMP_1") (pin "2") (pinfunction "A_2") (pintype "passive"))
      (node (ref "D_CLAMP_2") (pin "1") (pinfunction "K_1") (pintype "passive"))
    )
    (net (code "89") (name "Net-(D_CLAMP_2-A)") (class "Default")
      (node (ref "D_CLAMP_2") (pin "2") (pinfunction "A_2") (pintype "passive"))
      (node (ref "D_CLAMP_3") (pin "1") (pinfunction "K_1") (pintype "passive"))
    )
    (net (code "90") (name "Net-(D_CLAMP_3-A)") (class "Default")
      (node (ref "D_CLAMP_3") (pin "2") (pinfunction "A_2") (pintype "passive"))
      (node (ref "D_CLAMP_4") (pin "1") (pinfunction "K_1") (pintype "passive"))
    )
    (net (code "91") (name "Net-(D_CLAMP_4-A)") (class "Default")
      (node (ref "D_CLAMP_4") (pin "2") (pinfunction "A_2") (pintype "passive"))
      (node (ref "D_CLAMP_5") (pin "1") (pinfunction "K_1") (pintype "passive"))
    )
    (net (code "92") (name "Net-(D_CLAMP_5-A)") (class "Default")
      (node (ref "D_CLAMP_5") (pin "2") (pinfunction "A_2") (pintype "passive"))
      (node (ref "D_CLAMP_6") (pin "1") (pinfunction "K_1") (pintype "passive"))
    )
    (net (code "93") (name "Net-(D_CLAMP_6-A)") (class "Default")
      (node (ref "D_CLAMP_6") (pin "2") (pinfunction "A_2") (pintype "passive"))
      (node (ref "D_CLAMP_7") (pin "1") (pinfunction "K_1") (pintype "passive"))
    )
    (net (code "94") (name "Net-(D_CLAMP_7-A)") (class "Default")
      (node (ref "D_CLAMP_7") (pin "2") (pinfunction "A_2") (pintype "passive"))
      (node (ref "D_CLAMP_8") (pin "1") (pinfunction "K_1") (pintype "passive"))
    )
    (net (code "95") (name "Net-(D_CLAMP_10-K)") (class "Default")
      (node (ref "D_CLAMP_10") (pin "1") (pinfunction "K_1") (pintype "passive"))
      (node (ref "D_CLAMP_9") (pin "2") (pinfunction "A_2") (pintype "passive"))
    )
    (net (code "96") (name "Net-(D_CLAMP_11-A)") (class "Default")
      (node (ref "D_CLAMP_11") (pin "2") (pinfunction "A_2") (pintype "passive"))
      (node (ref "D_CLAMP_12") (pin "1") (pinfunction "K_1") (pintype "passive"))
    )
    (net (code "97") (name "Net-(D_CLAMP_12-A)") (class "Default")
      (node (ref "D_CLAMP_12") (pin "2") (pinfunction "A_2") (pintype "passive"))
      (node (ref "D_CLAMP_13") (pin "1") (pinfunction "K_1") (pintype "passive"))
    )
    (net (code "98") (name "Net-(D_CLAMP_13-A)") (class "Default")
      (node (ref "D_CLAMP_13") (pin "2") (pinfunction "A_2") (pintype "passive"))
      (node (ref "D_CLAMP_14") (pin "1") (pinfunction "K_1") (pintype "passive"))
    )
    (net (code "99") (name "Net-(D_CLAMP_14-A)") (class "Default")
      (node (ref "D_CLAMP_14") (pin "2") (pinfunction "A_2") (pintype "passive"))
      (node (ref "D_CLAMP_15") (pin "1") (pinfunction "K_1") (pintype "passive"))
    )
    (net (code "100") (name "Net-(D_CLAMP_15-A)") (class "Default")
      (node (ref "D_CLAMP_15") (pin "2") (pinfunction "A_2") (pintype "passive"))
      (node (ref "D_CLAMP_16") (pin "1") (pinfunction "K_1") (pintype "passive"))
    )
    (net (code "101") (name "Net-(D_CLAMP_16-A)") (class "Default")
      (node (ref "D_CLAMP_16") (pin "2") (pinfunction "A_2") (pintype "passive"))
      (node (ref "D_CLAMP_17") (pin "1") (pinfunction "K_1") (pintype "passive"))
    )
    (net (code "102") (name "Net-(D_CLAMP_17-A)") (class "Default")
      (node (ref "D_CLAMP_17") (pin "2") (pinfunction "A_2") (pintype "passive"))
      (node (ref "D_CLAMP_18") (pin "1") (pinfunction "K_1") (pintype "passive"))
    )
    (net (code "103") (name "Net-(J1-Pad10)") (class "Default")
      (node (ref "J1") (pin "10") (pinfunction "10_10") (pintype "passive"))
      (node (ref "R101") (pin "2") (pinfunction "2_2") (pintype "passive"))
    )
    (net (code "104") (name "Net-(J1-Pad12)") (class "Default")
      (node (ref "J1") (pin "12") (pinfunction "12_12") (pintype "passive"))
      (node (ref "R100") (pin "2") (pinfunction "2_2") (pintype "passive"))
    )
    (net (code "105") (name "Net-(J2-Pad10)") (class "Default")
      (node (ref "J2") (pin "10") (pinfunction "10_10") (pintype "passive"))
      (node (ref "R102") (pin "2") (pinfunction "2_2") (pintype "passive"))
    )
    (net (code "106") (name "Net-(J2-Pad12)") (class "Default")
      (node (ref "J2") (pin "12") (pinfunction "12_12") (pintype "passive"))
      (node (ref "R103") (pin "2") (pinfunction "2_2") (pintype "passive"))
    )
    (net (code "107") (name "Net-(MT_U_H-A0)") (class "Default")
      (node (ref "C49") (pin "2") (pinfunction "2_2") (pintype "passive"))
      (node (ref "MT_U_H") (pin "14") (pinfunction "A0_14") (pintype "bidirectional"))
      (node (ref "R28") (pin "1") (pinfunction "1_1") (pintype "passive"))
      (node (ref "R38") (pin "2") (pinfunction "2_2") (pintype "passive"))
    )
    (net (code "108") (name "Net-(MT_U_H-A2)") (class "Default")
      (node (ref "C50") (pin "2") (pinfunction "2_2") (pintype "passive"))
      (node (ref "MT_U_H") (pin "16") (pinfunction "A2_16") (pintype "bidirectional"))
      (node (ref "R29") (pin "1") (pinfunction "1_1") (pintype "passive"))
      (node (ref "R39") (pin "2") (pinfunction "2_2") (pintype "passive"))
    )
    (net (code "109") (name "Net-(MT_U_H-A4)") (class "Default")
      (node (ref "C51") (pin "2") (pinfunction "2_2") (pintype "passive"))
      (node (ref "MT_U_H") (pin "18") (pinfunction "A4_18") (pintype "bidirectional"))
      (node (ref "R30") (pin "2") (pinfunction "2_2") (pintype "passive"))
      (node (ref "R40") (pin "2") (pinfunction "2_2") (pintype "passive"))
    )
    (net (code "110") (name "Net-(MT_U_H-A6)") (class "Default")
      (node (ref "C52") (pin "1") (pinfunction "1_1") (pintype "passive"))
      (node (ref "MT_U_H") (pin "20") (pinfunction "A6_20") (pintype "bidirectional"))
      (node (ref "R31") (pin "1") (pinfunction "1_1") (pintype "passive"))
      (node (ref "R41") (pin "2") (pinfunction "2_2") (pintype "passive"))
    )
    (net (code "111") (name "Net-(MT_U_H-NC2)") (class "Default")
      (node (ref "MT_C_HD") (pin "2") (pinfunction "2_2") (pintype "passive"))
      (node (ref "MT_U_H") (pin "5") (pinfunction "NC2_5") (pintype "passive"))
    )
    (net (code "112") (name "Net-(MT_U_H-VDDA)") (class "Default")
      (node (ref "MT_C_HB") (pin "1") (pinfunction "1_1") (pintype "passive"))
      (node (ref "MT_C_HC") (pin "2") (pinfunction "2_2") (pintype "passive"))
      (node (ref "MT_U_H") (pin "12") (pinfunction "VDDA_12") (pintype "power_in"))
      (node (ref "R21") (pin "1") (pinfunction "1_1") (pintype "passive"))
    )
    (net (code "113") (name "Net-(Q_LEDB-D)") (class "Default")
      (node (ref "Q_LEDB") (pin "3") (pinfunction "D_3") (pintype "passive"))
      (node (ref "R_LED_A") (pin "1") (pinfunction "1_1") (pintype "passive"))
      (node (ref "R_LED_C") (pin "1") (pinfunction "1_1") (pintype "passive"))
    )
    (net (code "114") (name "Net-(Qsu-B)") (class "Default")
      (node (ref "Csu1") (pin "2") (pinfunction "2_2") (pintype "passive"))
      (node (ref "Qsu") (pin "1") (pinfunction "B_1") (pintype "passive"))
      (node (ref "Rsu2") (pin "1") (pinfunction "1_1") (pintype "passive"))
      (node (ref "Rsu3") (pin "1") (pinfunction "1_1") (pintype "passive"))
      (node (ref "Rsu4") (pin "1") (pinfunction "1_1") (pintype "passive"))
    )
    (net (code "115") (name "Net-(R_1A_a-Pad2)") (class "Default")
      (node (ref "R_1A_a") (pin "2") (pinfunction "2_2") (pintype "passive"))
      (node (ref "R_1A_b") (pin "1") (pinfunction "1_1") (pintype "passive"))
    )
    (net (code "116") (name "Net-(R_1B_a-Pad2)") (class "Default")
      (node (ref "R_1B_a") (pin "2") (pinfunction "2_2") (pintype "passive"))
      (node (ref "R_1B_b") (pin "1") (pinfunction "1_1") (pintype "passive"))
    )
    (net (code "117") (name "Net-(TWLV_D_A-K)") (class "Default")
      (node (ref "TWLV_D_A") (pin "1") (pinfunction "K_1") (pintype "passive"))
      (node (ref "TWLV_L_A") (pin "1") (pinfunction "1_1") (pintype "passive"))
      (node (ref "U_TWLV_A") (pin "2") (pinfunction "OUT_2") (pintype "output"))
    )
    (net (code "118") (name "Net-(TWLV_L_A-Pad2)") (class "Default")
      (node (ref "TWLV_L_A") (pin "2") (pinfunction "2_2") (pintype "passive"))
      (node (ref "TWLV_R_E") (pin "1") (pinfunction "1_1") (pintype "passive"))
    )
    (net (code "119") (name "PGND") (class "Default")
      (node (ref "Dbg1") (pin "2") (pinfunction "A_2") (pintype "passive"))
      (node (ref "Dbg2") (pin "2") (pinfunction "A_2") (pintype "passive"))
      (node (ref "MT_NT_A") (pin "2") (pinfunction "2_2") (pintype "passive"))
      (node (ref "MT_Q2") (pin "3") (pinfunction "S_3") (pintype "passive"))
      (node (ref "MT_Q3") (pin "3") (pinfunction "S_3") (pintype "passive"))
      (node (ref "Rbg1s") (pin "1") (pinfunction "1_1") (pintype "passive"))
      (node (ref "Rbg2s") (pin "2") (pinfunction "2_2") (pintype "passive"))
    )
    (net (code "120") (name "VIN_N") (class "Default")
      (node (ref "Dtg1") (pin "1") (pinfunction "K_1") (pintype "passive"))
      (node (ref "MT_C_DA") (pin "2") (pinfunction "2_2") (pintype "passive"))
      (node (ref "MT_C_DB") (pin "2") (pinfunction "2_2") (pintype "passive"))
      (node (ref "MT_C_DC") (pin "2") (pinfunction "2_2") (pintype "passive"))
      (node (ref "MT_C_DD") (pin "2") (pinfunction "2_2") (pintype "passive"))
      (node (ref "MT_C_DE") (pin "2") (pinfunction "2_2") (pintype "passive"))
      (node (ref "MT_C_DF") (pin "2") (pinfunction "2_2") (pintype "passive"))
      (node (ref "MT_C_DG") (pin "2") (pinfunction "2_2") (pintype "passive"))
      (node (ref "MT_C_DH") (pin "2") (pinfunction "2_2") (pintype "passive"))
      (node (ref "MT_C_DI") (pin "2") (pinfunction "2_2") (pintype "passive"))
      (node (ref "MT_C_DJ") (pin "2") (pinfunction "2_2") (pintype "passive"))
      (node (ref "MT_C_DK") (pin "2") (pinfunction "2_2") (pintype "passive"))
      (node (ref "MT_C_DL") (pin "2") (pinfunction "2_2") (pintype "passive"))
      (node (ref "MT_Q1") (pin "2") (pinfunction "D_2") (pintype "passive"))
      (node (ref "R1") (pin "1") (pinfunction "1_1") (pintype "passive"))
      (node (ref "Riinsns2") (pin "2") (pinfunction "2_2") (pintype "passive"))
    )
    (net (code "121") (name "VIN_P") (class "Default")
      (node (ref "D_CLAMP_1") (pin "1") (pinfunction "K_1") (pintype "passive"))
      (node (ref "MT_C_AA") (pin "2") (pinfunction "2_2") (pintype "passive"))
      (node (ref "MT_C_AB") (pin "2") (pinfunction "2_2") (pintype "passive"))
      (node (ref "MT_C_AC") (pin "2") (pinfunction "2_2") (pintype "passive"))
      (node (ref "MT_C_AD") (pin "2") (pinfunction "2_2") (pintype "passive"))
      (node (ref "MT_C_AE") (pin "2") (pinfunction "2_2") (pintype "passive"))
      (node (ref "MT_C_AF") (pin "2") (pinfunction "2_2") (pintype "passive"))
      (node (ref "MT_C_AG") (pin "2") (pinfunction "2_2") (pintype "passive"))
      (node (ref "MT_C_AH") (pin "2") (pinfunction "2_2") (pintype "passive"))
      (node (ref "MT_C_AI") (pin "2") (pinfunction "2_2") (pintype "passive"))
      (node (ref "MT_C_AJ") (pin "2") (pinfunction "2_2") (pintype "passive"))
      (node (ref "MT_C_AK") (pin "2") (pinfunction "2_2") (pintype "passive"))
      (node (ref "MT_C_AL") (pin "2") (pinfunction "2_2") (pintype "passive"))
      (node (ref "MT_C_AM") (pin "2") (pinfunction "2_2") (pintype "passive"))
      (node (ref "MT_C_AN") (pin "2") (pinfunction "2_2") (pintype "passive"))
      (node (ref "MT_C_EA") (pin "2") (pinfunction "2_2") (pintype "passive"))
      (node (ref "MT_C_EB") (pin "2") (pinfunction "2_2") (pintype "passive"))
      (node (ref "MT_C_EC") (pin "2") (pinfunction "2_2") (pintype "passive"))
      (node (ref "MT_C_ED") (pin "2") (pinfunction "2_2") (pintype "passive"))
      (node (ref "MT_C_EE") (pin "2") (pinfunction "2_2") (pintype "passive"))
      (node (ref "MT_C_EF") (pin "2") (pinfunction "2_2") (pintype "passive"))
      (node (ref "MT_C_EG") (pin "2") (pinfunction "2_2") (pintype "passive"))
      (node (ref "MT_C_EH") (pin "2") (pinfunction "2_2") (pintype "passive"))
      (node (ref "MT_C_EI") (pin "2") (pinfunction "2_2") (pintype "passive"))
      (node (ref "MT_C_EJ") (pin "2") (pinfunction "2_2") (pintype "passive"))
      (node (ref "MT_C_EK") (pin "2") (pinfunction "2_2") (pintype "passive"))
      (node (ref "MT_C_EL") (pin "2") (pinfunction "2_2") (pintype "passive"))
      (node (ref "MT_D_IN_A") (pin "1") (pinfunction "K_1") (pintype "passive"))
      (node (ref "MT_D_IN_C") (pin "1") (pinfunction "K_1") (pintype "passive"))
      (node (ref "MT_D_IN_E") (pin "1") (pinfunction "K_1") (pintype "passive"))
      (node (ref "MT_D_IN_G") (pin "1") (pinfunction "K_1") (pintype "passive"))
      (node (ref "MT_D_IN_I") (pin "1") (pinfunction "K_1") (pintype "passive"))
      (node (ref "MT_D_IN_K") (pin "1") (pinfunction "K_1") (pintype "passive"))
      (node (ref "MT_D_IN_M") (pin "1") (pinfunction "K_1") (pintype "passive"))
      (node (ref "MT_D_IN_O") (pin "1") (pinfunction "K_1") (pintype "passive"))
      (node (ref "MT_D_IN_Q") (pin "1") (pinfunction "K_1") (pintype "passive"))
      (node (ref "MT_D_IN_S") (pin "1") (pinfunction "K_1") (pintype "passive"))
      (node (ref "MT_D_IN_U") (pin "1") (pinfunction "K_1") (pintype "passive"))
      (node (ref "MT_D_IN_W") (pin "1") (pinfunction "K_1") (pintype "passive"))
      (node (ref "MT_KB") (pin "5") (pinfunction "NO2_5") (pintype "passive"))
      (node (ref "R1") (pin "2") (pinfunction "2_2") (pintype "passive"))
      (node (ref "Riinsns1") (pin "2") (pinfunction "2_2") (pintype "passive"))
      (node (ref "Rvint") (pin "2") (pinfunction "2_2") (pintype "passive"))
    )
    (net (code "122") (name "VOUT_N") (class "Default")
      (node (ref "MT_C_BA") (pin "2") (pinfunction "2_2") (pintype "passive"))
      (node (ref "MT_C_BB") (pin "2") (pinfunction "2_2") (pintype "passive"))
      (node (ref "MT_C_BC") (pin "2") (pinfunction "2_2") (pintype "passive"))
      (node (ref "MT_C_BD") (pin "2") (pinfunction "2_2") (pintype "passive"))
      (node (ref "MT_C_BE") (pin "2") (pinfunction "2_2") (pintype "passive"))
      (node (ref "MT_C_BF") (pin "2") (pinfunction "2_2") (pintype "passive"))
      (node (ref "MT_C_BG") (pin "2") (pinfunction "2_2") (pintype "passive"))
      (node (ref "MT_C_BH") (pin "2") (pinfunction "2_2") (pintype "passive"))
      (node (ref "MT_C_BI") (pin "2") (pinfunction "2_2") (pintype "passive"))
      (node (ref "MT_C_BJ") (pin "2") (pinfunction "2_2") (pintype "passive"))
      (node (ref "MT_C_BK") (pin "2") (pinfunction "2_2") (pintype "passive"))
      (node (ref "MT_C_BL") (pin "2") (pinfunction "2_2") (pintype "passive"))
      (node (ref "MT_C_CM") (pin "2") (pinfunction "2_2") (pintype "passive"))
      (node (ref "MT_C_CN") (pin "2") (pinfunction "2_2") (pintype "passive"))
      (node (ref "MT_C_FA") (pin "2") (pinfunction "2_2") (pintype "passive"))
      (node (ref "MT_C_FB") (pin "2") (pinfunction "2_2") (pintype "passive"))
      (node (ref "MT_C_FC") (pin "2") (pinfunction "2_2") (pintype "passive"))
      (node (ref "MT_C_FD") (pin "2") (pinfunction "2_2") (pintype "passive"))
      (node (ref "MT_C_FE") (pin "2") (pinfunction "2_2") (pintype "passive"))
      (node (ref "MT_C_FF") (pin "2") (pinfunction "2_2") (pintype "passive"))
      (node (ref "MT_C_FG") (pin "2") (pinfunction "2_2") (pintype "passive"))
      (node (ref "MT_C_FH") (pin "2") (pinfunction "2_2") (pintype "passive"))
      (node (ref "MT_C_FI") (pin "2") (pinfunction "2_2") (pintype "passive"))
      (node (ref "MT_C_FJ") (pin "2") (pinfunction "2_2") (pintype "passive"))
      (node (ref "MT_C_FK") (pin "2") (pinfunction "2_2") (pintype "passive"))
      (node (ref "MT_C_FL") (pin "2") (pinfunction "2_2") (pintype "passive"))
      (node (ref "R10") (pin "2") (pinfunction "2_2") (pintype "passive"))
      (node (ref "Rioutsns2") (pin "2") (pinfunction "2_2") (pintype "passive"))
      (node (ref "Rvoutt") (pin "2") (pinfunction "2_2") (pintype "passive"))
    )
    (net (code "123") (name "VOUT_P") (class "Default")
      (node (ref "Dtg2") (pin "1") (pinfunction "K_1") (pintype "passive"))
      (node (ref "MT_C_CA") (pin "2") (pinfunction "2_2") (pintype "passive"))
      (node (ref "MT_C_CB") (pin "2") (pinfunction "2_2") (pintype "passive"))
      (node (ref "MT_C_CC") (pin "2") (pinfunction "2_2") (pintype "passive"))
      (node (ref "MT_C_CD") (pin "2") (pinfunction "2_2") (pintype "passive"))
      (node (ref "MT_C_CE") (pin "2") (pinfunction "2_2") (pintype "passive"))
      (node (ref "MT_C_CF") (pin "2") (pinfunction "2_2") (pintype "passive"))
      (node (ref "MT_C_CG") (pin "2") (pinfunction "2_2") (pintype "passive"))
      (node (ref "MT_C_CH") (pin "2") (pinfunction "2_2") (pintype "passive"))
      (node (ref "MT_C_CI") (pin "2") (pinfunction "2_2") (pintype "passive"))
      (node (ref "MT_C_CJ") (pin "2") (pinfunction "2_2") (pintype "passive"))
      (node (ref "MT_C_CK") (pin "2") (pinfunction "2_2") (pintype "passive"))
      (node (ref "MT_C_CL") (pin "2") (pinfunction "2_2") (pintype "passive"))
      (node (ref "MT_Q4") (pin "2") (pinfunction "D_2") (pintype "passive"))
      (node (ref "R10") (pin "1") (pinfunction "1_1") (pintype "passive"))
      (node (ref "Rioutsns1") (pin "2") (pinfunction "2_2") (pintype "passive"))
    )
    (net (code "124") (name "unconnected-(J1-SHIELD-PadS1)") (class "Default")
      (node (ref "J1") (pin "S1") (pinfunction "SHIELD_S1") (pintype "passive"))
    )
    (net (code "125") (name "unconnected-(J1-SHIELD-PadS2)") (class "Default")
      (node (ref "J1") (pin "S2") (pinfunction "SHIELD_S2") (pintype "passive"))
    )
    (net (code "126") (name "unconnected-(J2-SHIELD-PadS1)") (class "Default")
      (node (ref "J2") (pin "S1") (pinfunction "SHIELD_S1") (pintype "passive"))
    )
    (net (code "127") (name "unconnected-(J2-SHIELD-PadS2)") (class "Default")
      (node (ref "J2") (pin "S2") (pinfunction "SHIELD_S2") (pintype "passive"))
    )
    (net (code "128") (name "unconnected-(MT_KB-NC1-Pad2)") (class "Default")
      (node (ref "MT_KB") (pin "2") (pinfunction "NC1_2") (pintype "passive"))
    )
    (net (code "129") (name "unconnected-(MT_U_B-OVP-Pad15)") (class "Default")
      (node (ref "MT_U_B") (pin "15") (pinfunction "OVP_15") (pintype "passive"))
    )
    (net (code "130") (name "unconnected-(MT_U_T-Y15-Pad16)") (class "Default")
      (node (ref "MT_U_T") (pin "16") (pinfunction "Y15_16") (pintype "passive"))
    )
  )
)
